# WMHS_Team_A_Mission_Possible_Electrical.net
KiCad netlist of a schematic drawn in EAGLE
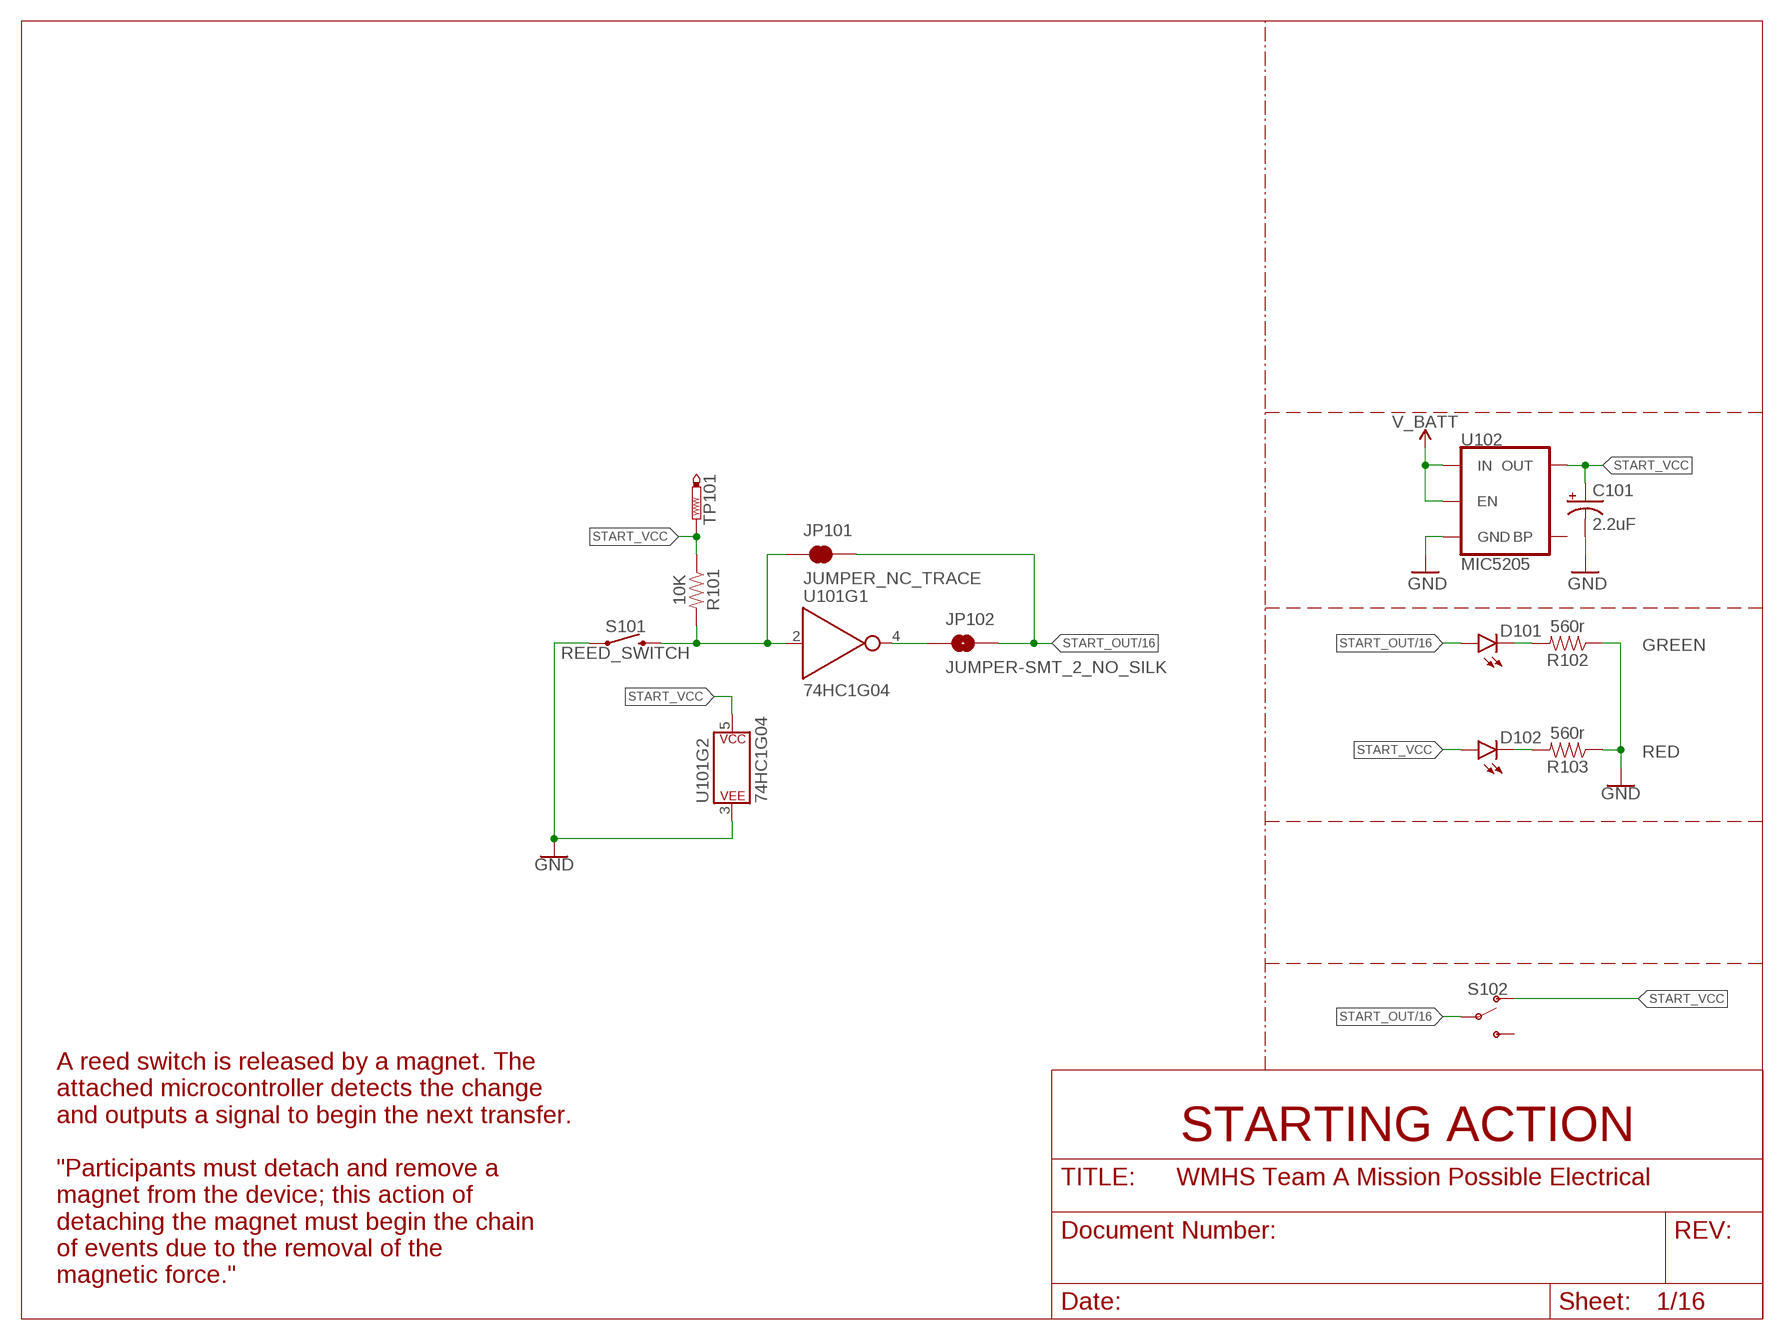
[diagram p0: schematic, sheet 1]
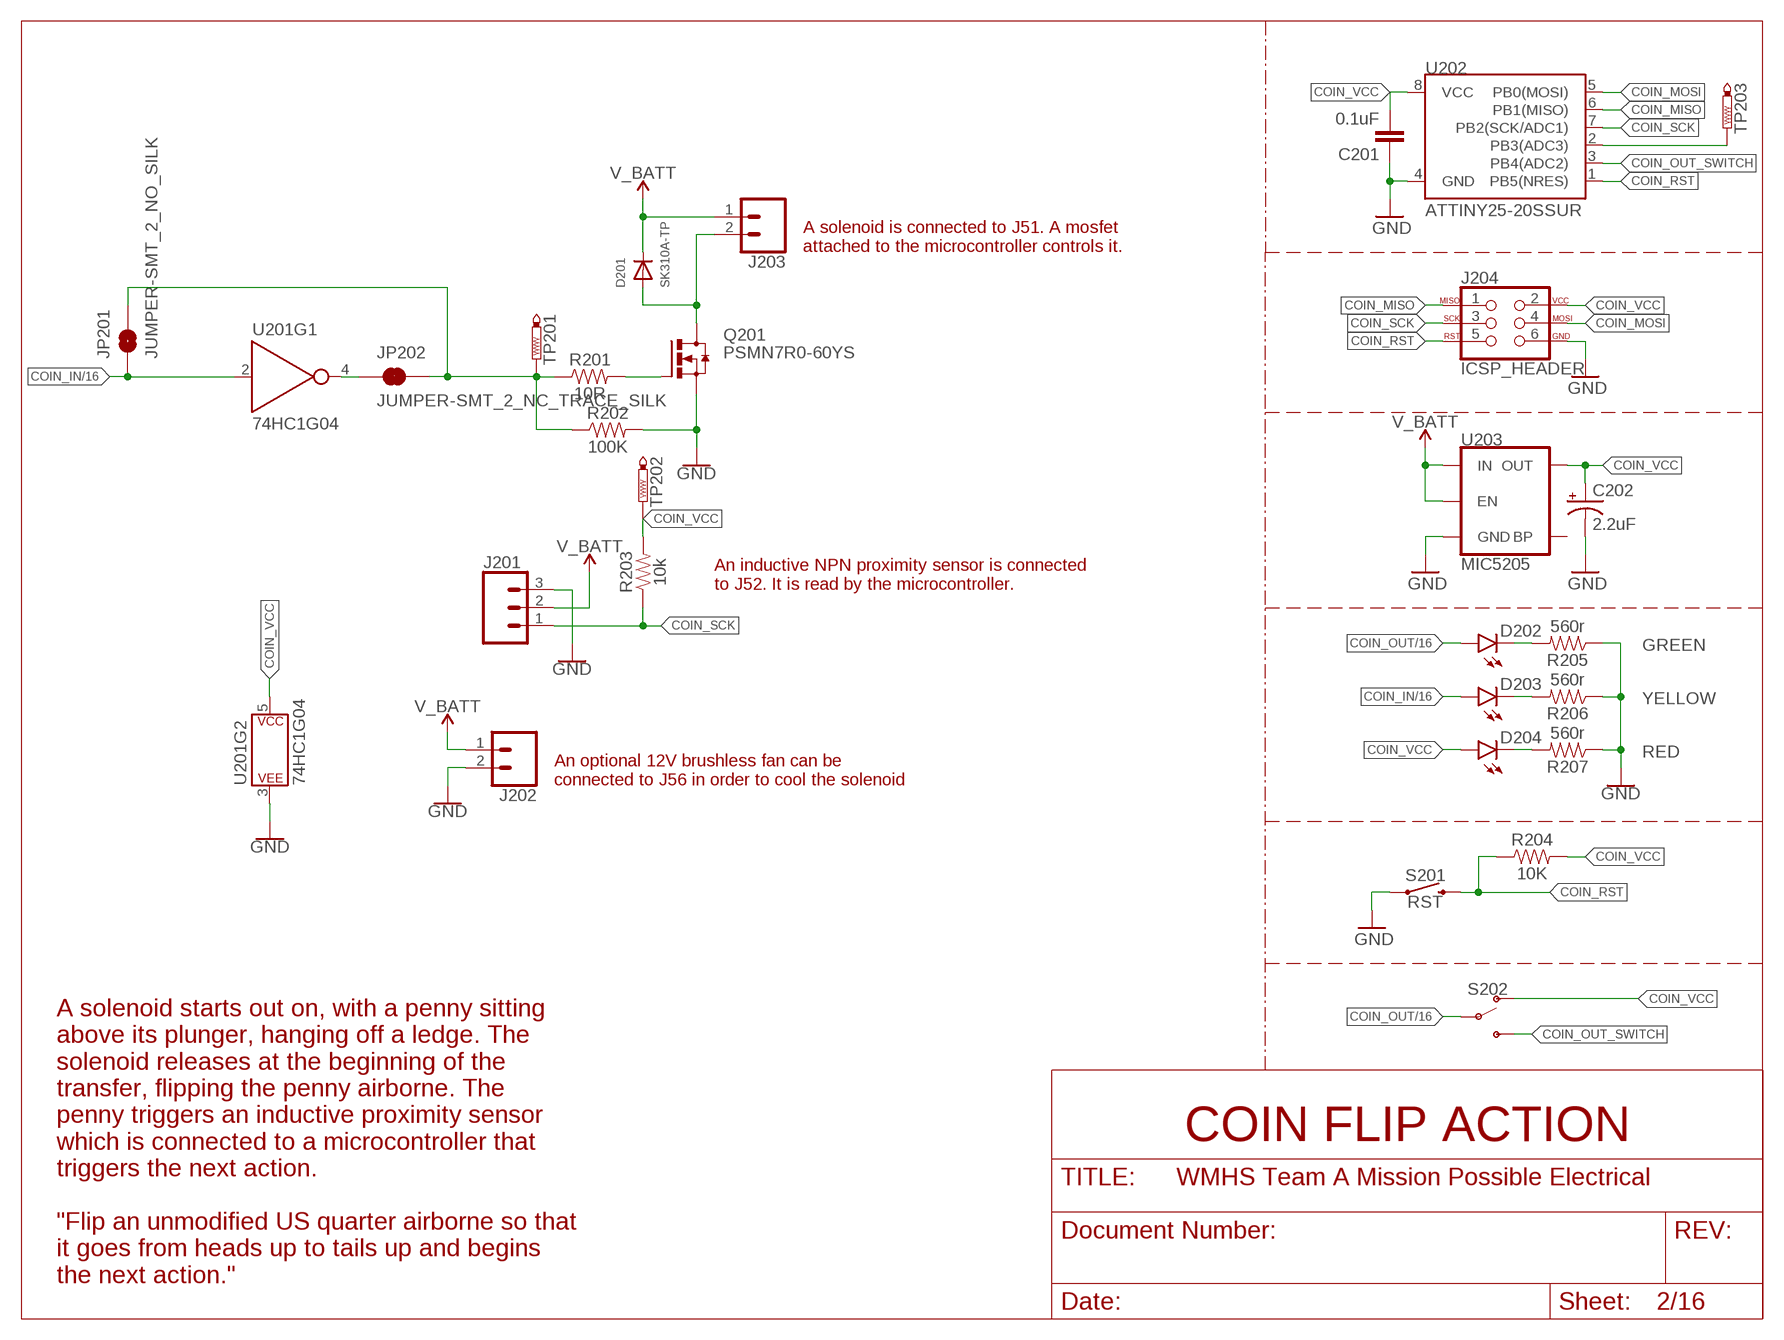
[diagram p1: schematic, sheet 2]
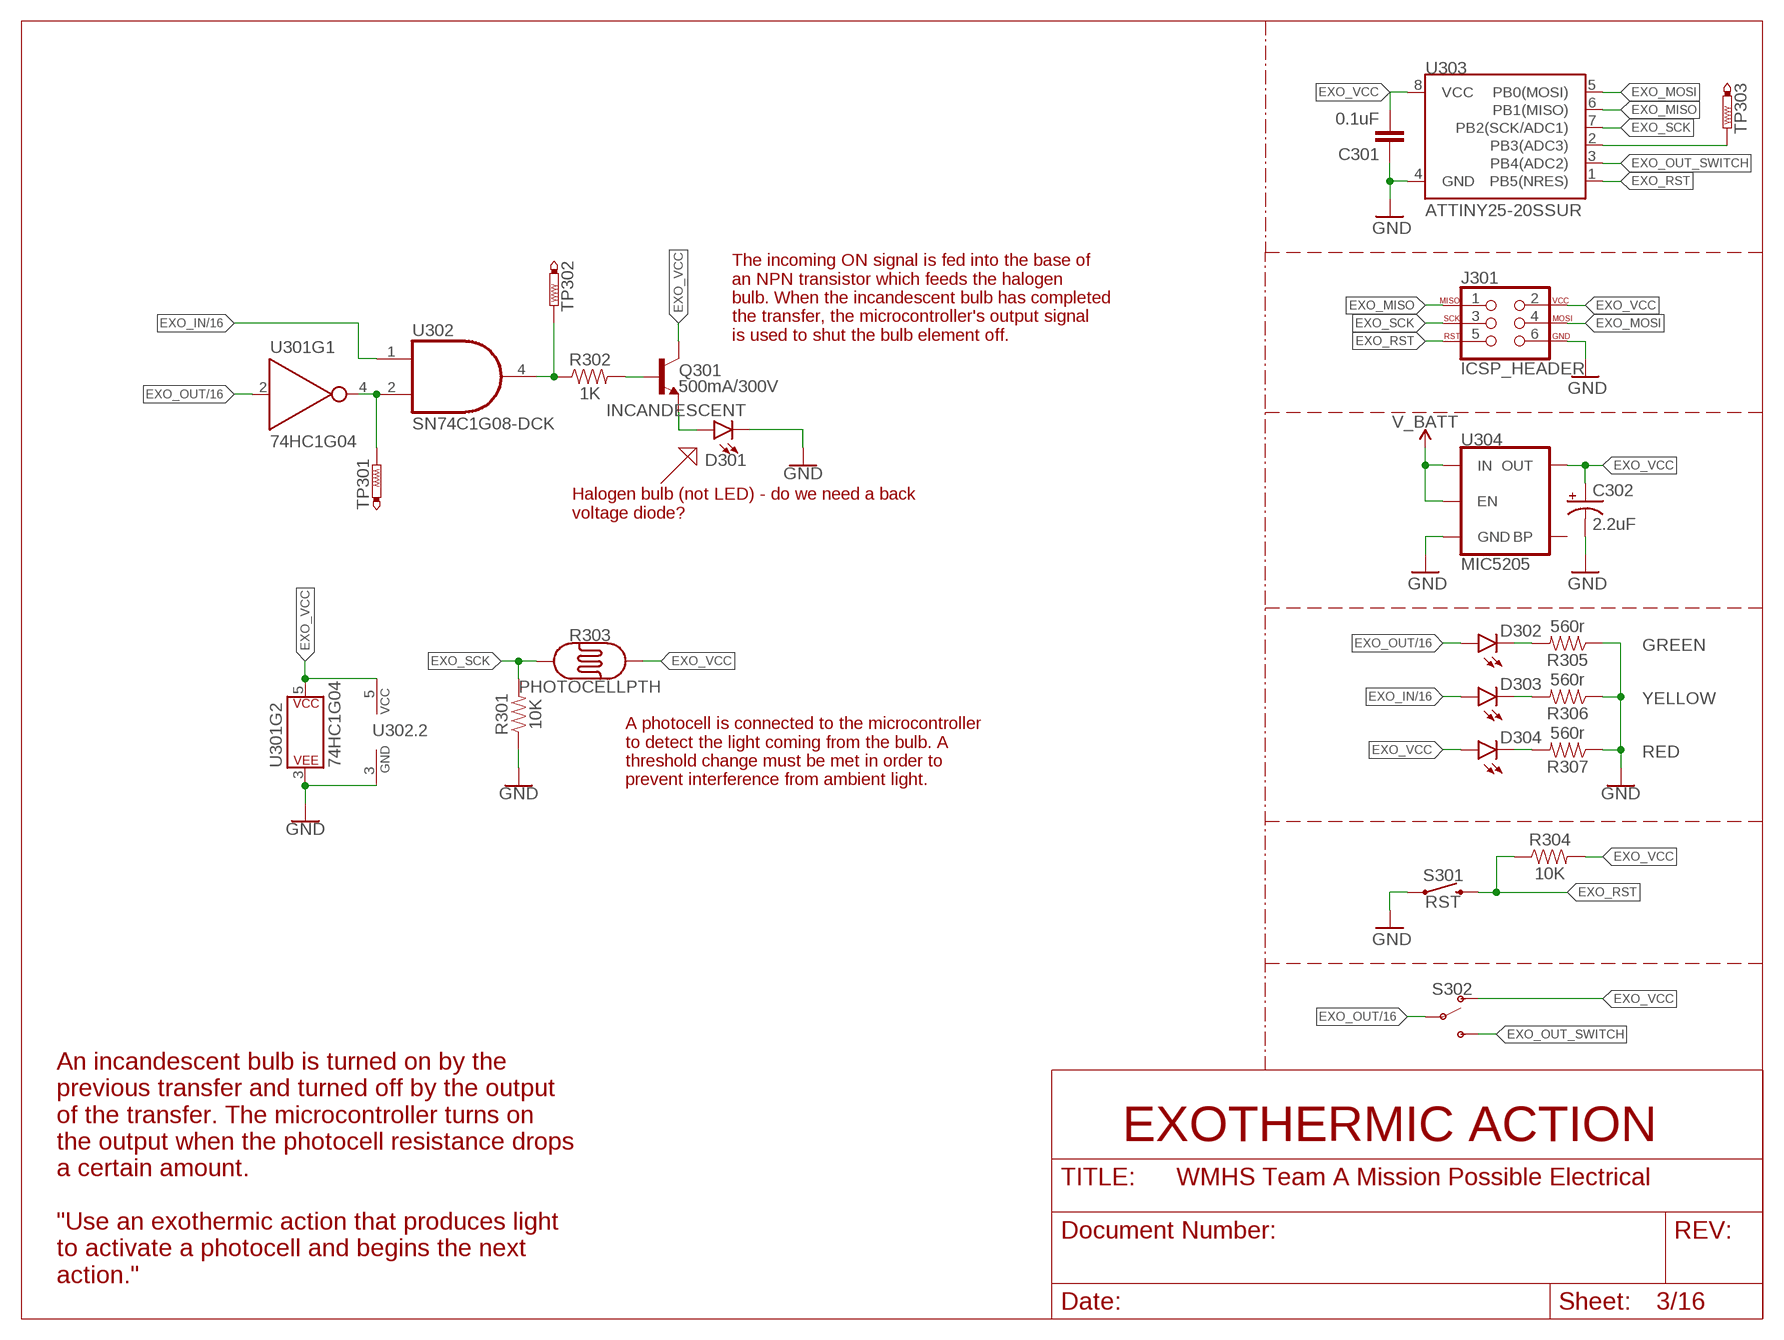
[diagram p2: schematic, sheet 3]
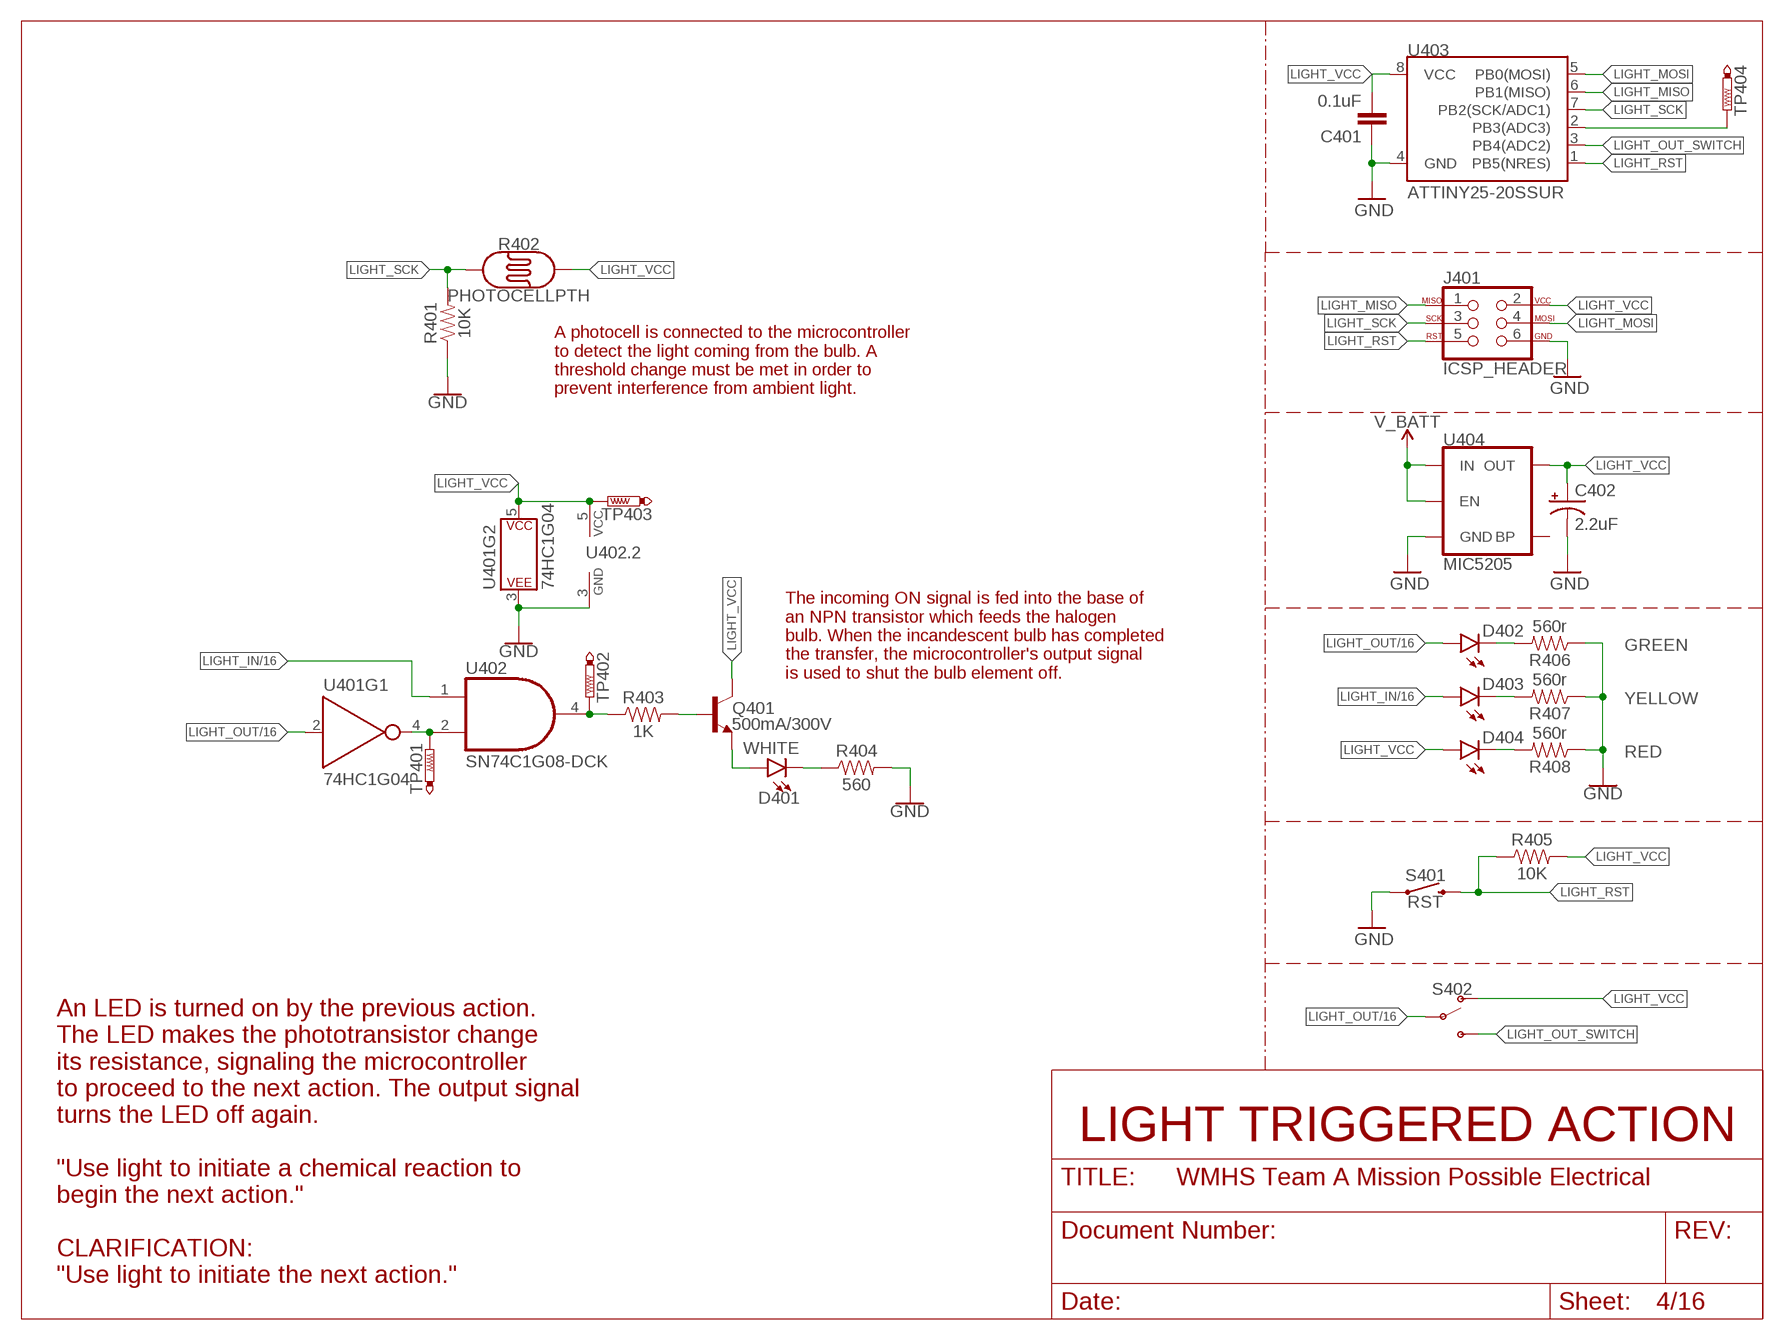
[diagram p3: schematic, sheet 4]
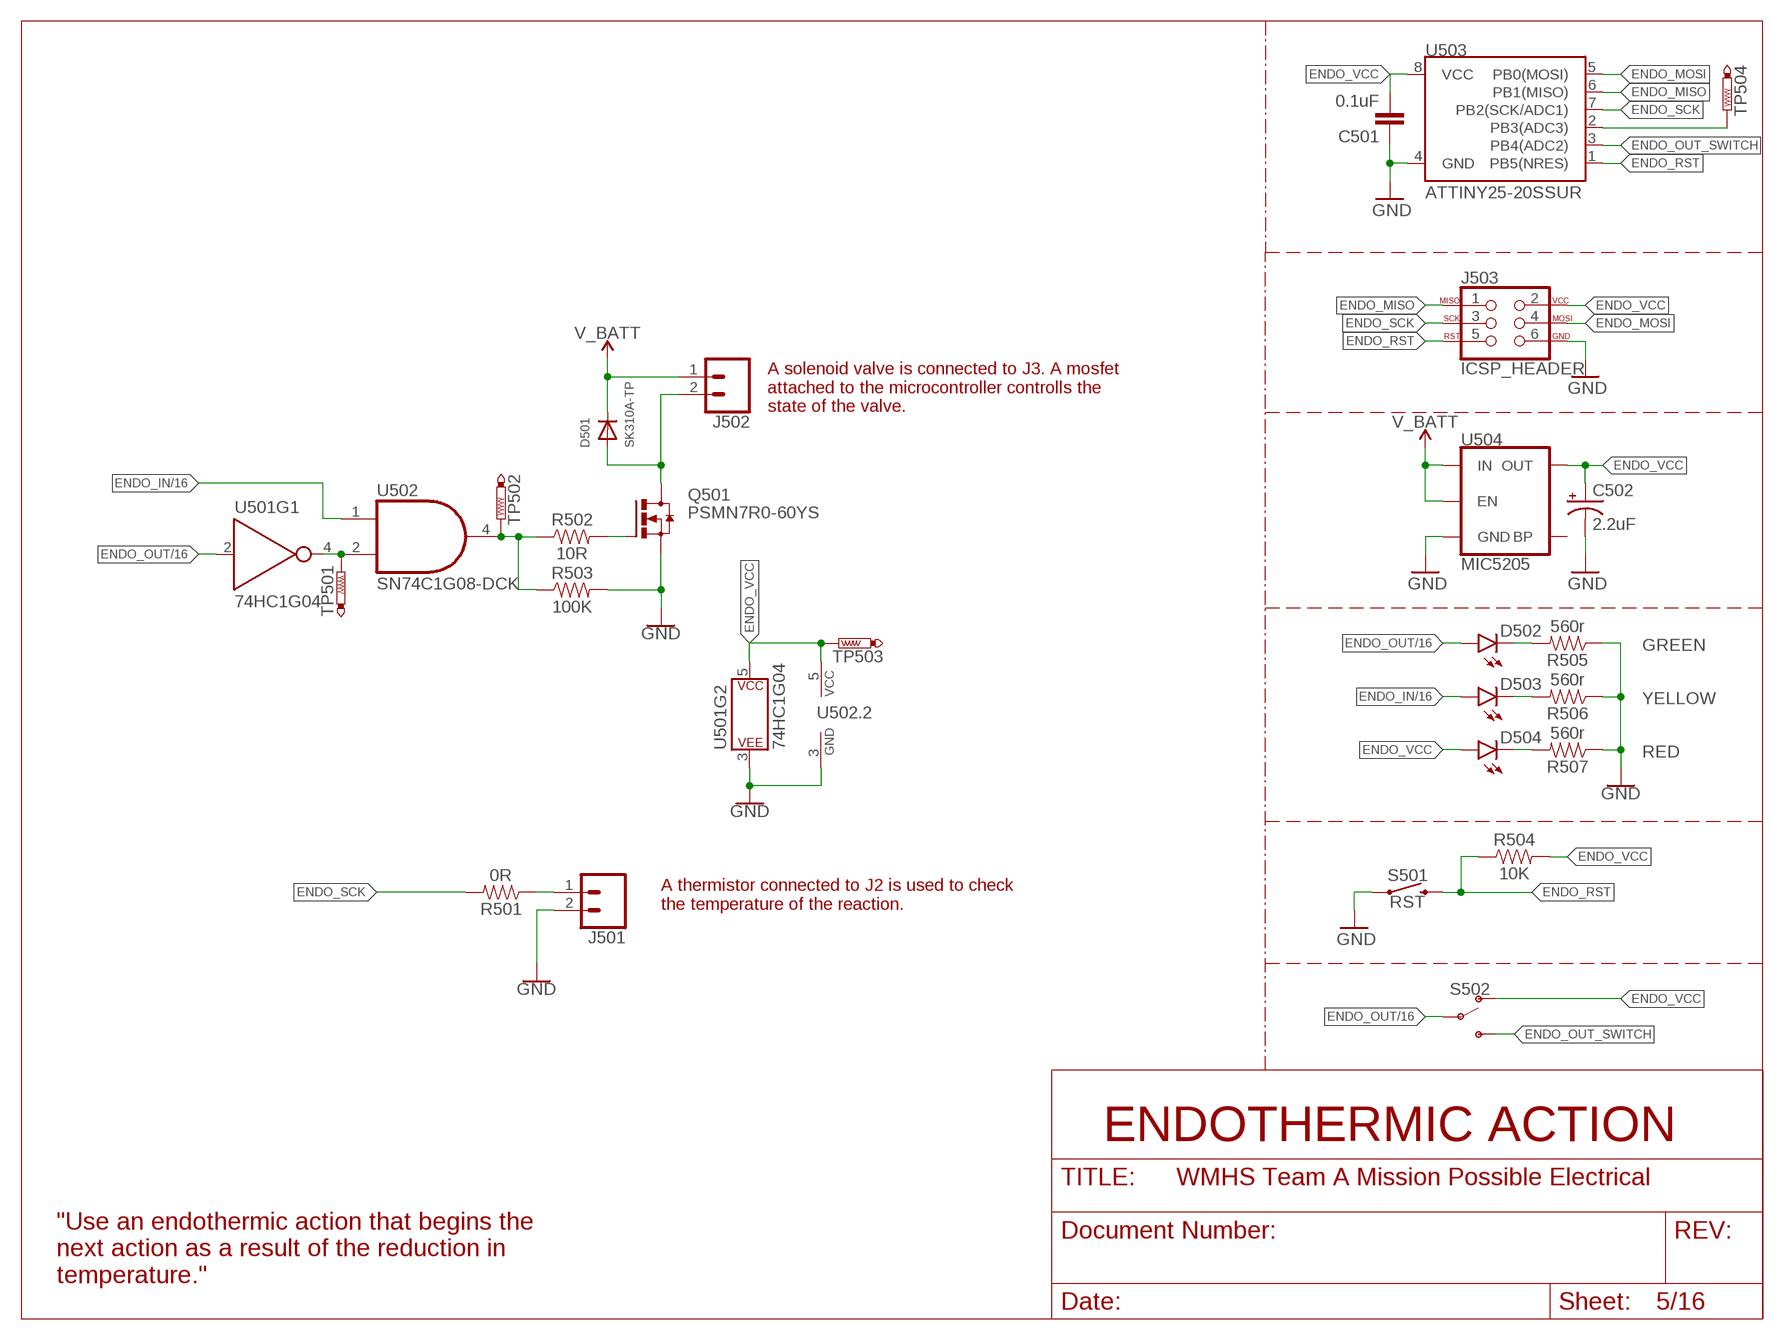
[diagram p4: schematic, sheet 5]
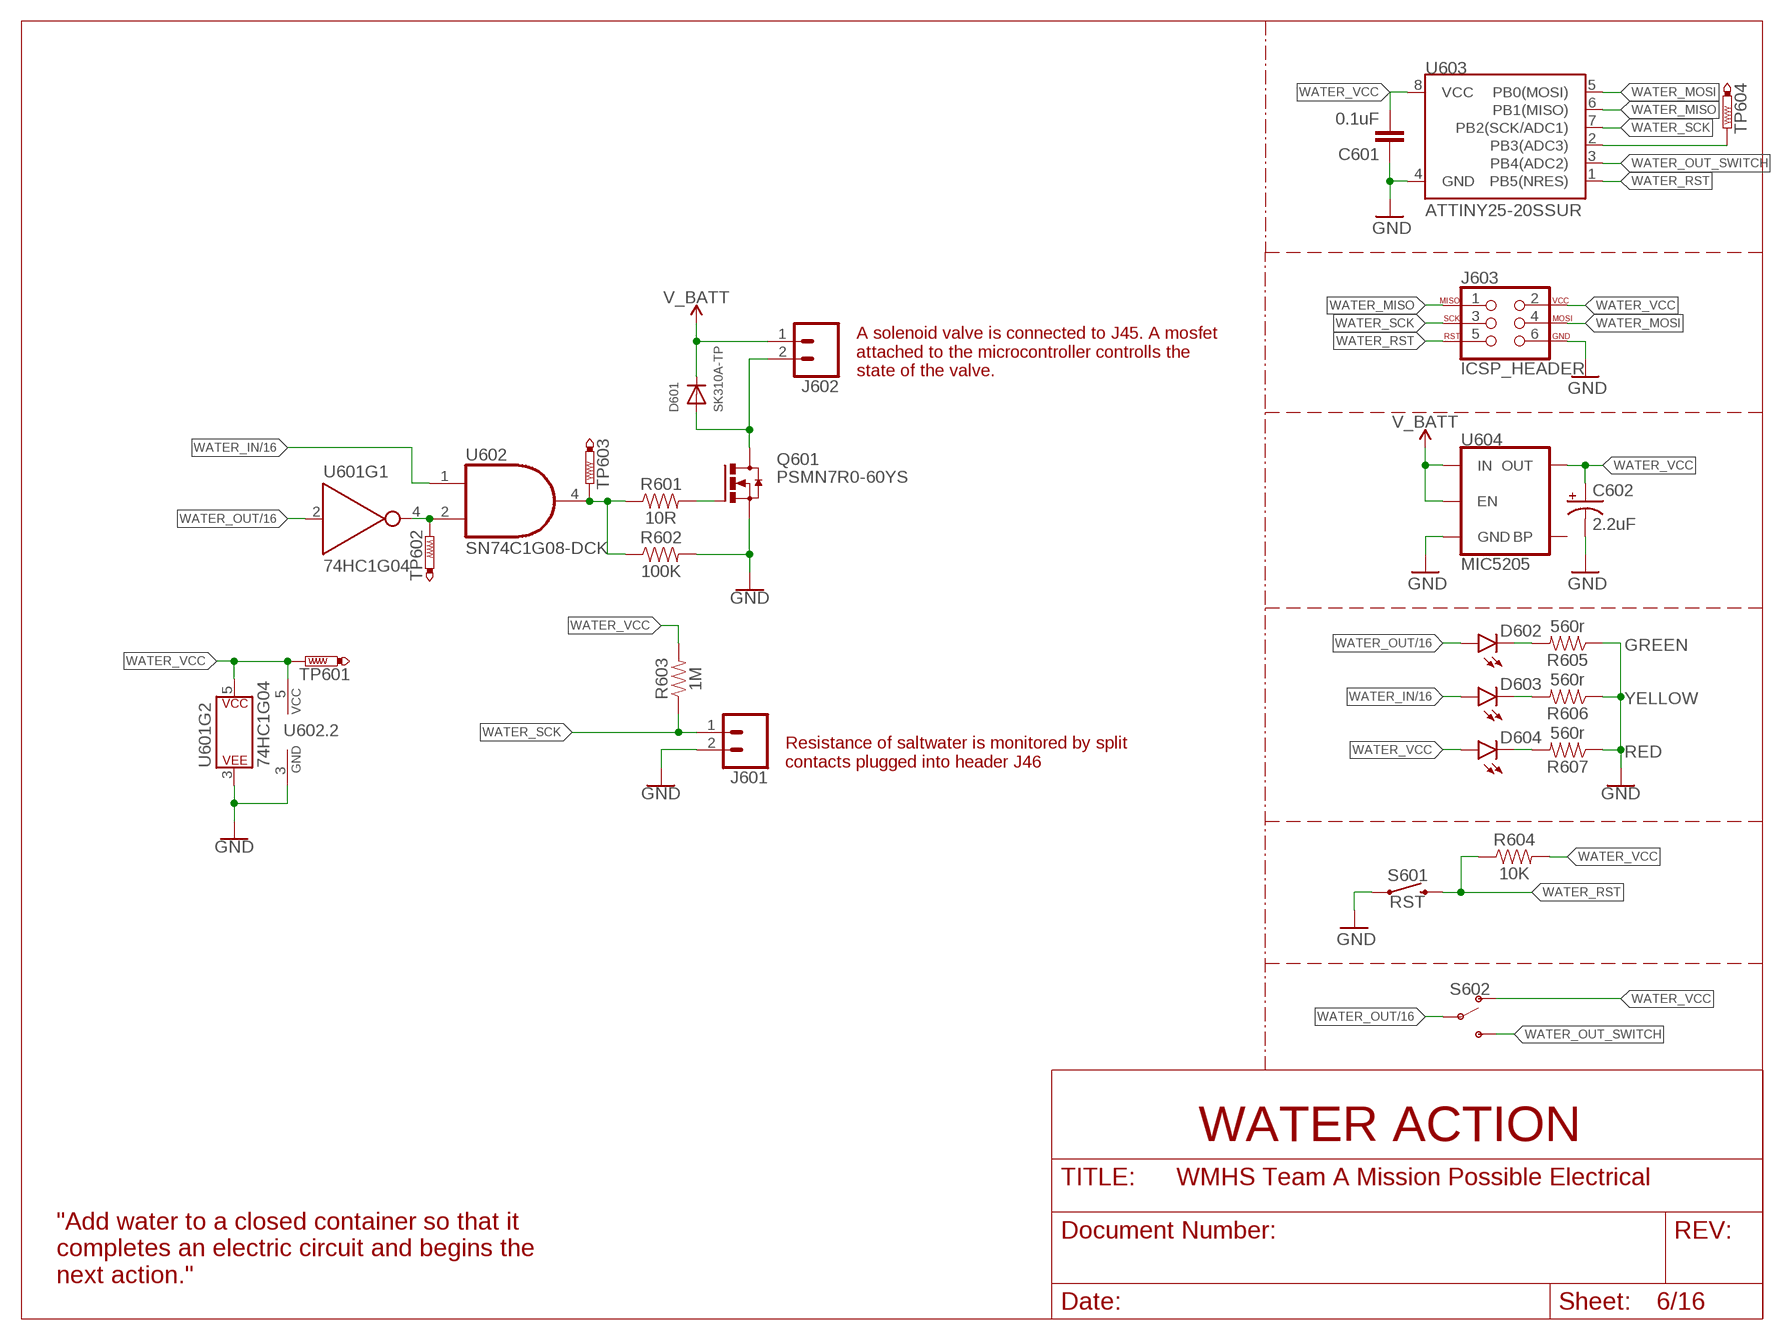
[diagram p5: schematic, sheet 6]
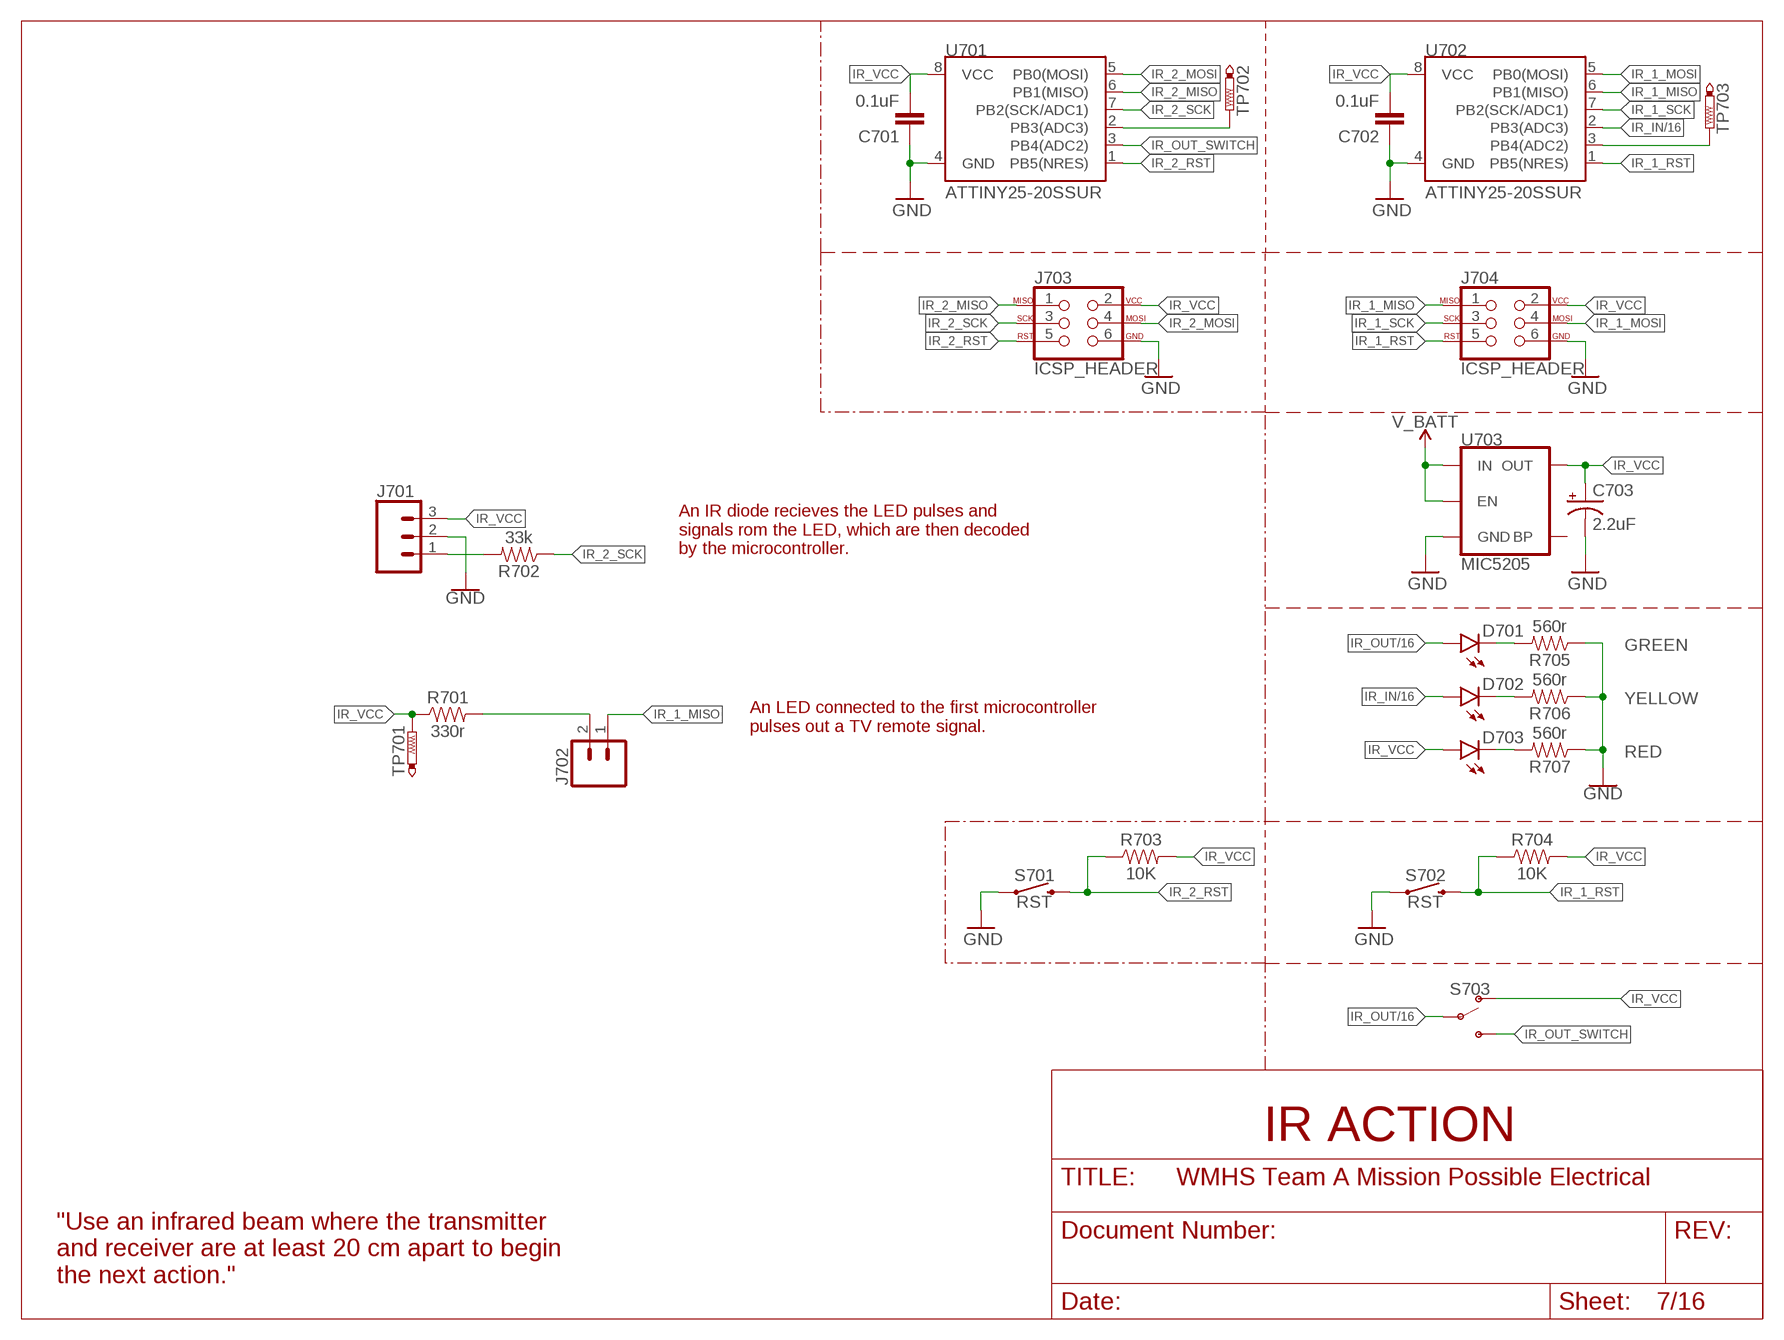
[diagram p6: schematic, sheet 7]
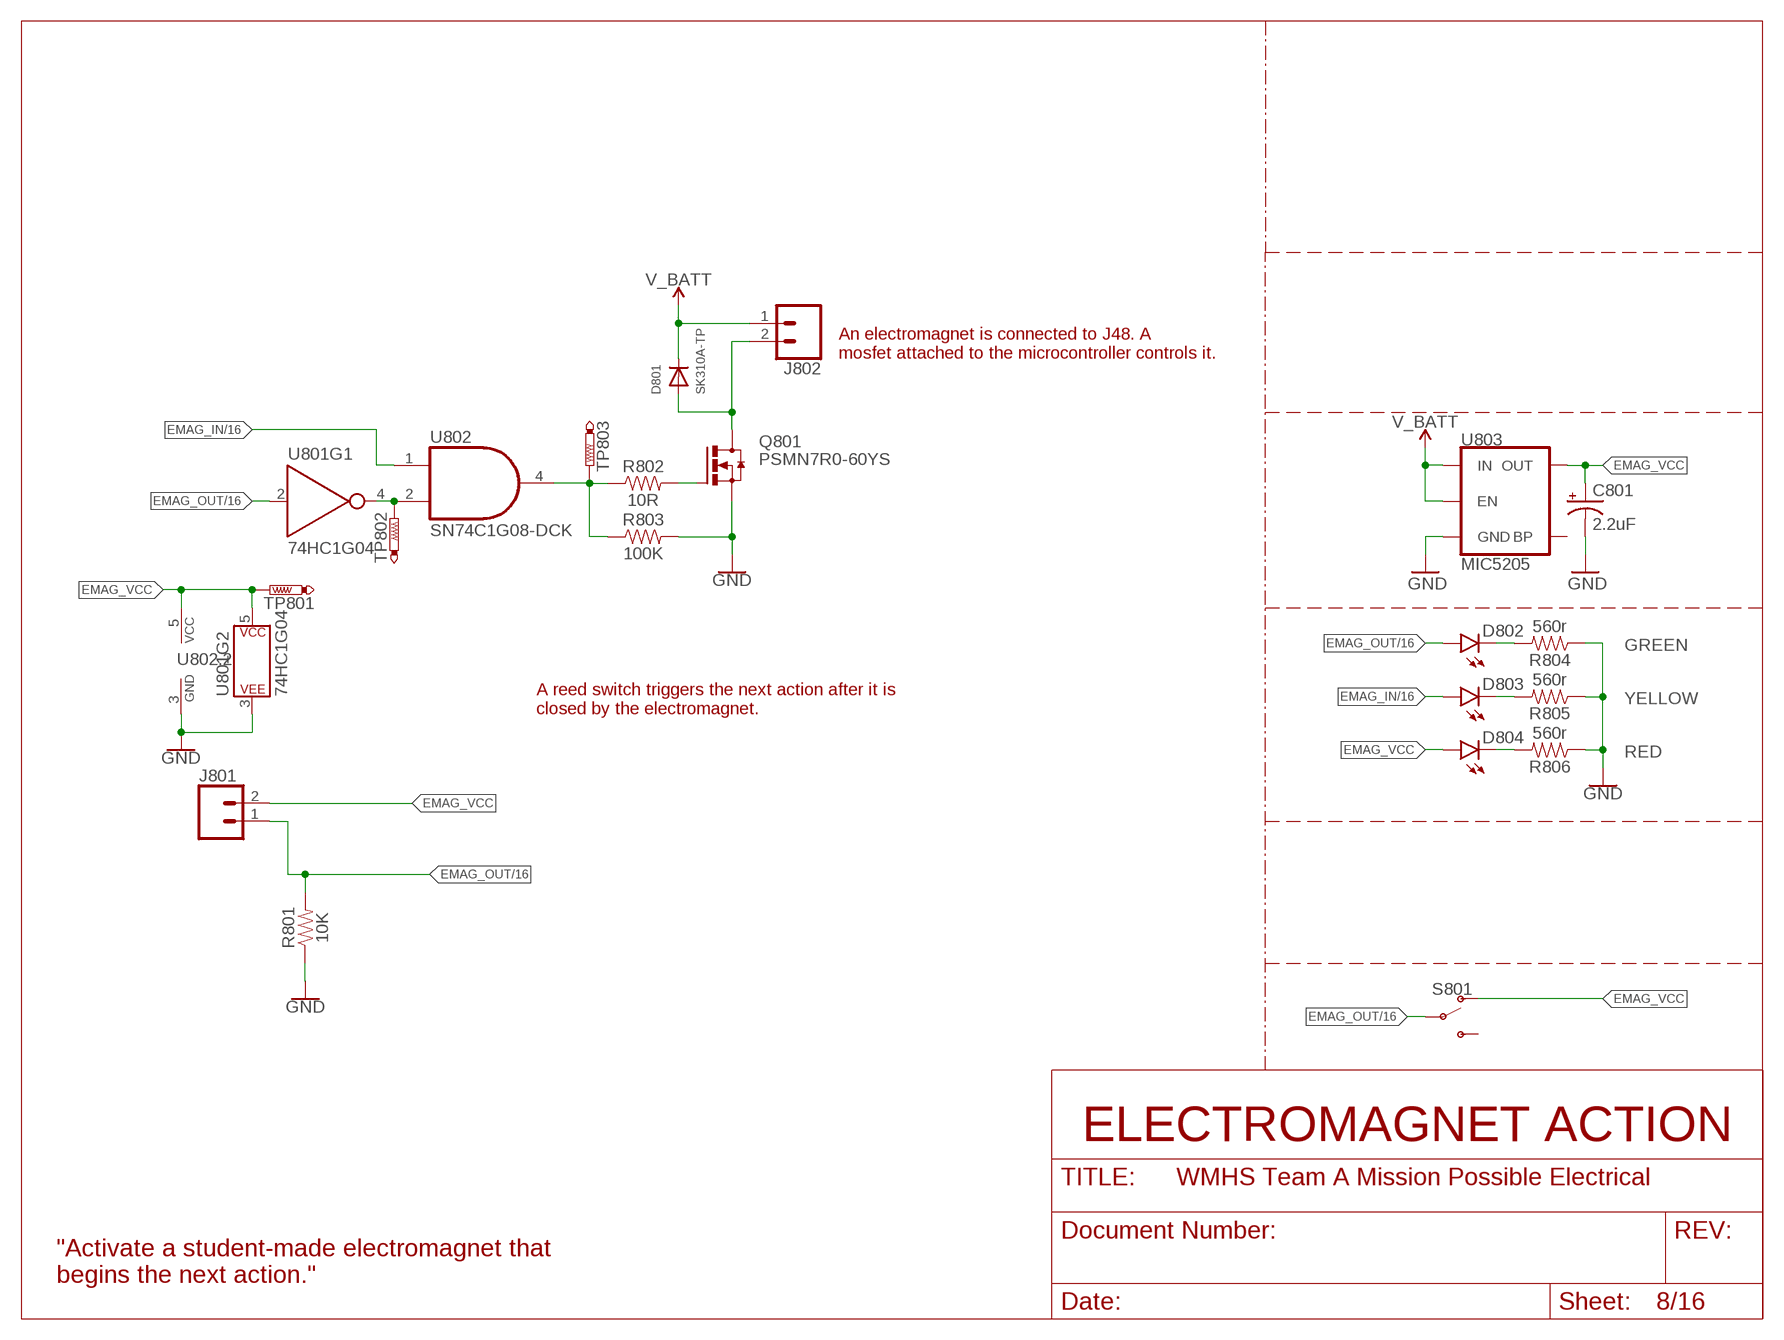
[diagram p7: schematic, sheet 8]
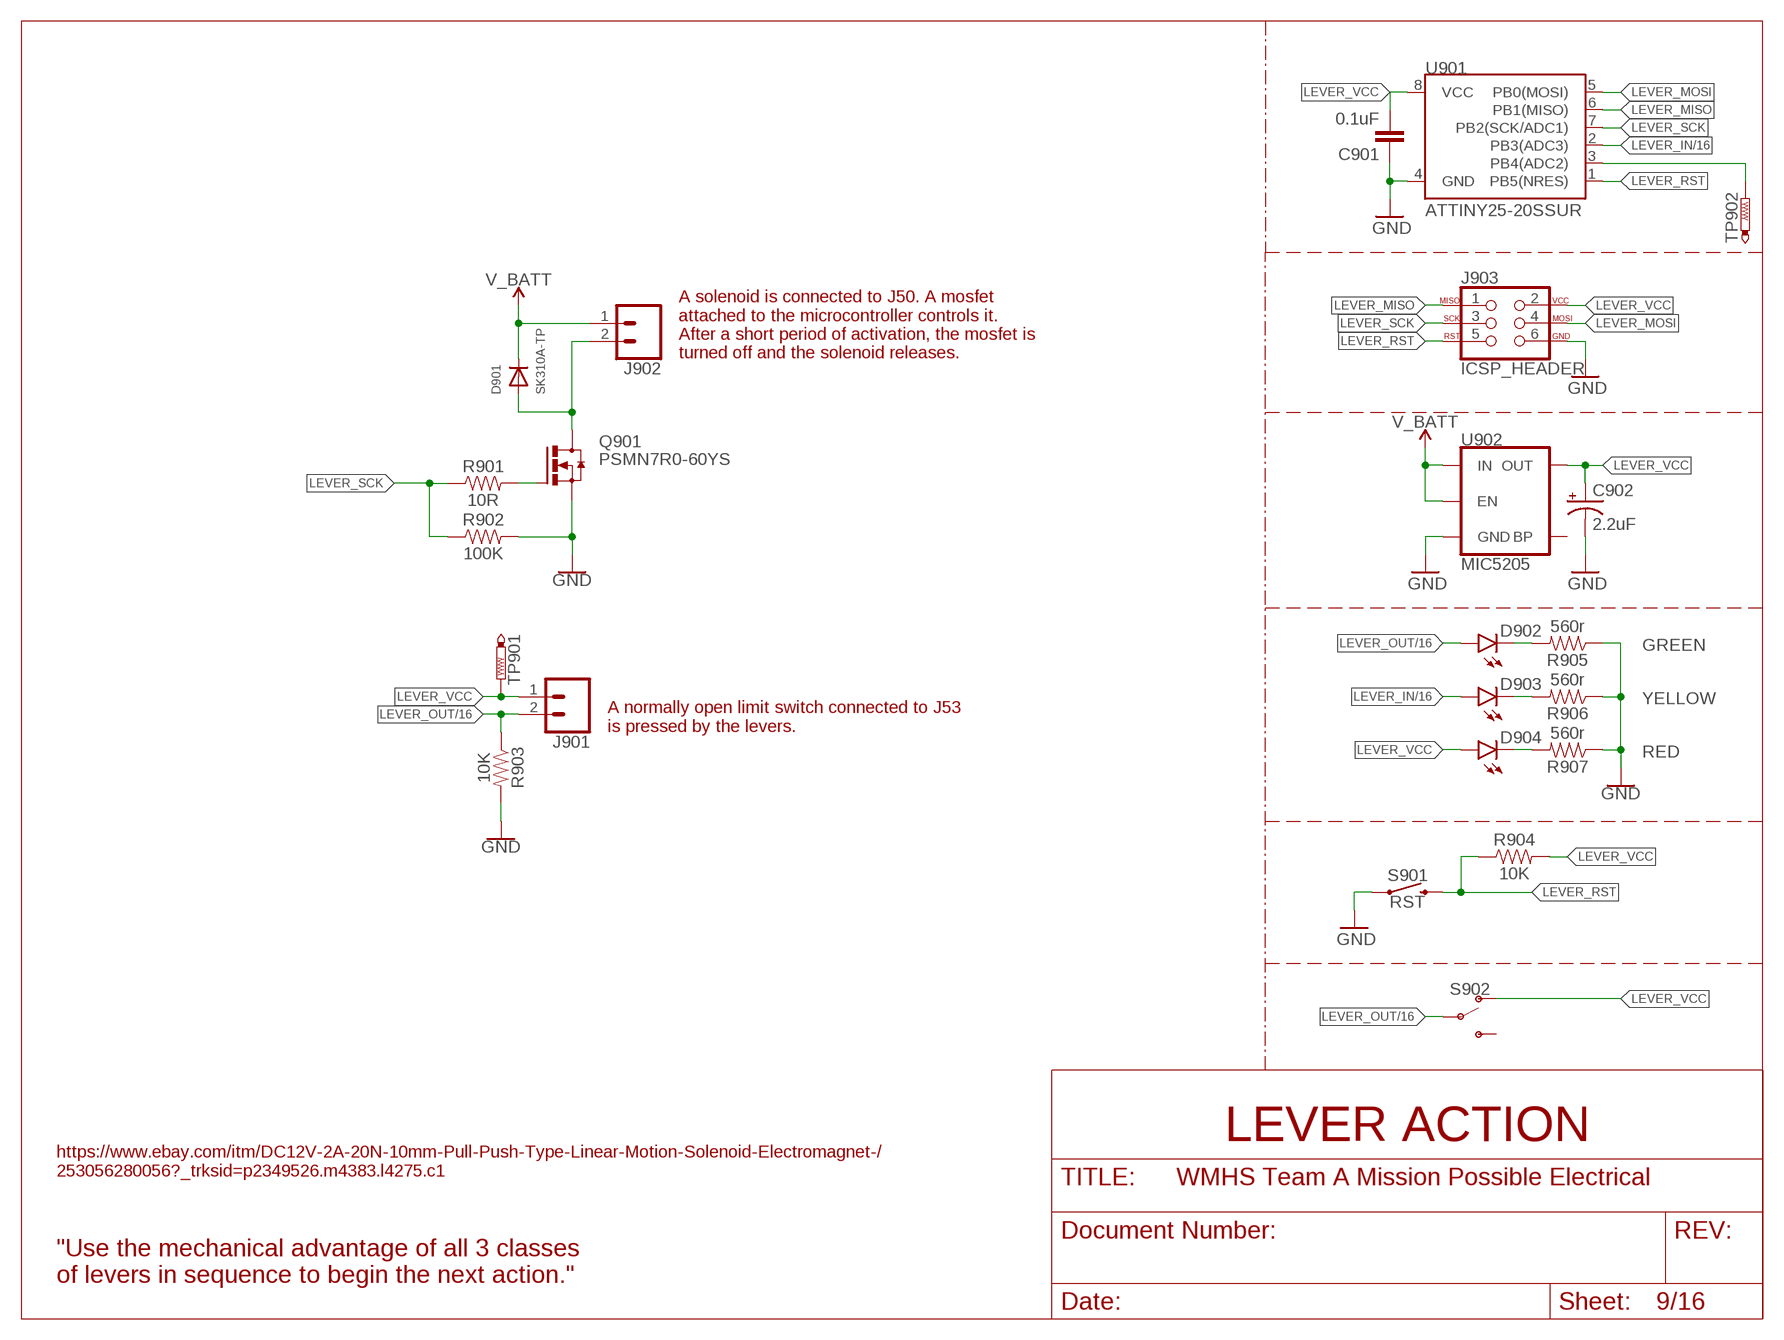
[diagram p8: schematic, sheet 9]
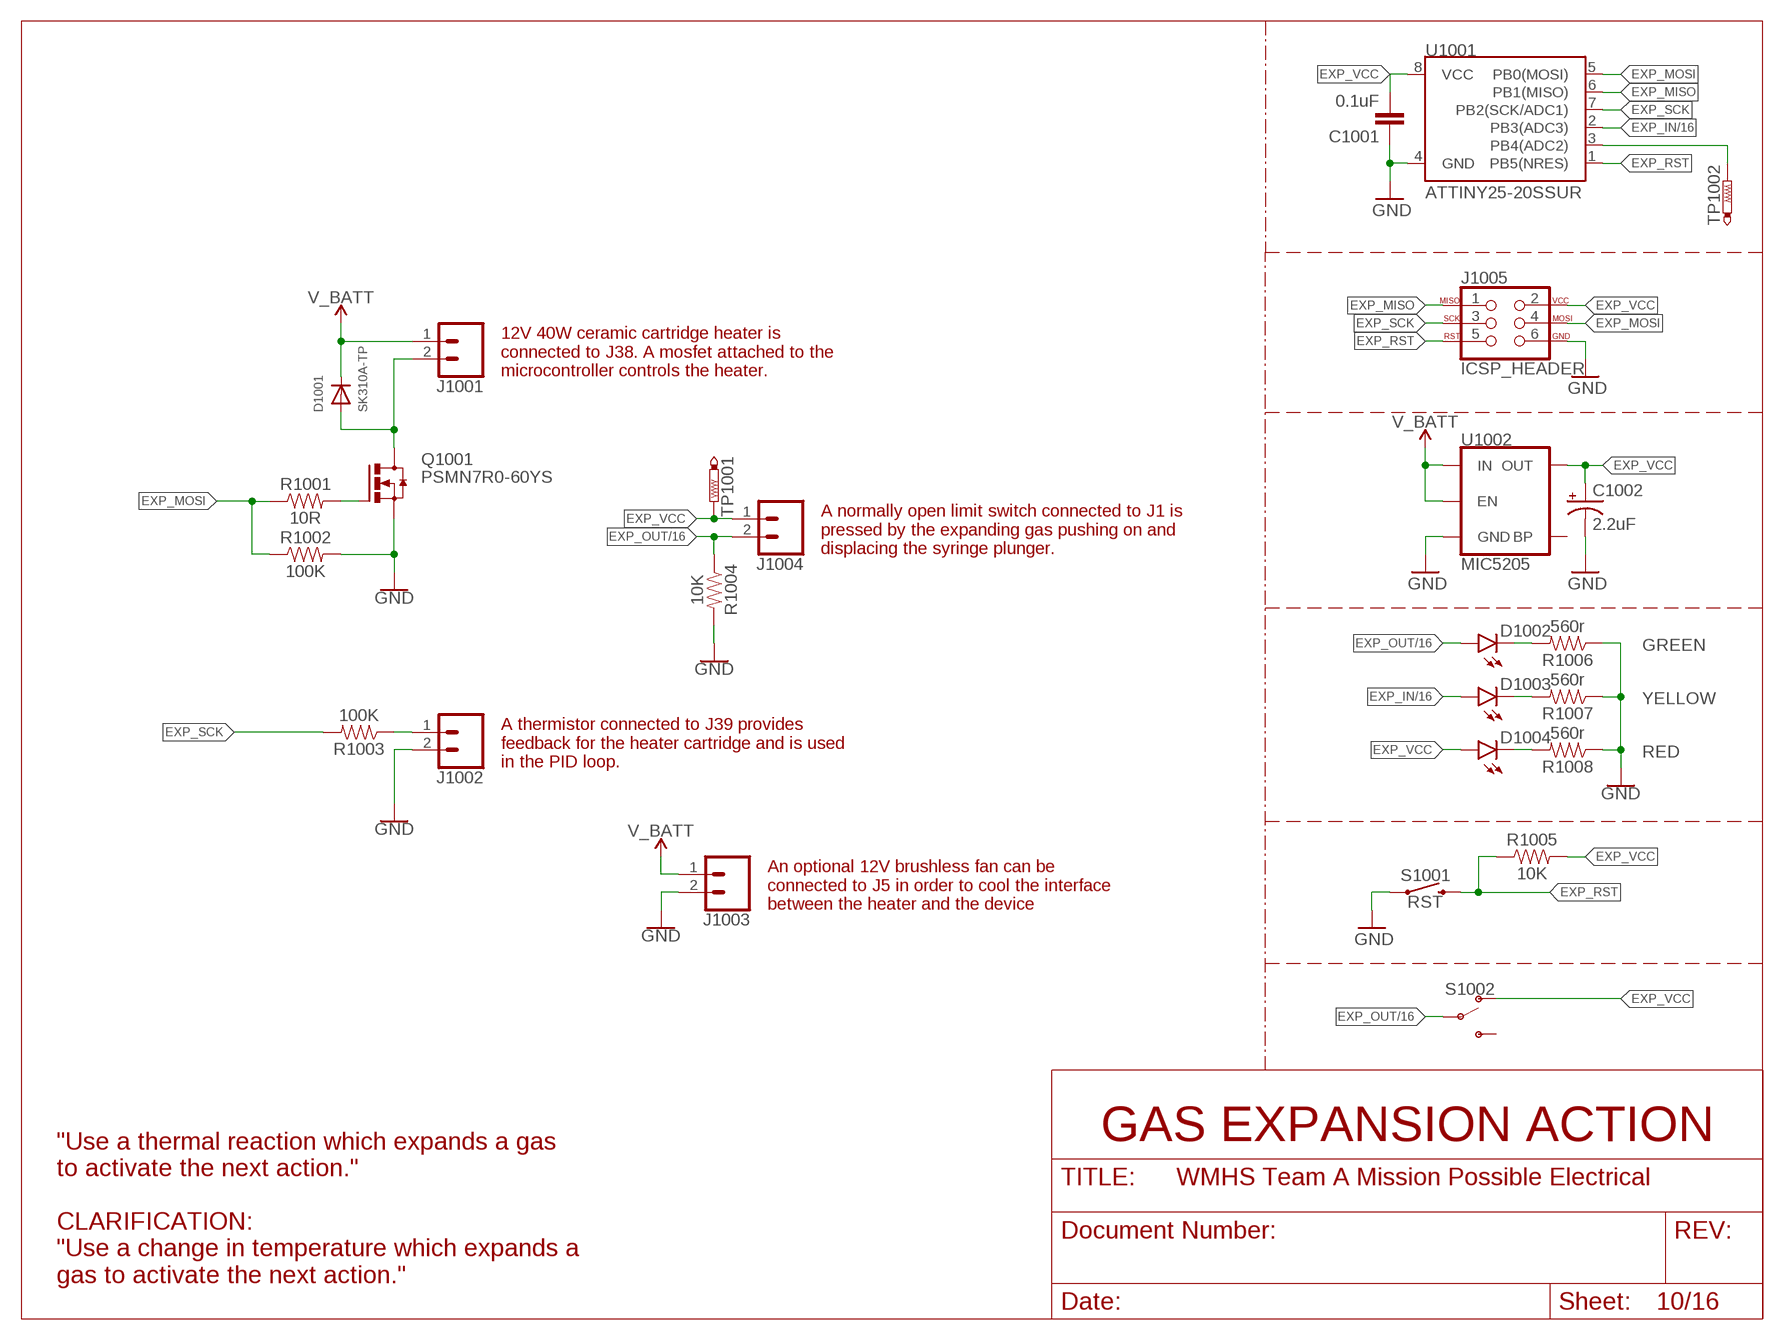
[diagram p9: schematic, sheet 10]
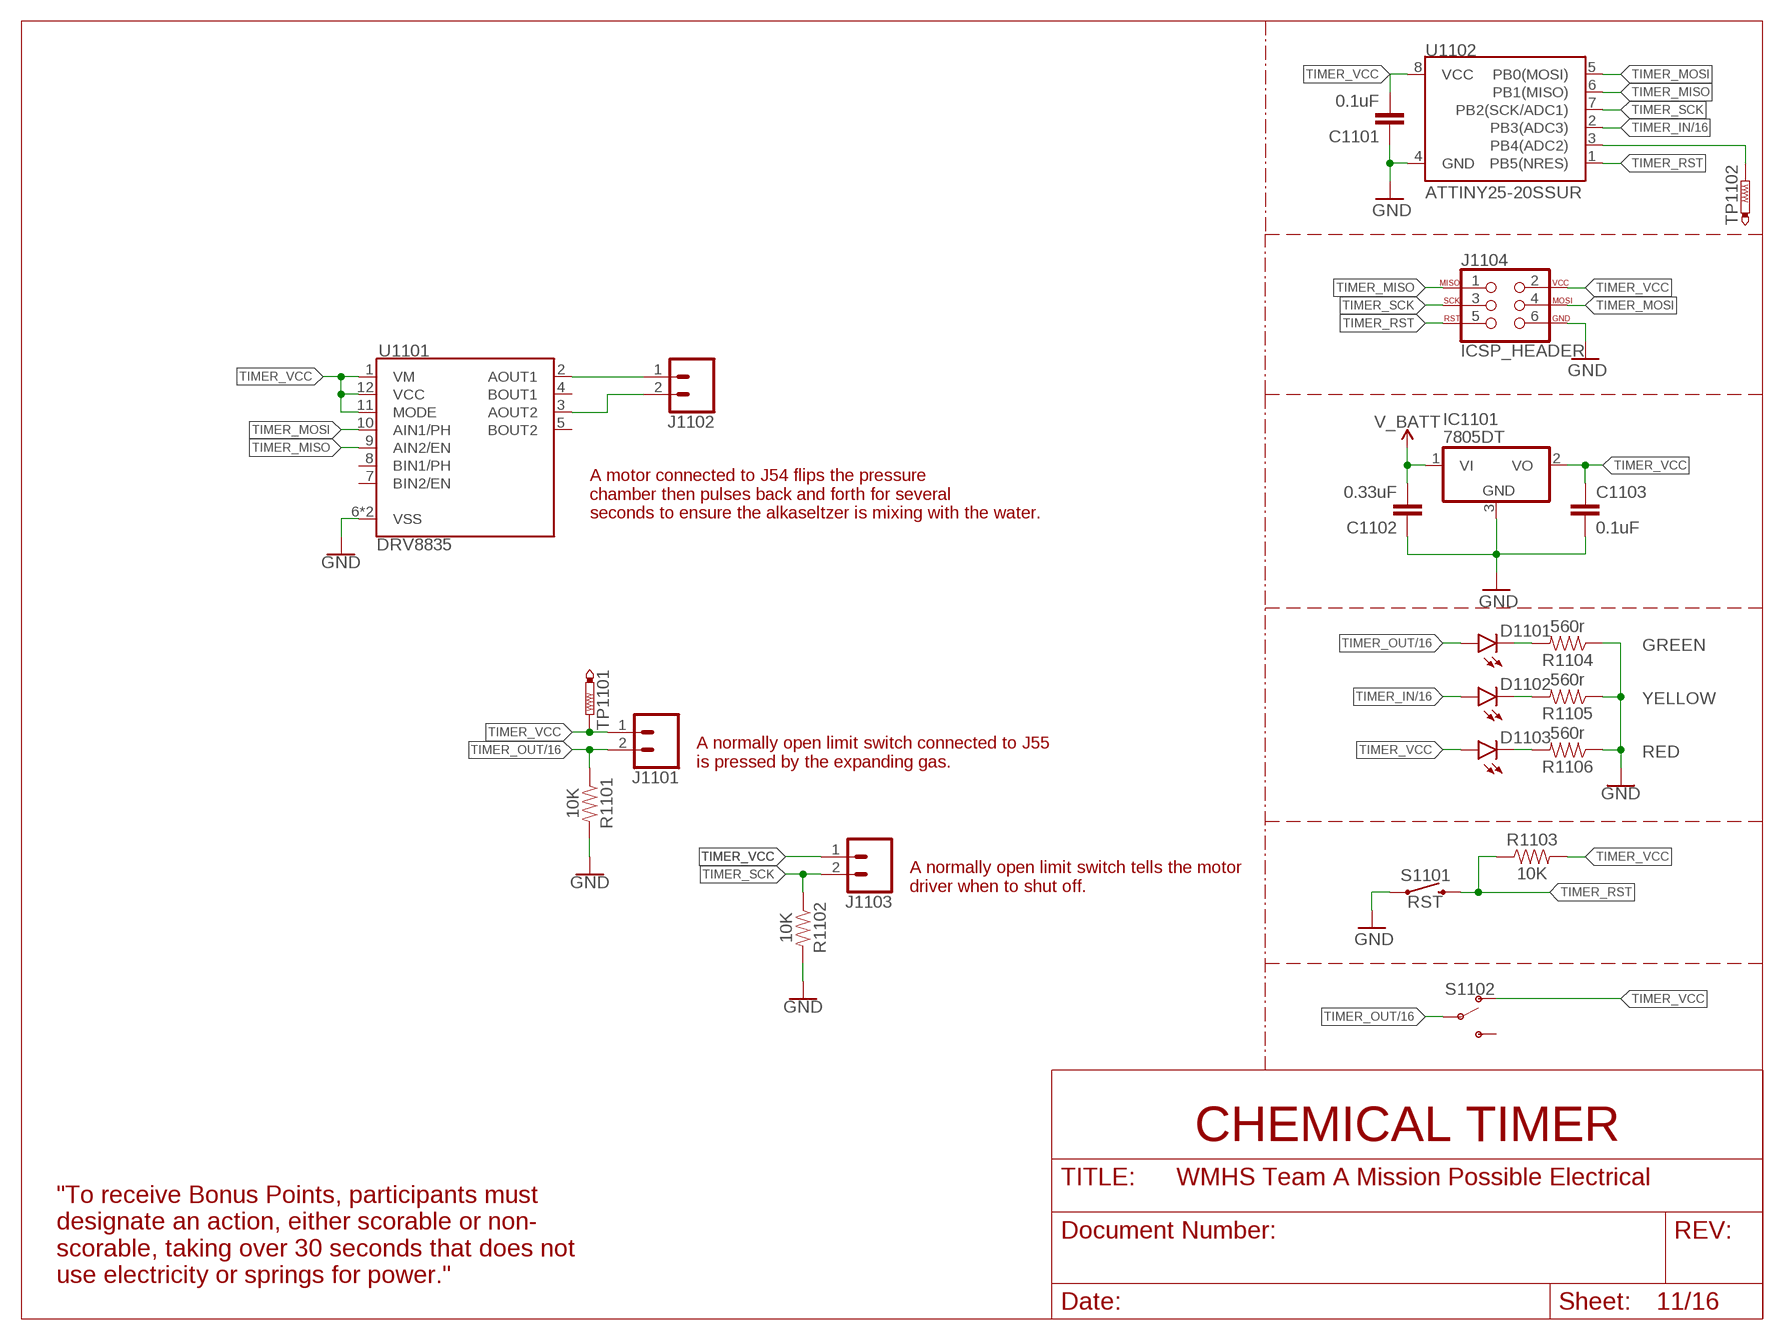
[diagram p10: schematic, sheet 11]
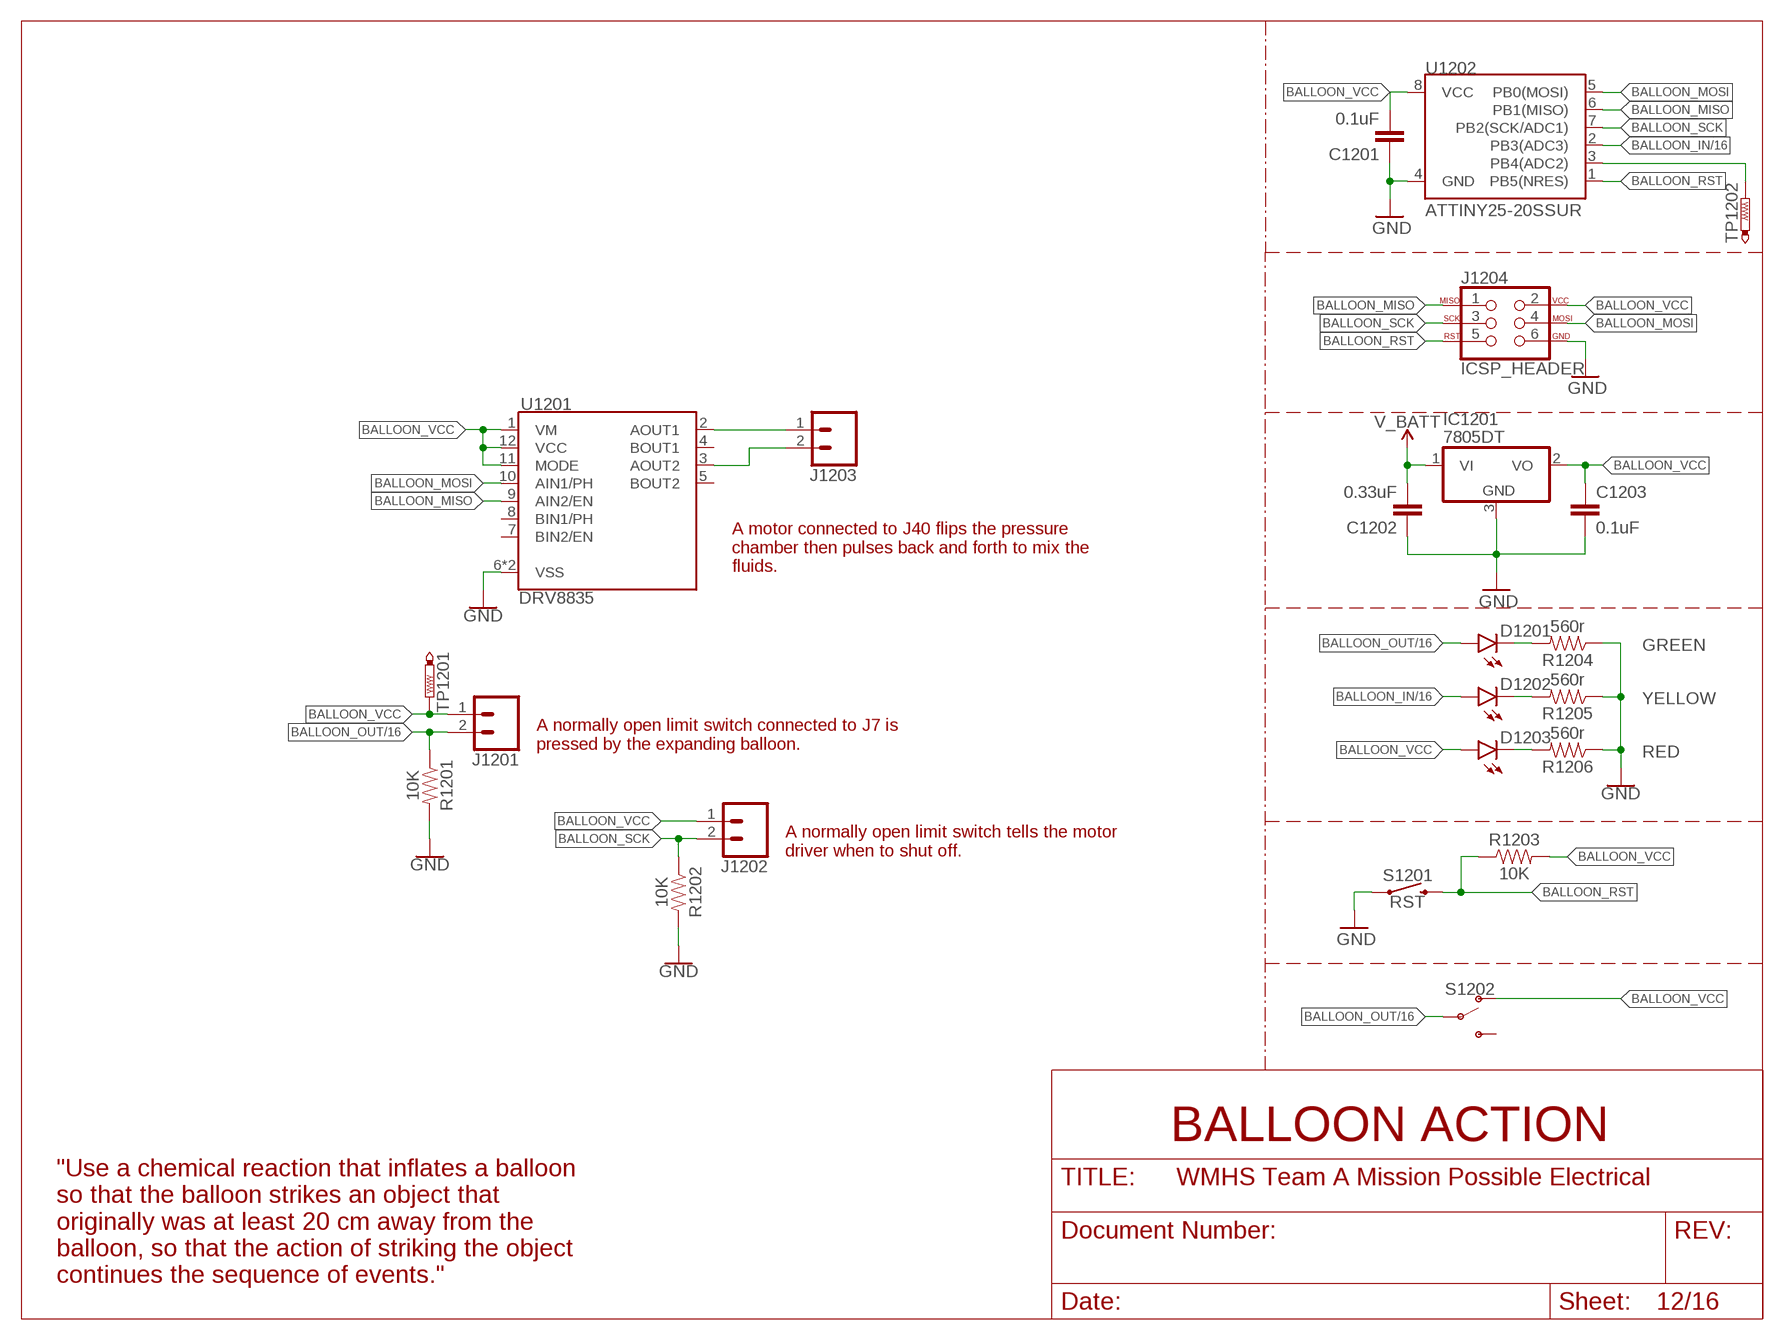
[diagram p11: schematic, sheet 12]
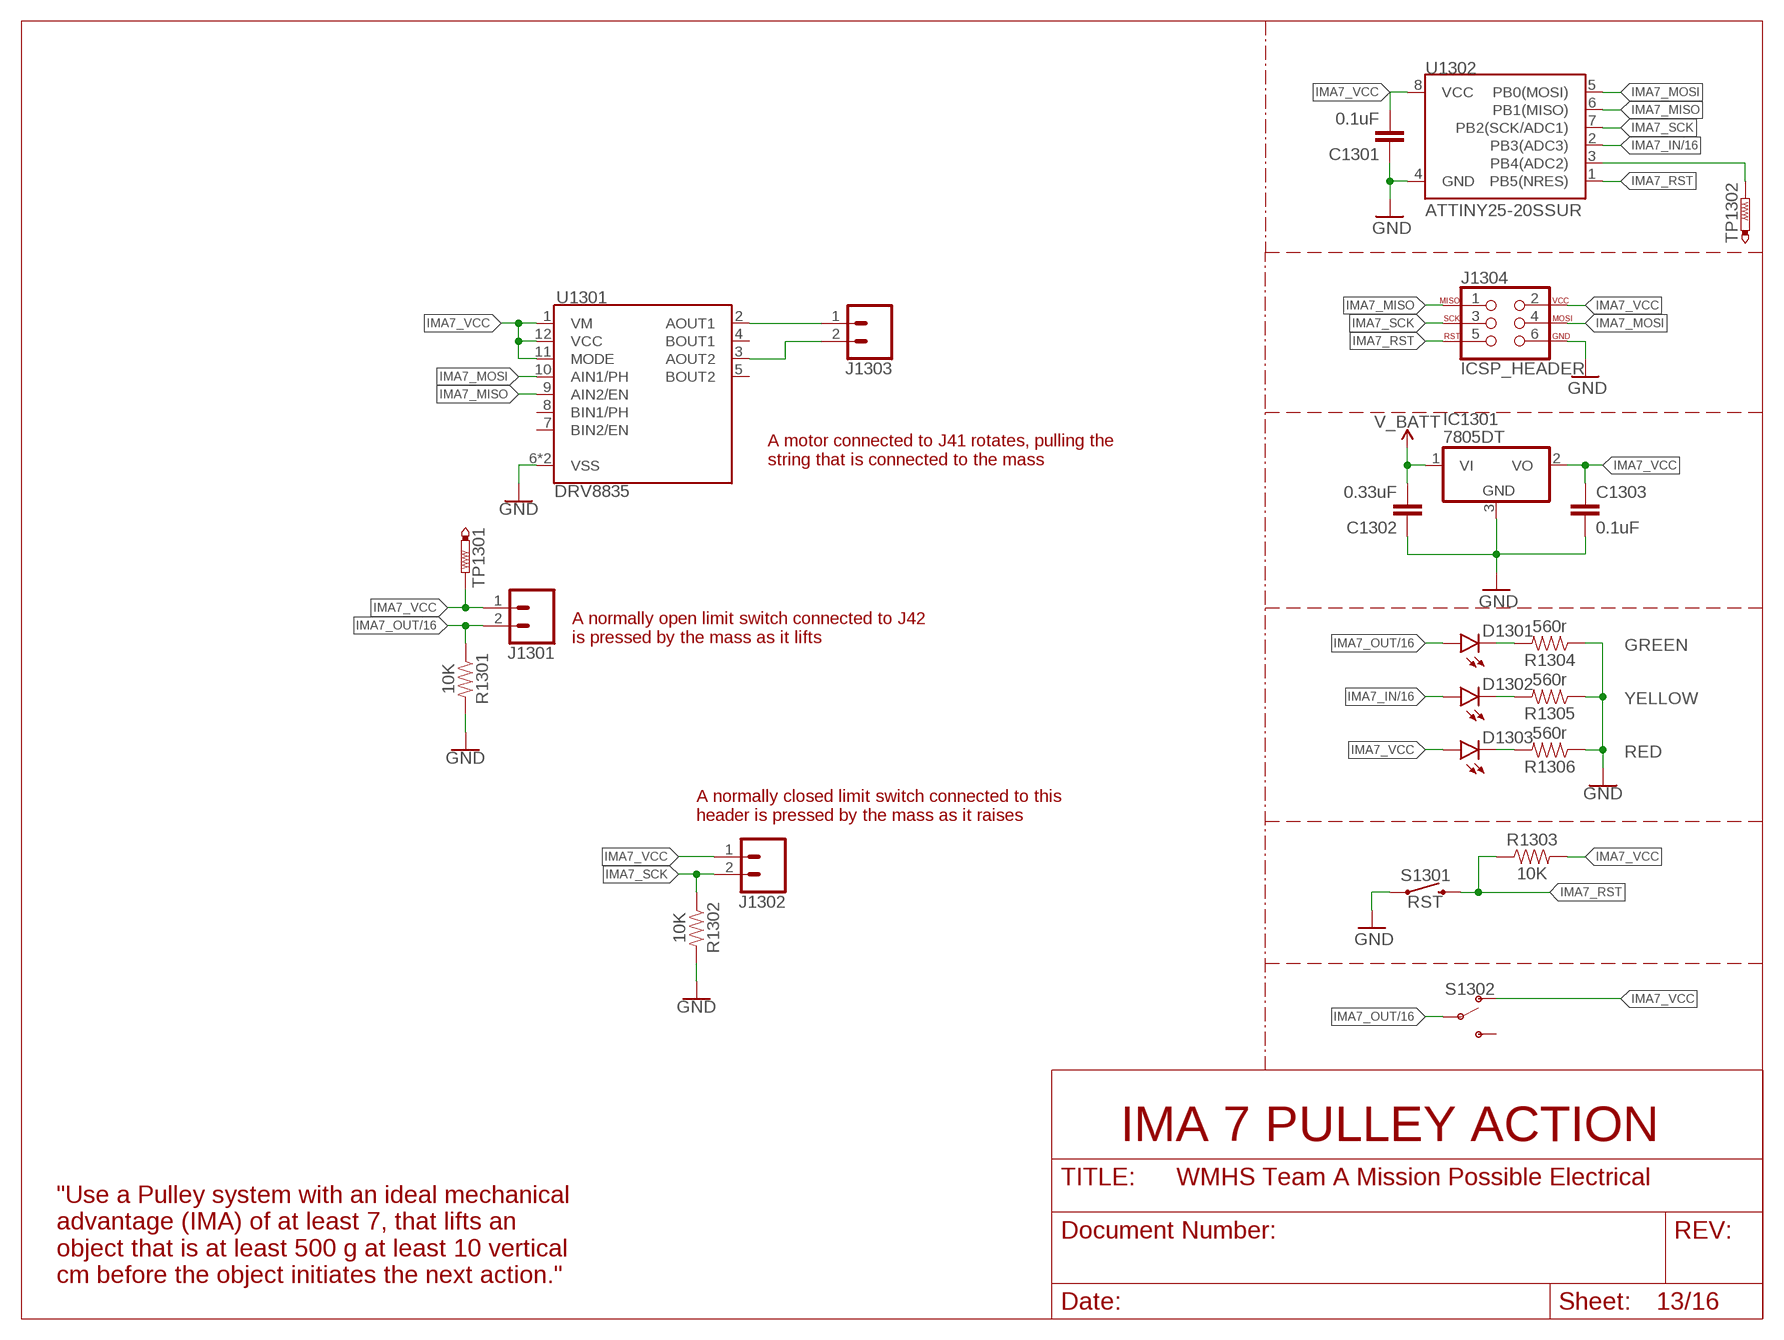
[diagram p12: schematic, sheet 13]
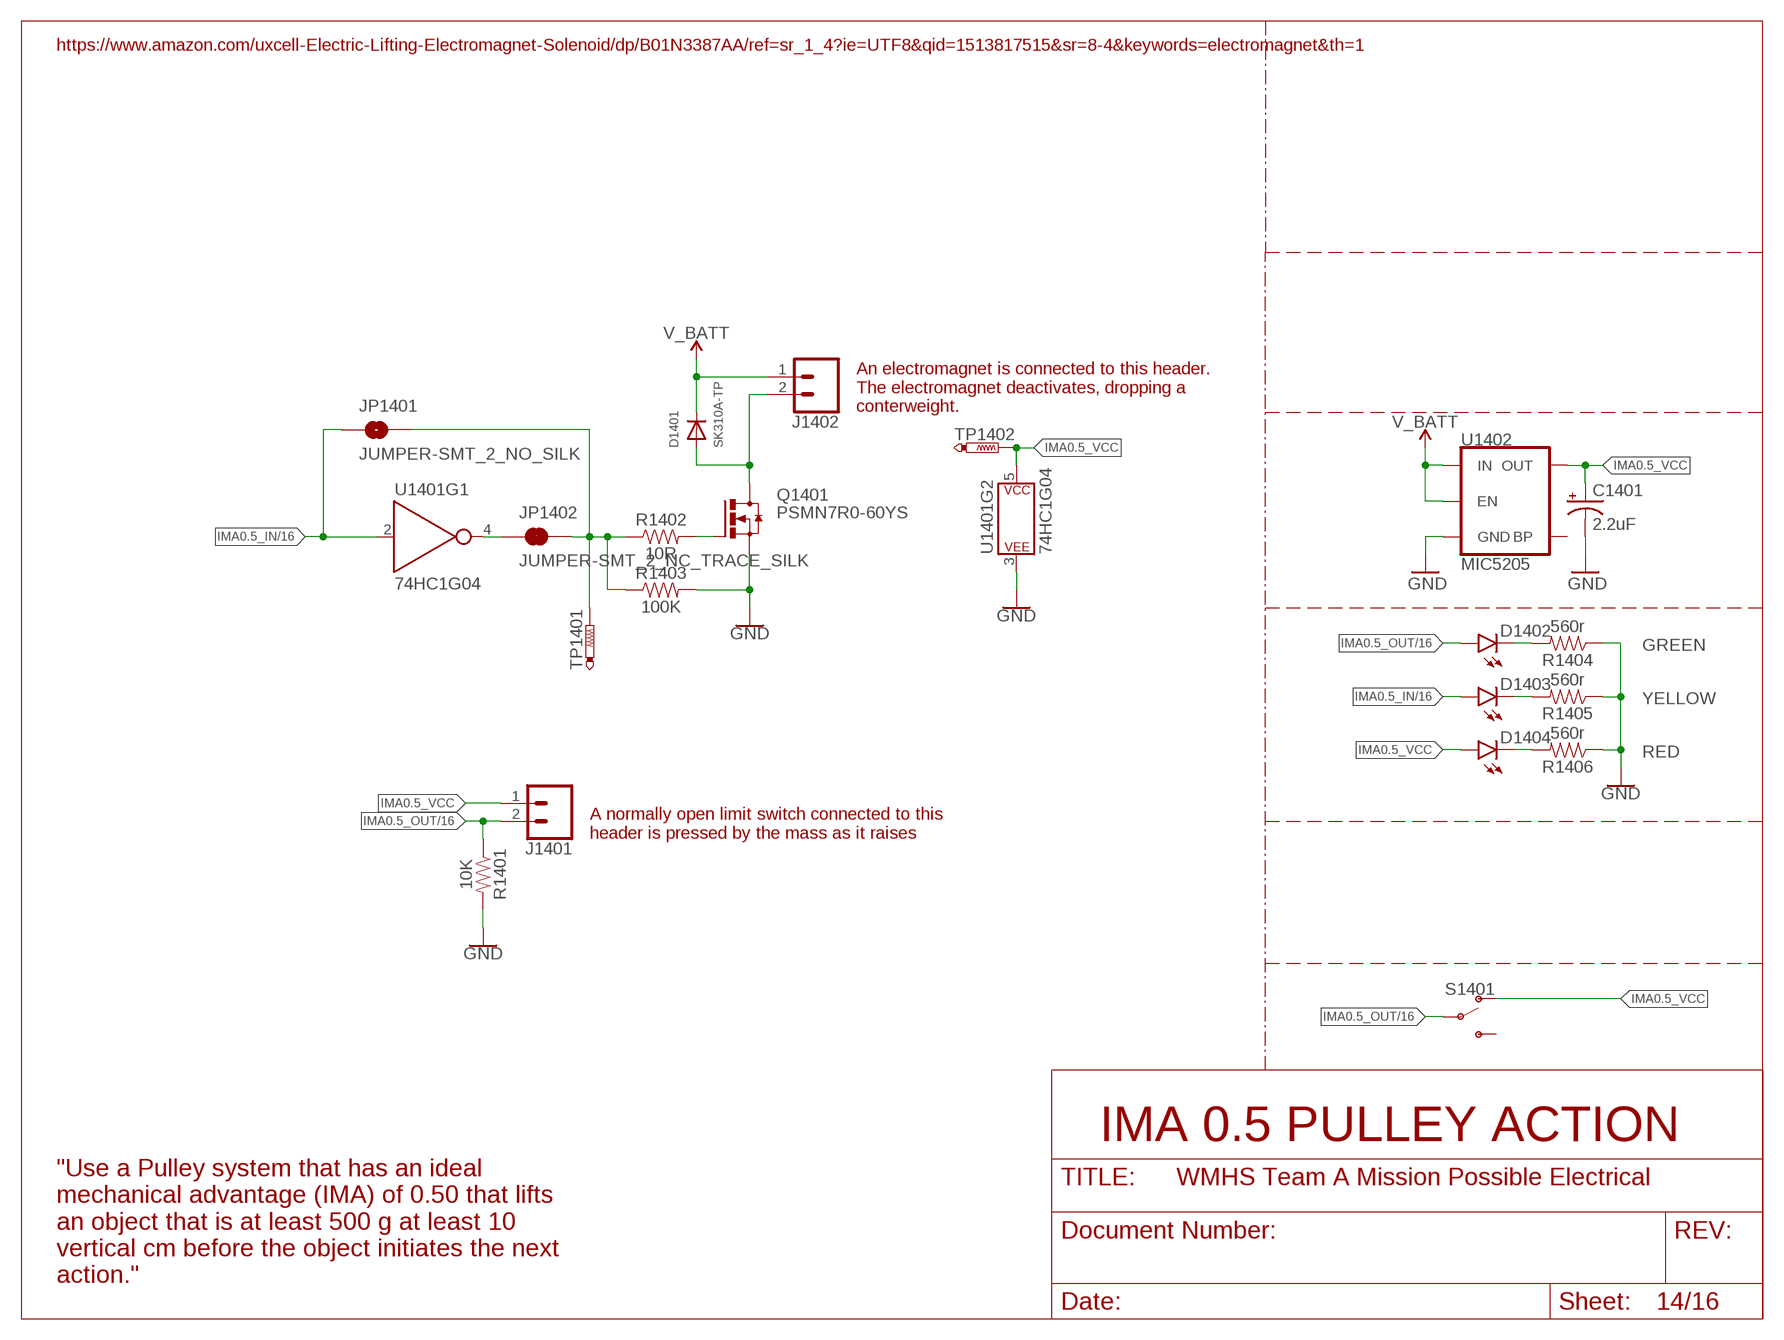
[diagram p13: schematic, sheet 14]
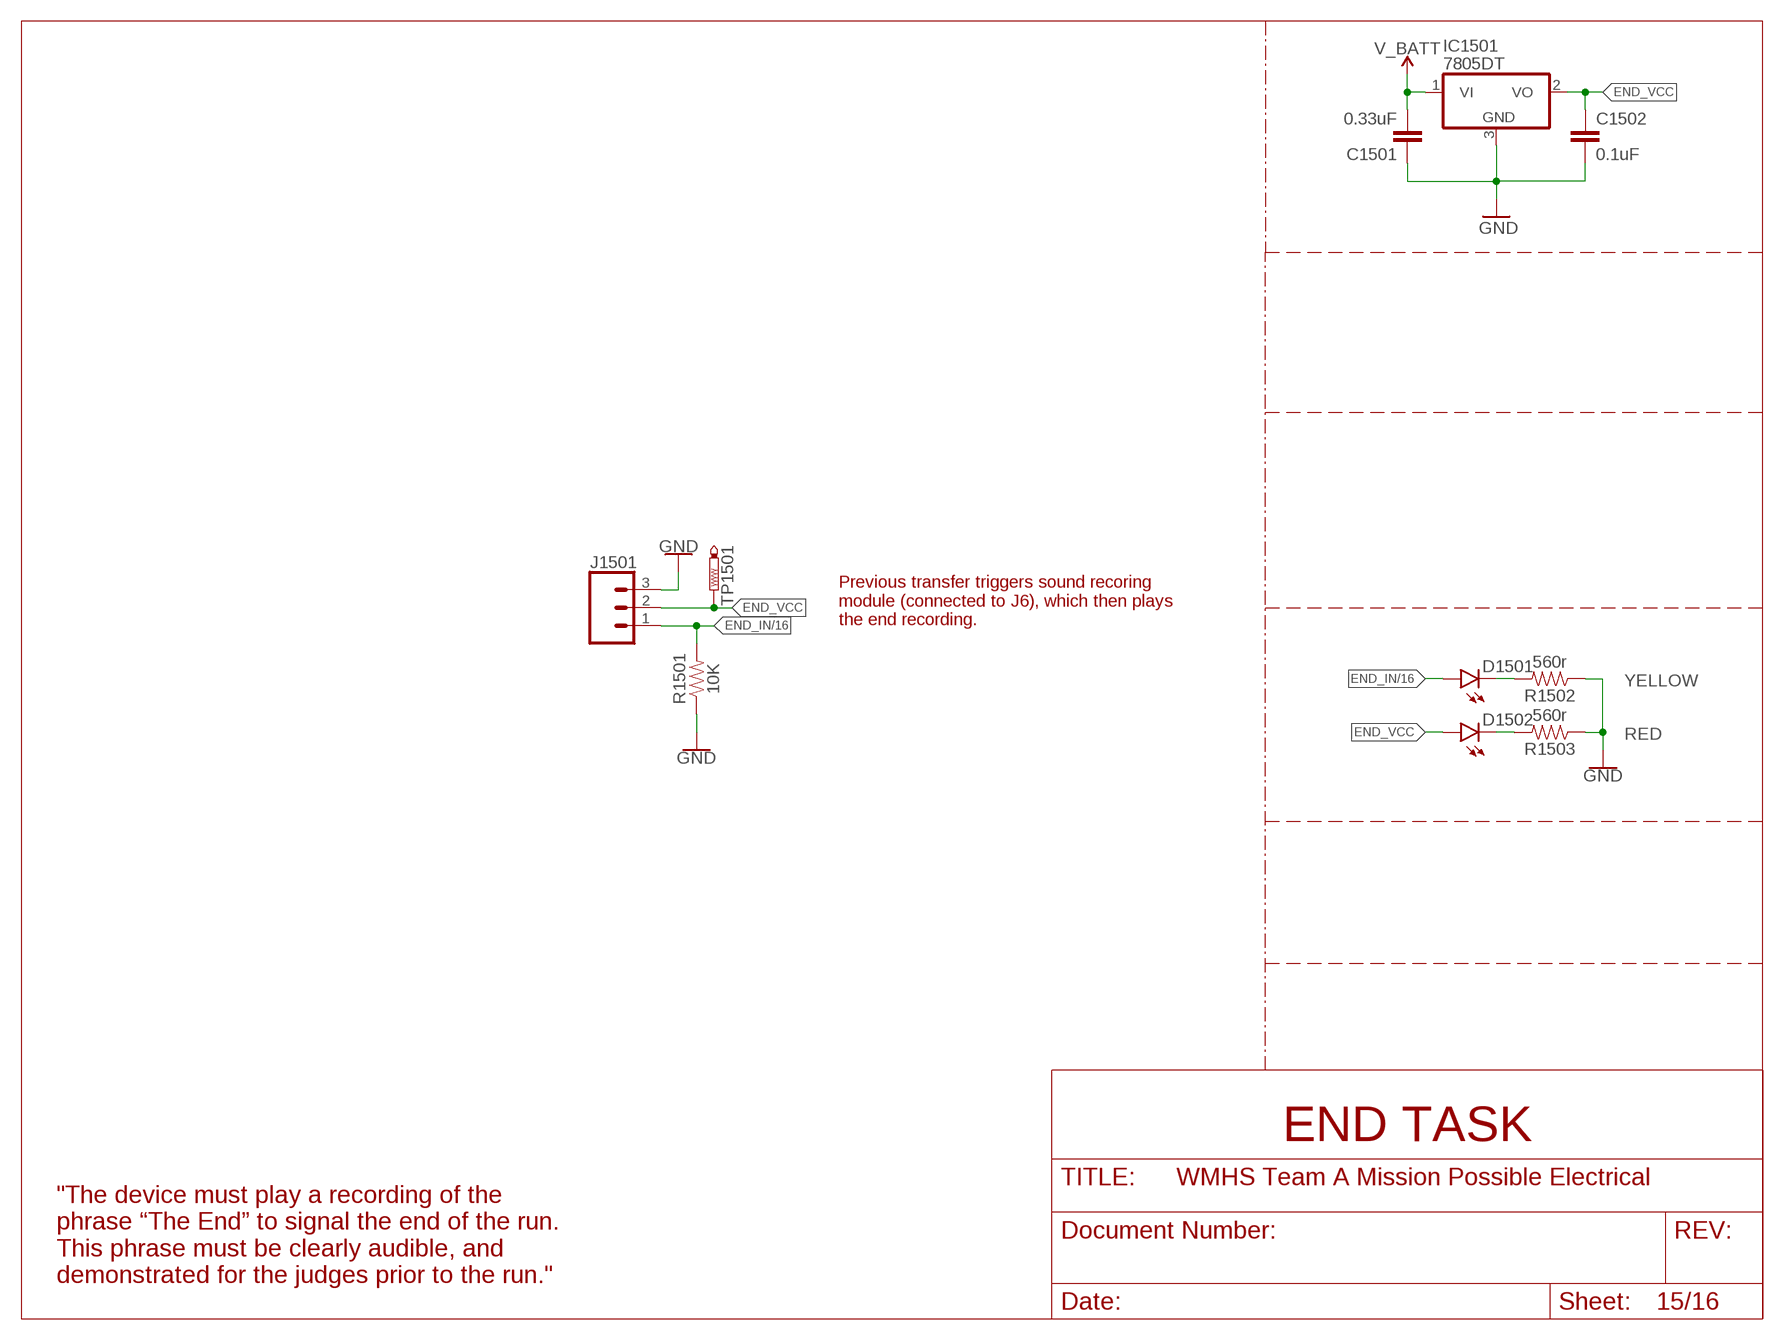
[diagram p14: schematic, sheet 15]
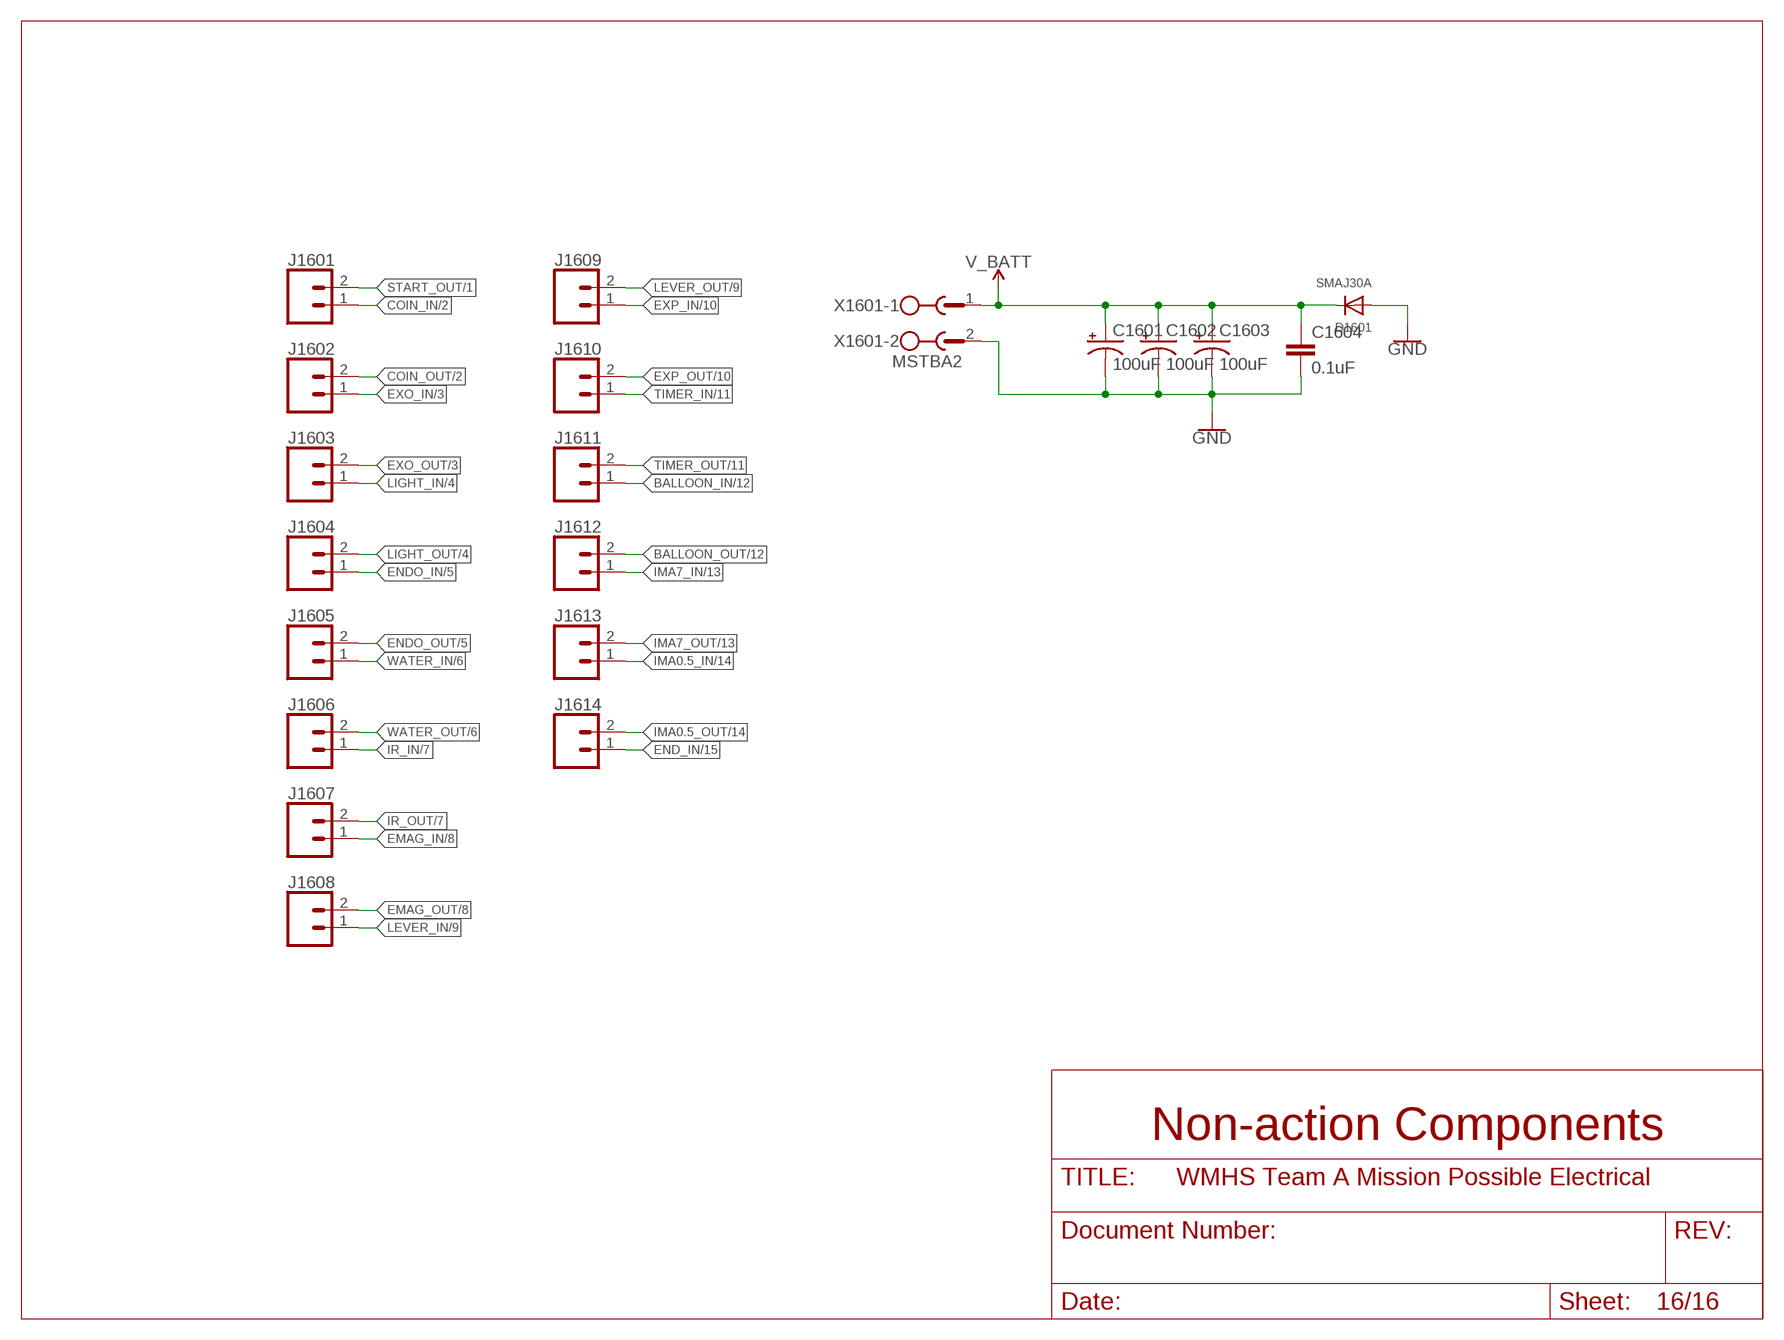
[diagram p15: schematic, sheet 16]

(export (version "E")
  (design (tool "Eeschema 10.0.6"))
  (components
    (comp (ref "C1001")
      (value "0.1uF")
      (footprint "eagle-import:0603")
      (libsource (lib "eagle-import") (part "0.1UF-0603-25V-5%"))
    )
    (comp (ref "C1002")
      (value "2.2uF")
      (footprint "eagle-import:EIA3216")
      (libsource (lib "eagle-import") (part "10UF-POLAR-EIA3216-16V-10%(TANT)"))
    )
    (comp (ref "D1001")
      (value "SK310A-TP")
      (footprint "eagle-import:SMADIODE")
      (libsource (lib "eagle-import") (part "DIODESMA"))
    )
    (comp (ref "D1002")
      (value "GREEN")
      (footprint "eagle-import:LED-0603")
      (libsource (lib "eagle-import") (part "LED-GREEN0603"))
    )
    (comp (ref "D1003")
      (value "YELLOW")
      (footprint "eagle-import:LED-0603")
      (libsource (lib "eagle-import") (part "LED-YELLOW0603"))
    )
    (comp (ref "D1004")
      (value "RED")
      (footprint "eagle-import:LED-0603")
      (libsource (lib "eagle-import") (part "LED-RED0603"))
    )
    (comp (ref "J1001")
      (value "CONN_023.5MM_LOCK")
      (footprint "eagle-import:SCREWTERMINAL-3.5MM-2_LOCK")
      (libsource (lib "eagle-import") (part "CONN_023.5MM_LOCK"))
    )
    (comp (ref "J1002")
      (value "CONN_02LOCK")
      (footprint "eagle-import:1X02_LOCK")
      (libsource (lib "eagle-import") (part "CONN_02LOCK"))
    )
    (comp (ref "J1003")
      (value "CONN_02LOCK")
      (footprint "eagle-import:1X02_LOCK")
      (libsource (lib "eagle-import") (part "CONN_02LOCK"))
    )
    (comp (ref "J1004")
      (value "CONN_02LOCK")
      (footprint "eagle-import:1X02_LOCK")
      (libsource (lib "eagle-import") (part "CONN_02LOCK"))
    )
    (comp (ref "J1005")
      (value "ICSP_HEADER")
      (footprint "eagle-import:2X3")
      (libsource (lib "eagle-import") (part "AVR_SPI_PROG_3X2PTH"))
    )
    (comp (ref "Q1001")
      (value "PSMN7R0-60YS")
      (footprint "eagle-import:SOT669")
      (libsource (lib "eagle-import") (part "PSMN7R0-60YS"))
    )
    (comp (ref "R1001")
      (value "10R")
      (footprint "eagle-import:0603")
      (libsource (lib "eagle-import") (part "RESISTOR0603"))
    )
    (comp (ref "R1002")
      (value "100K")
      (footprint "eagle-import:0603")
      (libsource (lib "eagle-import") (part "RESISTOR0603"))
    )
    (comp (ref "R1003")
      (value "100K")
      (footprint "eagle-import:0603")
      (libsource (lib "eagle-import") (part "RESISTOR0603"))
    )
    (comp (ref "R1004")
      (value "10K")
      (footprint "eagle-import:0603")
      (libsource (lib "eagle-import") (part "RESISTOR0603"))
    )
    (comp (ref "R1005")
      (value "10K")
      (footprint "eagle-import:0603")
      (libsource (lib "eagle-import") (part "330OHM-0603-1/10W-1%"))
    )
    (comp (ref "R1006")
      (value "560r")
      (footprint "eagle-import:0603")
      (libsource (lib "eagle-import") (part "330OHM-0603-1/10W-1%"))
    )
    (comp (ref "R1007")
      (value "560r")
      (footprint "eagle-import:0603")
      (libsource (lib "eagle-import") (part "330OHM-0603-1/10W-1%"))
    )
    (comp (ref "R1008")
      (value "560r")
      (footprint "eagle-import:0603")
      (libsource (lib "eagle-import") (part "330OHM-0603-1/10W-1%"))
    )
    (comp (ref "S1001")
      (value "RST")
      (footprint "eagle-import:TACTILE_SWITCH_SMD_5.2MM")
      (libsource (lib "eagle-import") (part "MOMENTARY-SWITCH-SPST-SMD-5.2-REDUNDANT"))
    )
    (comp (ref "S1002")
      (value "SWITCH-SPDT-SMD-AYZ0202")
      (footprint "eagle-import:SWITCH_DPDT_SMD_AYZ0202")
      (libsource (lib "eagle-import") (part "SWITCH-SPDT-SMD-AYZ0202"))
    )
    (comp (ref "TP1001")
      (value "PTR1TP20R")
      (footprint "eagle-import:TP20R")
      (libsource (lib "eagle-import") (part "PTR1TP20R"))
    )
    (comp (ref "TP1002")
      (value "PTR1TP20R")
      (footprint "eagle-import:TP20R")
      (libsource (lib "eagle-import") (part "PTR1TP20R"))
    )
    (comp (ref "U1001")
      (value "ATTINY25-20SSUR")
      (footprint "eagle-import:SOIC8")
      (libsource (lib "eagle-import") (part "ATTINY45-SMT-NARROW"))
    )
    (comp (ref "U1002")
      (value "MIC5205")
      (footprint "eagle-import:SOT23-5")
      (libsource (lib "eagle-import") (part "V_REG_MIC52055V"))
    )
    (comp (ref "C301")
      (value "0.1uF")
      (footprint "eagle-import:0603")
      (libsource (lib "eagle-import") (part "0.1UF-0603-25V-5%"))
    )
    (comp (ref "C302")
      (value "2.2uF")
      (footprint "eagle-import:EIA3216")
      (libsource (lib "eagle-import") (part "10UF-POLAR-EIA3216-16V-10%(TANT)"))
    )
    (comp (ref "D301")
      (value "INCANDESCENT")
      (footprint "eagle-import:LED_3MM")
      (libsource (lib "eagle-import") (part "LED3MM"))
    )
    (comp (ref "D302")
      (value "GREEN")
      (footprint "eagle-import:LED-0603")
      (libsource (lib "eagle-import") (part "LED-GREEN0603"))
    )
    (comp (ref "D303")
      (value "YELLOW")
      (footprint "eagle-import:LED-0603")
      (libsource (lib "eagle-import") (part "LED-YELLOW0603"))
    )
    (comp (ref "D304")
      (value "RED")
      (footprint "eagle-import:LED-0603")
      (libsource (lib "eagle-import") (part "LED-RED0603"))
    )
    (comp (ref "J301")
      (value "ICSP_HEADER")
      (footprint "eagle-import:2X3")
      (libsource (lib "eagle-import") (part "AVR_SPI_PROG_3X2PTH"))
    )
    (comp (ref "Q301")
      (value "500mA/300V")
      (footprint "eagle-import:SOT23-3")
      (libsource (lib "eagle-import") (part "TRANS_NPN-MMBTA42"))
    )
    (comp (ref "R301")
      (value "10K")
      (footprint "eagle-import:0603")
      (libsource (lib "eagle-import") (part "RESISTOR0603"))
    )
    (comp (ref "R302")
      (value "1K")
      (footprint "eagle-import:0603")
      (libsource (lib "eagle-import") (part "RESISTOR0603"))
    )
    (comp (ref "R303")
      (value "PHOTOCELLPTH")
      (footprint "eagle-import:PHOTOCELL")
      (libsource (lib "eagle-import") (part "PHOTOCELLPTH"))
    )
    (comp (ref "R304")
      (value "10K")
      (footprint "eagle-import:0603")
      (libsource (lib "eagle-import") (part "330OHM-0603-1/10W-1%"))
    )
    (comp (ref "R305")
      (value "560r")
      (footprint "eagle-import:0603")
      (libsource (lib "eagle-import") (part "330OHM-0603-1/10W-1%"))
    )
    (comp (ref "R306")
      (value "560r")
      (footprint "eagle-import:0603")
      (libsource (lib "eagle-import") (part "330OHM-0603-1/10W-1%"))
    )
    (comp (ref "R307")
      (value "560r")
      (footprint "eagle-import:0603")
      (libsource (lib "eagle-import") (part "330OHM-0603-1/10W-1%"))
    )
    (comp (ref "S301")
      (value "RST")
      (footprint "eagle-import:TACTILE_SWITCH_SMD_5.2MM")
      (libsource (lib "eagle-import") (part "MOMENTARY-SWITCH-SPST-SMD-5.2-REDUNDANT"))
    )
    (comp (ref "S302")
      (value "SWITCH-SPDT-SMD-AYZ0202")
      (footprint "eagle-import:SWITCH_DPDT_SMD_AYZ0202")
      (libsource (lib "eagle-import") (part "SWITCH-SPDT-SMD-AYZ0202"))
    )
    (comp (ref "TP301")
      (value "PTR1TP20R")
      (footprint "eagle-import:TP20R")
      (libsource (lib "eagle-import") (part "PTR1TP20R"))
    )
    (comp (ref "TP302")
      (value "PTR1TP20R")
      (footprint "eagle-import:TP20R")
      (libsource (lib "eagle-import") (part "PTR1TP20R"))
    )
    (comp (ref "TP303")
      (value "PTR1TP20R")
      (footprint "eagle-import:TP20R")
      (libsource (lib "eagle-import") (part "PTR1TP20R"))
    )
    (comp (ref "U301")
      (value "74HC1G04")
      (footprint "eagle-import:SOT353")
      (libsource (lib "eagle-import") (part "741G04HC"))
    )
    (comp (ref "U302")
      (value "SN74C1G08-DCK")
      (footprint "eagle-import:SC-70-5")
      (libsource (lib "eagle-import") (part "SN74C1G08-DCK"))
    )
    (comp (ref "U303")
      (value "ATTINY25-20SSUR")
      (footprint "eagle-import:SOIC8")
      (libsource (lib "eagle-import") (part "ATTINY45-SMT-NARROW"))
    )
    (comp (ref "U304")
      (value "MIC5205")
      (footprint "eagle-import:SOT23-5")
      (libsource (lib "eagle-import") (part "V_REG_MIC52055V"))
    )
    (comp (ref "C1501")
      (value "0.33uF")
      (footprint "eagle-import:0603")
      (libsource (lib "eagle-import") (part "0.1UF-0603-25V-(+80/-20%)"))
    )
    (comp (ref "C1502")
      (value "0.1uF")
      (footprint "eagle-import:0603")
      (libsource (lib "eagle-import") (part "0.1UF-0603-25V-(+80/-20%)"))
    )
    (comp (ref "D1501")
      (value "YELLOW")
      (footprint "eagle-import:LED-0603")
      (libsource (lib "eagle-import") (part "LED-YELLOW0603"))
    )
    (comp (ref "D1502")
      (value "RED")
      (footprint "eagle-import:LED-0603")
      (libsource (lib "eagle-import") (part "LED-RED0603"))
    )
    (comp (ref "IC1501")
      (value "7805DT")
      (footprint "eagle-import:TO252")
      (libsource (lib "eagle-import") (part "78DT05"))
    )
    (comp (ref "J1501")
      (value "CONN_03LOCK")
      (footprint "eagle-import:1X03_LOCK")
      (libsource (lib "eagle-import") (part "CONN_03LOCK"))
    )
    (comp (ref "R1501")
      (value "10K")
      (footprint "eagle-import:0603")
      (libsource (lib "eagle-import") (part "RESISTOR0603"))
    )
    (comp (ref "R1502")
      (value "560r")
      (footprint "eagle-import:0603")
      (libsource (lib "eagle-import") (part "330OHM-0603-1/10W-1%"))
    )
    (comp (ref "R1503")
      (value "560r")
      (footprint "eagle-import:0603")
      (libsource (lib "eagle-import") (part "330OHM-0603-1/10W-1%"))
    )
    (comp (ref "TP1501")
      (value "PTR1TP20R")
      (footprint "eagle-import:TP20R")
      (libsource (lib "eagle-import") (part "PTR1TP20R"))
    )
    (comp (ref "C801")
      (value "2.2uF")
      (footprint "eagle-import:EIA3216")
      (libsource (lib "eagle-import") (part "10UF-POLAR-EIA3216-16V-10%(TANT)"))
    )
    (comp (ref "D801")
      (value "SK310A-TP")
      (footprint "eagle-import:SMADIODE")
      (libsource (lib "eagle-import") (part "DIODESMA"))
    )
    (comp (ref "D802")
      (value "GREEN")
      (footprint "eagle-import:LED-0603")
      (libsource (lib "eagle-import") (part "LED-GREEN0603"))
    )
    (comp (ref "D803")
      (value "YELLOW")
      (footprint "eagle-import:LED-0603")
      (libsource (lib "eagle-import") (part "LED-YELLOW0603"))
    )
    (comp (ref "D804")
      (value "RED")
      (footprint "eagle-import:LED-0603")
      (libsource (lib "eagle-import") (part "LED-RED0603"))
    )
    (comp (ref "J801")
      (value "CONN_02LOCK")
      (footprint "eagle-import:1X02_LOCK")
      (libsource (lib "eagle-import") (part "CONN_02LOCK"))
    )
    (comp (ref "J802")
      (value "CONN_023.5MM_LOCK")
      (footprint "eagle-import:SCREWTERMINAL-3.5MM-2_LOCK")
      (libsource (lib "eagle-import") (part "CONN_023.5MM_LOCK"))
    )
    (comp (ref "Q801")
      (value "PSMN7R0-60YS")
      (footprint "eagle-import:SOT669")
      (libsource (lib "eagle-import") (part "PSMN7R0-60YS"))
    )
    (comp (ref "R801")
      (value "10K")
      (footprint "eagle-import:0603")
      (libsource (lib "eagle-import") (part "RESISTOR0603"))
    )
    (comp (ref "R802")
      (value "10R")
      (footprint "eagle-import:0603")
      (libsource (lib "eagle-import") (part "RESISTOR0603"))
    )
    (comp (ref "R803")
      (value "100K")
      (footprint "eagle-import:0603")
      (libsource (lib "eagle-import") (part "RESISTOR0603"))
    )
    (comp (ref "R804")
      (value "560r")
      (footprint "eagle-import:0603")
      (libsource (lib "eagle-import") (part "330OHM-0603-1/10W-1%"))
    )
    (comp (ref "R805")
      (value "560r")
      (footprint "eagle-import:0603")
      (libsource (lib "eagle-import") (part "330OHM-0603-1/10W-1%"))
    )
    (comp (ref "R806")
      (value "560r")
      (footprint "eagle-import:0603")
      (libsource (lib "eagle-import") (part "330OHM-0603-1/10W-1%"))
    )
    (comp (ref "S801")
      (value "SWITCH-SPDT-SMD-AYZ0202")
      (footprint "eagle-import:SWITCH_DPDT_SMD_AYZ0202")
      (libsource (lib "eagle-import") (part "SWITCH-SPDT-SMD-AYZ0202"))
    )
    (comp (ref "TP801")
      (value "PTR1TP20R")
      (footprint "eagle-import:TP20R")
      (libsource (lib "eagle-import") (part "PTR1TP20R"))
    )
    (comp (ref "TP802")
      (value "PTR1TP20R")
      (footprint "eagle-import:TP20R")
      (libsource (lib "eagle-import") (part "PTR1TP20R"))
    )
    (comp (ref "TP803")
      (value "PTR1TP20R")
      (footprint "eagle-import:TP20R")
      (libsource (lib "eagle-import") (part "PTR1TP20R"))
    )
    (comp (ref "U801")
      (value "74HC1G04")
      (footprint "eagle-import:SOT353")
      (libsource (lib "eagle-import") (part "741G04HC"))
    )
    (comp (ref "U802")
      (value "SN74C1G08-DCK")
      (footprint "eagle-import:SC-70-5")
      (libsource (lib "eagle-import") (part "SN74C1G08-DCK"))
    )
    (comp (ref "U803")
      (value "MIC5205")
      (footprint "eagle-import:SOT23-5")
      (libsource (lib "eagle-import") (part "V_REG_MIC52055V"))
    )
    (comp (ref "C401")
      (value "0.1uF")
      (footprint "eagle-import:0603")
      (libsource (lib "eagle-import") (part "0.1UF-0603-25V-5%"))
    )
    (comp (ref "C402")
      (value "2.2uF")
      (footprint "eagle-import:EIA3216")
      (libsource (lib "eagle-import") (part "10UF-POLAR-EIA3216-16V-10%(TANT)"))
    )
    (comp (ref "D401")
      (value "WHITE")
      (footprint "eagle-import:LED_3MM")
      (libsource (lib "eagle-import") (part "LED3MM"))
    )
    (comp (ref "D402")
      (value "GREEN")
      (footprint "eagle-import:LED-0603")
      (libsource (lib "eagle-import") (part "LED-GREEN0603"))
    )
    (comp (ref "D403")
      (value "YELLOW")
      (footprint "eagle-import:LED-0603")
      (libsource (lib "eagle-import") (part "LED-YELLOW0603"))
    )
    (comp (ref "D404")
      (value "RED")
      (footprint "eagle-import:LED-0603")
      (libsource (lib "eagle-import") (part "LED-RED0603"))
    )
    (comp (ref "J401")
      (value "ICSP_HEADER")
      (footprint "eagle-import:2X3")
      (libsource (lib "eagle-import") (part "AVR_SPI_PROG_3X2PTH"))
    )
    (comp (ref "Q401")
      (value "500mA/300V")
      (footprint "eagle-import:SOT23-3")
      (libsource (lib "eagle-import") (part "TRANS_NPN-MMBTA42"))
    )
    (comp (ref "R401")
      (value "10K")
      (footprint "eagle-import:0603")
      (libsource (lib "eagle-import") (part "RESISTOR0603"))
    )
    (comp (ref "R402")
      (value "PHOTOCELLPTH")
      (footprint "eagle-import:PHOTOCELL")
      (libsource (lib "eagle-import") (part "PHOTOCELLPTH"))
    )
    (comp (ref "R403")
      (value "1K")
      (footprint "eagle-import:0603")
      (libsource (lib "eagle-import") (part "RESISTOR0603"))
    )
    (comp (ref "R404")
      (value "560")
      (footprint "eagle-import:0603")
      (libsource (lib "eagle-import") (part "RESISTOR0603"))
    )
    (comp (ref "R405")
      (value "10K")
      (footprint "eagle-import:0603")
      (libsource (lib "eagle-import") (part "330OHM-0603-1/10W-1%"))
    )
    (comp (ref "R406")
      (value "560r")
      (footprint "eagle-import:0603")
      (libsource (lib "eagle-import") (part "330OHM-0603-1/10W-1%"))
    )
    (comp (ref "R407")
      (value "560r")
      (footprint "eagle-import:0603")
      (libsource (lib "eagle-import") (part "330OHM-0603-1/10W-1%"))
    )
    (comp (ref "R408")
      (value "560r")
      (footprint "eagle-import:0603")
      (libsource (lib "eagle-import") (part "330OHM-0603-1/10W-1%"))
    )
    (comp (ref "S401")
      (value "RST")
      (footprint "eagle-import:TACTILE_SWITCH_SMD_5.2MM")
      (libsource (lib "eagle-import") (part "MOMENTARY-SWITCH-SPST-SMD-5.2-REDUNDANT"))
    )
    (comp (ref "S402")
      (value "SWITCH-SPDT-SMD-AYZ0202")
      (footprint "eagle-import:SWITCH_DPDT_SMD_AYZ0202")
      (libsource (lib "eagle-import") (part "SWITCH-SPDT-SMD-AYZ0202"))
    )
    (comp (ref "TP401")
      (value "PTR1TP20R")
      (footprint "eagle-import:TP20R")
      (libsource (lib "eagle-import") (part "PTR1TP20R"))
    )
    (comp (ref "TP402")
      (value "PTR1TP20R")
      (footprint "eagle-import:TP20R")
      (libsource (lib "eagle-import") (part "PTR1TP20R"))
    )
    (comp (ref "TP403")
      (value "PTR1TP20R")
      (footprint "eagle-import:TP20R")
      (libsource (lib "eagle-import") (part "PTR1TP20R"))
    )
    (comp (ref "TP404")
      (value "PTR1TP20R")
      (footprint "eagle-import:TP20R")
      (libsource (lib "eagle-import") (part "PTR1TP20R"))
    )
    (comp (ref "U401")
      (value "74HC1G04")
      (footprint "eagle-import:SOT353")
      (libsource (lib "eagle-import") (part "741G04HC"))
    )
    (comp (ref "U402")
      (value "SN74C1G08-DCK")
      (footprint "eagle-import:SC-70-5")
      (libsource (lib "eagle-import") (part "SN74C1G08-DCK"))
    )
    (comp (ref "U403")
      (value "ATTINY25-20SSUR")
      (footprint "eagle-import:SOIC8")
      (libsource (lib "eagle-import") (part "ATTINY45-SMT-NARROW"))
    )
    (comp (ref "U404")
      (value "MIC5205")
      (footprint "eagle-import:SOT23-5")
      (libsource (lib "eagle-import") (part "V_REG_MIC52055V"))
    )
    (comp (ref "C501")
      (value "0.1uF")
      (footprint "eagle-import:0603")
      (libsource (lib "eagle-import") (part "0.1UF-0603-25V-5%"))
    )
    (comp (ref "C502")
      (value "2.2uF")
      (footprint "eagle-import:EIA3216")
      (libsource (lib "eagle-import") (part "10UF-POLAR-EIA3216-16V-10%(TANT)"))
    )
    (comp (ref "D501")
      (value "SK310A-TP")
      (footprint "eagle-import:SMADIODE")
      (libsource (lib "eagle-import") (part "DIODESMA"))
    )
    (comp (ref "D502")
      (value "GREEN")
      (footprint "eagle-import:LED-0603")
      (libsource (lib "eagle-import") (part "LED-GREEN0603"))
    )
    (comp (ref "D503")
      (value "YELLOW")
      (footprint "eagle-import:LED-0603")
      (libsource (lib "eagle-import") (part "LED-YELLOW0603"))
    )
    (comp (ref "D504")
      (value "RED")
      (footprint "eagle-import:LED-0603")
      (libsource (lib "eagle-import") (part "LED-RED0603"))
    )
    (comp (ref "J501")
      (value "CONN_02LOCK")
      (footprint "eagle-import:1X02_LOCK")
      (libsource (lib "eagle-import") (part "CONN_02LOCK"))
    )
    (comp (ref "J502")
      (value "CONN_023.5MM_LOCK")
      (footprint "eagle-import:SCREWTERMINAL-3.5MM-2_LOCK")
      (libsource (lib "eagle-import") (part "CONN_023.5MM_LOCK"))
    )
    (comp (ref "J503")
      (value "ICSP_HEADER")
      (footprint "eagle-import:2X3")
      (libsource (lib "eagle-import") (part "AVR_SPI_PROG_3X2PTH"))
    )
    (comp (ref "Q501")
      (value "PSMN7R0-60YS")
      (footprint "eagle-import:SOT669")
      (libsource (lib "eagle-import") (part "PSMN7R0-60YS"))
    )
    (comp (ref "R501")
      (value "0R")
      (footprint "eagle-import:0603")
      (libsource (lib "eagle-import") (part "RESISTOR0603"))
    )
    (comp (ref "R502")
      (value "10R")
      (footprint "eagle-import:0603")
      (libsource (lib "eagle-import") (part "RESISTOR0603"))
    )
    (comp (ref "R503")
      (value "100K")
      (footprint "eagle-import:0603")
      (libsource (lib "eagle-import") (part "RESISTOR0603"))
    )
    (comp (ref "R504")
      (value "10K")
      (footprint "eagle-import:0603")
      (libsource (lib "eagle-import") (part "330OHM-0603-1/10W-1%"))
    )
    (comp (ref "R505")
      (value "560r")
      (footprint "eagle-import:0603")
      (libsource (lib "eagle-import") (part "330OHM-0603-1/10W-1%"))
    )
    (comp (ref "R506")
      (value "560r")
      (footprint "eagle-import:0603")
      (libsource (lib "eagle-import") (part "330OHM-0603-1/10W-1%"))
    )
    (comp (ref "R507")
      (value "560r")
      (footprint "eagle-import:0603")
      (libsource (lib "eagle-import") (part "330OHM-0603-1/10W-1%"))
    )
    (comp (ref "S501")
      (value "RST")
      (footprint "eagle-import:TACTILE_SWITCH_SMD_5.2MM")
      (libsource (lib "eagle-import") (part "MOMENTARY-SWITCH-SPST-SMD-5.2-REDUNDANT"))
    )
    (comp (ref "S502")
      (value "SWITCH-SPDT-SMD-AYZ0202")
      (footprint "eagle-import:SWITCH_DPDT_SMD_AYZ0202")
      (libsource (lib "eagle-import") (part "SWITCH-SPDT-SMD-AYZ0202"))
    )
    (comp (ref "TP501")
      (value "PTR1TP20R")
      (footprint "eagle-import:TP20R")
      (libsource (lib "eagle-import") (part "PTR1TP20R"))
    )
    (comp (ref "TP502")
      (value "PTR1TP20R")
      (footprint "eagle-import:TP20R")
      (libsource (lib "eagle-import") (part "PTR1TP20R"))
    )
    (comp (ref "TP503")
      (value "PTR1TP20R")
      (footprint "eagle-import:TP20R")
      (libsource (lib "eagle-import") (part "PTR1TP20R"))
    )
    (comp (ref "TP504")
      (value "PTR1TP20R")
      (footprint "eagle-import:TP20R")
      (libsource (lib "eagle-import") (part "PTR1TP20R"))
    )
    (comp (ref "U501")
      (value "74HC1G04")
      (footprint "eagle-import:SOT353")
      (libsource (lib "eagle-import") (part "741G04HC"))
    )
    (comp (ref "U502")
      (value "SN74C1G08-DCK")
      (footprint "eagle-import:SC-70-5")
      (libsource (lib "eagle-import") (part "SN74C1G08-DCK"))
    )
    (comp (ref "U503")
      (value "ATTINY25-20SSUR")
      (footprint "eagle-import:SOIC8")
      (libsource (lib "eagle-import") (part "ATTINY45-SMT-NARROW"))
    )
    (comp (ref "U504")
      (value "MIC5205")
      (footprint "eagle-import:SOT23-5")
      (libsource (lib "eagle-import") (part "V_REG_MIC52055V"))
    )
    (comp (ref "C601")
      (value "0.1uF")
      (footprint "eagle-import:0603")
      (libsource (lib "eagle-import") (part "0.1UF-0603-25V-5%"))
    )
    (comp (ref "C602")
      (value "2.2uF")
      (footprint "eagle-import:EIA3216")
      (libsource (lib "eagle-import") (part "10UF-POLAR-EIA3216-16V-10%(TANT)"))
    )
    (comp (ref "D601")
      (value "SK310A-TP")
      (footprint "eagle-import:SMADIODE")
      (libsource (lib "eagle-import") (part "DIODESMA"))
    )
    (comp (ref "D602")
      (value "GREEN")
      (footprint "eagle-import:LED-0603")
      (libsource (lib "eagle-import") (part "LED-GREEN0603"))
    )
    (comp (ref "D603")
      (value "YELLOW")
      (footprint "eagle-import:LED-0603")
      (libsource (lib "eagle-import") (part "LED-YELLOW0603"))
    )
    (comp (ref "D604")
      (value "RED")
      (footprint "eagle-import:LED-0603")
      (libsource (lib "eagle-import") (part "LED-RED0603"))
    )
    (comp (ref "J601")
      (value "CONN_02LOCK")
      (footprint "eagle-import:1X02_LOCK")
      (libsource (lib "eagle-import") (part "CONN_02LOCK"))
    )
    (comp (ref "J602")
      (value "CONN_023.5MM_LOCK")
      (footprint "eagle-import:SCREWTERMINAL-3.5MM-2_LOCK")
      (libsource (lib "eagle-import") (part "CONN_023.5MM_LOCK"))
    )
    (comp (ref "J603")
      (value "ICSP_HEADER")
      (footprint "eagle-import:2X3")
      (libsource (lib "eagle-import") (part "AVR_SPI_PROG_3X2PTH"))
    )
    (comp (ref "Q601")
      (value "PSMN7R0-60YS")
      (footprint "eagle-import:SOT669")
      (libsource (lib "eagle-import") (part "PSMN7R0-60YS"))
    )
    (comp (ref "R601")
      (value "10R")
      (footprint "eagle-import:0603")
      (libsource (lib "eagle-import") (part "RESISTOR0603"))
    )
    (comp (ref "R602")
      (value "100K")
      (footprint "eagle-import:0603")
      (libsource (lib "eagle-import") (part "RESISTOR0603"))
    )
    (comp (ref "R603")
      (value "1M")
      (footprint "eagle-import:0603")
      (libsource (lib "eagle-import") (part "RESISTOR0603"))
    )
    (comp (ref "R604")
      (value "10K")
      (footprint "eagle-import:0603")
      (libsource (lib "eagle-import") (part "330OHM-0603-1/10W-1%"))
    )
    (comp (ref "R605")
      (value "560r")
      (footprint "eagle-import:0603")
      (libsource (lib "eagle-import") (part "330OHM-0603-1/10W-1%"))
    )
    (comp (ref "R606")
      (value "560r")
      (footprint "eagle-import:0603")
      (libsource (lib "eagle-import") (part "330OHM-0603-1/10W-1%"))
    )
    (comp (ref "R607")
      (value "560r")
      (footprint "eagle-import:0603")
      (libsource (lib "eagle-import") (part "330OHM-0603-1/10W-1%"))
    )
    (comp (ref "S601")
      (value "RST")
      (footprint "eagle-import:TACTILE_SWITCH_SMD_5.2MM")
      (libsource (lib "eagle-import") (part "MOMENTARY-SWITCH-SPST-SMD-5.2-REDUNDANT"))
    )
    (comp (ref "S602")
      (value "SWITCH-SPDT-SMD-AYZ0202")
      (footprint "eagle-import:SWITCH_DPDT_SMD_AYZ0202")
      (libsource (lib "eagle-import") (part "SWITCH-SPDT-SMD-AYZ0202"))
    )
    (comp (ref "TP601")
      (value "PTR1TP20R")
      (footprint "eagle-import:TP20R")
      (libsource (lib "eagle-import") (part "PTR1TP20R"))
    )
    (comp (ref "TP602")
      (value "PTR1TP20R")
      (footprint "eagle-import:TP20R")
      (libsource (lib "eagle-import") (part "PTR1TP20R"))
    )
    (comp (ref "TP603")
      (value "PTR1TP20R")
      (footprint "eagle-import:TP20R")
      (libsource (lib "eagle-import") (part "PTR1TP20R"))
    )
    (comp (ref "TP604")
      (value "PTR1TP20R")
      (footprint "eagle-import:TP20R")
      (libsource (lib "eagle-import") (part "PTR1TP20R"))
    )
    (comp (ref "U601")
      (value "74HC1G04")
      (footprint "eagle-import:SOT353")
      (libsource (lib "eagle-import") (part "741G04HC"))
    )
    (comp (ref "U602")
      (value "SN74C1G08-DCK")
      (footprint "eagle-import:SC-70-5")
      (libsource (lib "eagle-import") (part "SN74C1G08-DCK"))
    )
    (comp (ref "U603")
      (value "ATTINY25-20SSUR")
      (footprint "eagle-import:SOIC8")
      (libsource (lib "eagle-import") (part "ATTINY45-SMT-NARROW"))
    )
    (comp (ref "U604")
      (value "MIC5205")
      (footprint "eagle-import:SOT23-5")
      (libsource (lib "eagle-import") (part "V_REG_MIC52055V"))
    )
    (comp (ref "C1601")
      (value "100uF")
      (footprint "eagle-import:PANASONIC_D")
      (libsource (lib "eagle-import") (part "100UF-POLAR-25V-20%(ELEC)"))
    )
    (comp (ref "C1602")
      (value "100uF")
      (footprint "eagle-import:PANASONIC_D")
      (libsource (lib "eagle-import") (part "100UF-POLAR-25V-20%(ELEC)"))
    )
    (comp (ref "C1603")
      (value "100uF")
      (footprint "eagle-import:PANASONIC_D")
      (libsource (lib "eagle-import") (part "100UF-POLAR-25V-20%(ELEC)"))
    )
    (comp (ref "C1604")
      (value "0.1uF")
      (footprint "eagle-import:0603")
      (libsource (lib "eagle-import") (part "0.1UF-0603-25V-5%"))
    )
    (comp (ref "D1601")
      (value "SMAJ30A")
      (footprint "eagle-import:SMADIODE")
      (libsource (lib "eagle-import") (part "DIODESMA"))
    )
    (comp (ref "J1601")
      (value "CONN_02")
      (footprint "eagle-import:1X02")
      (libsource (lib "eagle-import") (part "CONN_02"))
    )
    (comp (ref "J1602")
      (value "CONN_02")
      (footprint "eagle-import:1X02")
      (libsource (lib "eagle-import") (part "CONN_02"))
    )
    (comp (ref "J1603")
      (value "CONN_02")
      (footprint "eagle-import:1X02")
      (libsource (lib "eagle-import") (part "CONN_02"))
    )
    (comp (ref "J1604")
      (value "CONN_02")
      (footprint "eagle-import:1X02")
      (libsource (lib "eagle-import") (part "CONN_02"))
    )
    (comp (ref "J1605")
      (value "CONN_02")
      (footprint "eagle-import:1X02")
      (libsource (lib "eagle-import") (part "CONN_02"))
    )
    (comp (ref "J1606")
      (value "CONN_02")
      (footprint "eagle-import:1X02")
      (libsource (lib "eagle-import") (part "CONN_02"))
    )
    (comp (ref "J1607")
      (value "CONN_02")
      (footprint "eagle-import:1X02")
      (libsource (lib "eagle-import") (part "CONN_02"))
    )
    (comp (ref "J1608")
      (value "CONN_02")
      (footprint "eagle-import:1X02")
      (libsource (lib "eagle-import") (part "CONN_02"))
    )
    (comp (ref "J1609")
      (value "CONN_02")
      (footprint "eagle-import:1X02")
      (libsource (lib "eagle-import") (part "CONN_02"))
    )
    (comp (ref "J1610")
      (value "CONN_02")
      (footprint "eagle-import:1X02")
      (libsource (lib "eagle-import") (part "CONN_02"))
    )
    (comp (ref "J1611")
      (value "CONN_02")
      (footprint "eagle-import:1X02")
      (libsource (lib "eagle-import") (part "CONN_02"))
    )
    (comp (ref "J1612")
      (value "CONN_02")
      (footprint "eagle-import:1X02")
      (libsource (lib "eagle-import") (part "CONN_02"))
    )
    (comp (ref "J1613")
      (value "CONN_02")
      (footprint "eagle-import:1X02")
      (libsource (lib "eagle-import") (part "CONN_02"))
    )
    (comp (ref "J1614")
      (value "CONN_02")
      (footprint "eagle-import:1X02")
      (libsource (lib "eagle-import") (part "CONN_02"))
    )
    (comp (ref "X1601")
      (value "MSTBA2")
      (footprint "eagle-import:MSTBA2")
      (fields (field (name "MF") "FARNELL") (field (name "MPN") "1757242"))
      (libsource (lib "eagle-import") (part "MSTBA2"))
    )
    (comp (ref "C1401")
      (value "2.2uF")
      (footprint "eagle-import:EIA3216")
      (libsource (lib "eagle-import") (part "10UF-POLAR-EIA3216-16V-10%(TANT)"))
    )
    (comp (ref "D1401")
      (value "SK310A-TP")
      (footprint "eagle-import:SMADIODE")
      (libsource (lib "eagle-import") (part "DIODESMA"))
    )
    (comp (ref "D1402")
      (value "GREEN")
      (footprint "eagle-import:LED-0603")
      (libsource (lib "eagle-import") (part "LED-GREEN0603"))
    )
    (comp (ref "D1403")
      (value "YELLOW")
      (footprint "eagle-import:LED-0603")
      (libsource (lib "eagle-import") (part "LED-YELLOW0603"))
    )
    (comp (ref "D1404")
      (value "RED")
      (footprint "eagle-import:LED-0603")
      (libsource (lib "eagle-import") (part "LED-RED0603"))
    )
    (comp (ref "J1401")
      (value "CONN_02LOCK")
      (footprint "eagle-import:1X02_LOCK")
      (libsource (lib "eagle-import") (part "CONN_02LOCK"))
    )
    (comp (ref "J1402")
      (value "CONN_023.5MM_LOCK")
      (footprint "eagle-import:SCREWTERMINAL-3.5MM-2_LOCK")
      (libsource (lib "eagle-import") (part "CONN_023.5MM_LOCK"))
    )
    (comp (ref "JP1401")
      (value "JUMPER-SMT_2_NO_SILK")
      (footprint "eagle-import:SMT-JUMPER_2_NO_SILK")
      (libsource (lib "eagle-import") (part "JUMPER-SMT_2_NO_SILK"))
    )
    (comp (ref "JP1402")
      (value "JUMPER-SMT_2_NC_TRACE_SILK")
      (footprint "eagle-import:SMT-JUMPER_2_NC_TRACE_SILK")
      (libsource (lib "eagle-import") (part "JUMPER-SMT_2_NC_TRACE_SILK"))
    )
    (comp (ref "Q1401")
      (value "PSMN7R0-60YS")
      (footprint "eagle-import:SOT669")
      (libsource (lib "eagle-import") (part "PSMN7R0-60YS"))
    )
    (comp (ref "R1401")
      (value "10K")
      (footprint "eagle-import:0603")
      (libsource (lib "eagle-import") (part "RESISTOR0603"))
    )
    (comp (ref "R1402")
      (value "10R")
      (footprint "eagle-import:0603")
      (libsource (lib "eagle-import") (part "RESISTOR0603"))
    )
    (comp (ref "R1403")
      (value "100K")
      (footprint "eagle-import:0603")
      (libsource (lib "eagle-import") (part "RESISTOR0603"))
    )
    (comp (ref "R1404")
      (value "560r")
      (footprint "eagle-import:0603")
      (libsource (lib "eagle-import") (part "330OHM-0603-1/10W-1%"))
    )
    (comp (ref "R1405")
      (value "560r")
      (footprint "eagle-import:0603")
      (libsource (lib "eagle-import") (part "330OHM-0603-1/10W-1%"))
    )
    (comp (ref "R1406")
      (value "560r")
      (footprint "eagle-import:0603")
      (libsource (lib "eagle-import") (part "330OHM-0603-1/10W-1%"))
    )
    (comp (ref "S1401")
      (value "SWITCH-SPDT-SMD-AYZ0202")
      (footprint "eagle-import:SWITCH_DPDT_SMD_AYZ0202")
      (libsource (lib "eagle-import") (part "SWITCH-SPDT-SMD-AYZ0202"))
    )
    (comp (ref "TP1401")
      (value "PTR1TP20R")
      (footprint "eagle-import:TP20R")
      (libsource (lib "eagle-import") (part "PTR1TP20R"))
    )
    (comp (ref "TP1402")
      (value "PTR1TP20R")
      (footprint "eagle-import:TP20R")
      (libsource (lib "eagle-import") (part "PTR1TP20R"))
    )
    (comp (ref "U1401")
      (value "74HC1G04")
      (footprint "eagle-import:SOT353")
      (libsource (lib "eagle-import") (part "741G04HC"))
    )
    (comp (ref "U1402")
      (value "MIC5205")
      (footprint "eagle-import:SOT23-5")
      (libsource (lib "eagle-import") (part "V_REG_MIC52055V"))
    )
    (comp (ref "C1101")
      (value "0.1uF")
      (footprint "eagle-import:0603")
      (libsource (lib "eagle-import") (part "0.1UF-0603-25V-5%"))
    )
    (comp (ref "C1102")
      (value "0.33uF")
      (footprint "eagle-import:0603")
      (libsource (lib "eagle-import") (part "0.1UF-0603-25V-(+80/-20%)"))
    )
    (comp (ref "C1103")
      (value "0.1uF")
      (footprint "eagle-import:0603")
      (libsource (lib "eagle-import") (part "0.1UF-0603-100V-10%"))
    )
    (comp (ref "D1101")
      (value "GREEN")
      (footprint "eagle-import:LED-0603")
      (libsource (lib "eagle-import") (part "LED-GREEN0603"))
    )
    (comp (ref "D1102")
      (value "YELLOW")
      (footprint "eagle-import:LED-0603")
      (libsource (lib "eagle-import") (part "LED-YELLOW0603"))
    )
    (comp (ref "D1103")
      (value "RED")
      (footprint "eagle-import:LED-0603")
      (libsource (lib "eagle-import") (part "LED-RED0603"))
    )
    (comp (ref "IC1101")
      (value "7805DT")
      (footprint "eagle-import:TO252")
      (libsource (lib "eagle-import") (part "78DT05"))
    )
    (comp (ref "J1101")
      (value "CONN_02LOCK")
      (footprint "eagle-import:1X02_LOCK")
      (libsource (lib "eagle-import") (part "CONN_02LOCK"))
    )
    (comp (ref "J1102")
      (value "CONN_02LOCK")
      (footprint "eagle-import:1X02_LOCK")
      (libsource (lib "eagle-import") (part "CONN_02LOCK"))
    )
    (comp (ref "J1103")
      (value "CONN_02LOCK")
      (footprint "eagle-import:1X02_LOCK")
      (libsource (lib "eagle-import") (part "CONN_02LOCK"))
    )
    (comp (ref "J1104")
      (value "ICSP_HEADER")
      (footprint "eagle-import:2X3")
      (libsource (lib "eagle-import") (part "AVR_SPI_PROG_3X2PTH"))
    )
    (comp (ref "R1101")
      (value "10K")
      (footprint "eagle-import:0603")
      (libsource (lib "eagle-import") (part "RESISTOR0603"))
    )
    (comp (ref "R1102")
      (value "10K")
      (footprint "eagle-import:0603")
      (libsource (lib "eagle-import") (part "RESISTOR0603"))
    )
    (comp (ref "R1103")
      (value "10K")
      (footprint "eagle-import:0603")
      (libsource (lib "eagle-import") (part "330OHM-0603-1/10W-1%"))
    )
    (comp (ref "R1104")
      (value "560r")
      (footprint "eagle-import:0603")
      (libsource (lib "eagle-import") (part "330OHM-0603-1/10W-1%"))
    )
    (comp (ref "R1105")
      (value "560r")
      (footprint "eagle-import:0603")
      (libsource (lib "eagle-import") (part "330OHM-0603-1/10W-1%"))
    )
    (comp (ref "R1106")
      (value "560r")
      (footprint "eagle-import:0603")
      (libsource (lib "eagle-import") (part "330OHM-0603-1/10W-1%"))
    )
    (comp (ref "S1101")
      (value "RST")
      (footprint "eagle-import:TACTILE_SWITCH_SMD_5.2MM")
      (libsource (lib "eagle-import") (part "MOMENTARY-SWITCH-SPST-SMD-5.2-REDUNDANT"))
    )
    (comp (ref "S1102")
      (value "SWITCH-SPDT-SMD-AYZ0202")
      (footprint "eagle-import:SWITCH_DPDT_SMD_AYZ0202")
      (libsource (lib "eagle-import") (part "SWITCH-SPDT-SMD-AYZ0202"))
    )
    (comp (ref "TP1101")
      (value "PTR1TP20R")
      (footprint "eagle-import:TP20R")
      (libsource (lib "eagle-import") (part "PTR1TP20R"))
    )
    (comp (ref "TP1102")
      (value "PTR1TP20R")
      (footprint "eagle-import:TP20R")
      (libsource (lib "eagle-import") (part "PTR1TP20R"))
    )
    (comp (ref "U1101")
      (value "DRV8835")
      (footprint "eagle-import:WSON-12")
      (libsource (lib "eagle-import") (part "DRV883X"))
    )
    (comp (ref "U1102")
      (value "ATTINY25-20SSUR")
      (footprint "eagle-import:SOIC8")
      (libsource (lib "eagle-import") (part "ATTINY45-SMT-NARROW"))
    )
    (comp (ref "C701")
      (value "0.1uF")
      (footprint "eagle-import:0603")
      (libsource (lib "eagle-import") (part "0.1UF-0603-25V-5%"))
    )
    (comp (ref "C702")
      (value "0.1uF")
      (footprint "eagle-import:0603")
      (libsource (lib "eagle-import") (part "0.1UF-0603-25V-5%"))
    )
    (comp (ref "C703")
      (value "2.2uF")
      (footprint "eagle-import:EIA3216")
      (libsource (lib "eagle-import") (part "10UF-POLAR-EIA3216-16V-10%(TANT)"))
    )
    (comp (ref "D701")
      (value "GREEN")
      (footprint "eagle-import:LED-0603")
      (libsource (lib "eagle-import") (part "LED-GREEN0603"))
    )
    (comp (ref "D702")
      (value "YELLOW")
      (footprint "eagle-import:LED-0603")
      (libsource (lib "eagle-import") (part "LED-YELLOW0603"))
    )
    (comp (ref "D703")
      (value "RED")
      (footprint "eagle-import:LED-0603")
      (libsource (lib "eagle-import") (part "LED-RED0603"))
    )
    (comp (ref "J701")
      (value "CONN_03")
      (footprint "eagle-import:1X03")
      (libsource (lib "eagle-import") (part "CONN_03"))
    )
    (comp (ref "J702")
      (value "CONN_02LOCK")
      (footprint "eagle-import:1X02_LOCK")
      (libsource (lib "eagle-import") (part "CONN_02LOCK"))
    )
    (comp (ref "J703")
      (value "ICSP_HEADER")
      (footprint "eagle-import:2X3")
      (libsource (lib "eagle-import") (part "AVR_SPI_PROG_3X2PTH"))
    )
    (comp (ref "J704")
      (value "ICSP_HEADER")
      (footprint "eagle-import:2X3")
      (libsource (lib "eagle-import") (part "AVR_SPI_PROG_3X2PTH"))
    )
    (comp (ref "R701")
      (value "330r")
      (footprint "eagle-import:0603")
      (libsource (lib "eagle-import") (part "RESISTOR0603"))
    )
    (comp (ref "R702")
      (value "33k")
      (footprint "eagle-import:0603")
      (libsource (lib "eagle-import") (part "RESISTOR0603"))
    )
    (comp (ref "R703")
      (value "10K")
      (footprint "eagle-import:0603")
      (libsource (lib "eagle-import") (part "330OHM-0603-1/10W-1%"))
    )
    (comp (ref "R704")
      (value "10K")
      (footprint "eagle-import:0603")
      (libsource (lib "eagle-import") (part "330OHM-0603-1/10W-1%"))
    )
    (comp (ref "R705")
      (value "560r")
      (footprint "eagle-import:0603")
      (libsource (lib "eagle-import") (part "330OHM-0603-1/10W-1%"))
    )
    (comp (ref "R706")
      (value "560r")
      (footprint "eagle-import:0603")
      (libsource (lib "eagle-import") (part "330OHM-0603-1/10W-1%"))
    )
    (comp (ref "R707")
      (value "560r")
      (footprint "eagle-import:0603")
      (libsource (lib "eagle-import") (part "330OHM-0603-1/10W-1%"))
    )
    (comp (ref "S701")
      (value "RST")
      (footprint "eagle-import:TACTILE_SWITCH_SMD_5.2MM")
      (libsource (lib "eagle-import") (part "MOMENTARY-SWITCH-SPST-SMD-5.2-REDUNDANT"))
    )
    (comp (ref "S702")
      (value "RST")
      (footprint "eagle-import:TACTILE_SWITCH_SMD_5.2MM")
      (libsource (lib "eagle-import") (part "MOMENTARY-SWITCH-SPST-SMD-5.2-REDUNDANT"))
    )
    (comp (ref "S703")
      (value "SWITCH-SPDT-SMD-AYZ0202")
      (footprint "eagle-import:SWITCH_DPDT_SMD_AYZ0202")
      (libsource (lib "eagle-import") (part "SWITCH-SPDT-SMD-AYZ0202"))
    )
    (comp (ref "TP701")
      (value "PTR1TP20R")
      (footprint "eagle-import:TP20R")
      (libsource (lib "eagle-import") (part "PTR1TP20R"))
    )
    (comp (ref "TP702")
      (value "PTR1TP20R")
      (footprint "eagle-import:TP20R")
      (libsource (lib "eagle-import") (part "PTR1TP20R"))
    )
    (comp (ref "TP703")
      (value "PTR1TP20R")
      (footprint "eagle-import:TP20R")
      (libsource (lib "eagle-import") (part "PTR1TP20R"))
    )
    (comp (ref "U701")
      (value "ATTINY25-20SSUR")
      (footprint "eagle-import:SOIC8")
      (libsource (lib "eagle-import") (part "ATTINY45-SMT-NARROW"))
    )
    (comp (ref "U702")
      (value "ATTINY25-20SSUR")
      (footprint "eagle-import:SOIC8")
      (libsource (lib "eagle-import") (part "ATTINY45-SMT-NARROW"))
    )
    (comp (ref "U703")
      (value "MIC5205")
      (footprint "eagle-import:SOT23-5")
      (libsource (lib "eagle-import") (part "V_REG_MIC52055V"))
    )
    (comp (ref "C1301")
      (value "0.1uF")
      (footprint "eagle-import:0603")
      (libsource (lib "eagle-import") (part "0.1UF-0603-25V-5%"))
    )
    (comp (ref "C1302")
      (value "0.33uF")
      (footprint "eagle-import:0603")
      (libsource (lib "eagle-import") (part "0.1UF-0603-25V-(+80/-20%)"))
    )
    (comp (ref "C1303")
      (value "0.1uF")
      (footprint "eagle-import:0603")
      (libsource (lib "eagle-import") (part "0.1UF-0603-25V-(+80/-20%)"))
    )
    (comp (ref "D1301")
      (value "GREEN")
      (footprint "eagle-import:LED-0603")
      (libsource (lib "eagle-import") (part "LED-GREEN0603"))
    )
    (comp (ref "D1302")
      (value "YELLOW")
      (footprint "eagle-import:LED-0603")
      (libsource (lib "eagle-import") (part "LED-YELLOW0603"))
    )
    (comp (ref "D1303")
      (value "RED")
      (footprint "eagle-import:LED-0603")
      (libsource (lib "eagle-import") (part "LED-RED0603"))
    )
    (comp (ref "IC1301")
      (value "7805DT")
      (footprint "eagle-import:TO252")
      (libsource (lib "eagle-import") (part "78DT05"))
    )
    (comp (ref "J1301")
      (value "CONN_02LOCK")
      (footprint "eagle-import:1X02_LOCK")
      (libsource (lib "eagle-import") (part "CONN_02LOCK"))
    )
    (comp (ref "J1302")
      (value "CONN_02LOCK")
      (footprint "eagle-import:1X02_LOCK")
      (libsource (lib "eagle-import") (part "CONN_02LOCK"))
    )
    (comp (ref "J1303")
      (value "CONN_02LOCK")
      (footprint "eagle-import:1X02_LOCK")
      (libsource (lib "eagle-import") (part "CONN_02LOCK"))
    )
    (comp (ref "J1304")
      (value "ICSP_HEADER")
      (footprint "eagle-import:2X3")
      (libsource (lib "eagle-import") (part "AVR_SPI_PROG_3X2PTH"))
    )
    (comp (ref "R1301")
      (value "10K")
      (footprint "eagle-import:0603")
      (libsource (lib "eagle-import") (part "RESISTOR0603"))
    )
    (comp (ref "R1302")
      (value "10K")
      (footprint "eagle-import:0603")
      (libsource (lib "eagle-import") (part "RESISTOR0603"))
    )
    (comp (ref "R1303")
      (value "10K")
      (footprint "eagle-import:0603")
      (libsource (lib "eagle-import") (part "330OHM-0603-1/10W-1%"))
    )
    (comp (ref "R1304")
      (value "560r")
      (footprint "eagle-import:0603")
      (libsource (lib "eagle-import") (part "330OHM-0603-1/10W-1%"))
    )
    (comp (ref "R1305")
      (value "560r")
      (footprint "eagle-import:0603")
      (libsource (lib "eagle-import") (part "330OHM-0603-1/10W-1%"))
    )
    (comp (ref "R1306")
      (value "560r")
      (footprint "eagle-import:0603")
      (libsource (lib "eagle-import") (part "330OHM-0603-1/10W-1%"))
    )
    (comp (ref "S1301")
      (value "RST")
      (footprint "eagle-import:TACTILE_SWITCH_SMD_5.2MM")
      (libsource (lib "eagle-import") (part "MOMENTARY-SWITCH-SPST-SMD-5.2-REDUNDANT"))
    )
    (comp (ref "S1302")
      (value "SWITCH-SPDT-SMD-AYZ0202")
      (footprint "eagle-import:SWITCH_DPDT_SMD_AYZ0202")
      (libsource (lib "eagle-import") (part "SWITCH-SPDT-SMD-AYZ0202"))
    )
    (comp (ref "TP1301")
      (value "PTR1TP20R")
      (footprint "eagle-import:TP20R")
      (libsource (lib "eagle-import") (part "PTR1TP20R"))
    )
    (comp (ref "TP1302")
      (value "PTR1TP20R")
      (footprint "eagle-import:TP20R")
      (libsource (lib "eagle-import") (part "PTR1TP20R"))
    )
    (comp (ref "U1301")
      (value "DRV8835")
      (footprint "eagle-import:WSON-12")
      (libsource (lib "eagle-import") (part "DRV883X"))
    )
    (comp (ref "U1302")
      (value "ATTINY25-20SSUR")
      (footprint "eagle-import:SOIC8")
      (libsource (lib "eagle-import") (part "ATTINY45-SMT-NARROW"))
    )
    (comp (ref "C201")
      (value "0.1uF")
      (footprint "eagle-import:0603")
      (libsource (lib "eagle-import") (part "0.1UF-0603-25V-5%"))
    )
    (comp (ref "C202")
      (value "2.2uF")
      (footprint "eagle-import:EIA3216")
      (libsource (lib "eagle-import") (part "10UF-POLAR-EIA3216-16V-10%(TANT)"))
    )
    (comp (ref "D201")
      (value "SK310A-TP")
      (footprint "eagle-import:SMADIODE")
      (libsource (lib "eagle-import") (part "DIODESMA"))
    )
    (comp (ref "D202")
      (value "GREEN")
      (footprint "eagle-import:LED-0603")
      (libsource (lib "eagle-import") (part "LED-GREEN0603"))
    )
    (comp (ref "D203")
      (value "YELLOW")
      (footprint "eagle-import:LED-0603")
      (libsource (lib "eagle-import") (part "LED-YELLOW0603"))
    )
    (comp (ref "D204")
      (value "RED")
      (footprint "eagle-import:LED-0603")
      (libsource (lib "eagle-import") (part "LED-RED0603"))
    )
    (comp (ref "J201")
      (value "CONN_03LOCK")
      (footprint "eagle-import:1X03_LOCK")
      (libsource (lib "eagle-import") (part "CONN_03LOCK"))
    )
    (comp (ref "J202")
      (value "CONN_02LOCK")
      (footprint "eagle-import:1X02_LOCK")
      (libsource (lib "eagle-import") (part "CONN_02LOCK"))
    )
    (comp (ref "J203")
      (value "CONN_023.5MM_LOCK")
      (footprint "eagle-import:SCREWTERMINAL-3.5MM-2_LOCK")
      (libsource (lib "eagle-import") (part "CONN_023.5MM_LOCK"))
    )
    (comp (ref "J204")
      (value "ICSP_HEADER")
      (footprint "eagle-import:2X3")
      (libsource (lib "eagle-import") (part "AVR_SPI_PROG_3X2PTH"))
    )
    (comp (ref "JP201")
      (value "JUMPER-SMT_2_NO_SILK")
      (footprint "eagle-import:SMT-JUMPER_2_NO_SILK")
      (libsource (lib "eagle-import") (part "JUMPER-SMT_2_NO_SILK"))
    )
    (comp (ref "JP202")
      (value "JUMPER-SMT_2_NC_TRACE_SILK")
      (footprint "eagle-import:SMT-JUMPER_2_NC_TRACE_SILK")
      (libsource (lib "eagle-import") (part "JUMPER-SMT_2_NC_TRACE_SILK"))
    )
    (comp (ref "Q201")
      (value "PSMN7R0-60YS")
      (footprint "eagle-import:SOT669")
      (libsource (lib "eagle-import") (part "PSMN7R0-60YS"))
    )
    (comp (ref "R201")
      (value "10R")
      (footprint "eagle-import:0603")
      (libsource (lib "eagle-import") (part "RESISTOR0603"))
    )
    (comp (ref "R202")
      (value "100K")
      (footprint "eagle-import:0603")
      (libsource (lib "eagle-import") (part "RESISTOR0603"))
    )
    (comp (ref "R203")
      (value "10k")
      (footprint "eagle-import:0603")
      (libsource (lib "eagle-import") (part "RESISTOR0603"))
    )
    (comp (ref "R204")
      (value "10K")
      (footprint "eagle-import:0603")
      (libsource (lib "eagle-import") (part "330OHM-0603-1/10W-1%"))
    )
    (comp (ref "R205")
      (value "560r")
      (footprint "eagle-import:0603")
      (libsource (lib "eagle-import") (part "330OHM-0603-1/10W-1%"))
    )
    (comp (ref "R206")
      (value "560r")
      (footprint "eagle-import:0603")
      (libsource (lib "eagle-import") (part "330OHM-0603-1/10W-1%"))
    )
    (comp (ref "R207")
      (value "560r")
      (footprint "eagle-import:0603")
      (libsource (lib "eagle-import") (part "330OHM-0603-1/10W-1%"))
    )
    (comp (ref "S201")
      (value "RST")
      (footprint "eagle-import:TACTILE_SWITCH_SMD_5.2MM")
      (libsource (lib "eagle-import") (part "MOMENTARY-SWITCH-SPST-SMD-5.2-REDUNDANT"))
    )
    (comp (ref "S202")
      (value "SWITCH-SPDT-SMD-AYZ0202")
      (footprint "eagle-import:SWITCH_DPDT_SMD_AYZ0202")
      (libsource (lib "eagle-import") (part "SWITCH-SPDT-SMD-AYZ0202"))
    )
    (comp (ref "TP201")
      (value "PTR1TP20R")
      (footprint "eagle-import:TP20R")
      (libsource (lib "eagle-import") (part "PTR1TP20R"))
    )
    (comp (ref "TP202")
      (value "PTR1TP20R")
      (footprint "eagle-import:TP20R")
      (libsource (lib "eagle-import") (part "PTR1TP20R"))
    )
    (comp (ref "TP203")
      (value "PTR1TP20R")
      (footprint "eagle-import:TP20R")
      (libsource (lib "eagle-import") (part "PTR1TP20R"))
    )
    (comp (ref "U201")
      (value "74HC1G04")
      (footprint "eagle-import:SOT353")
      (libsource (lib "eagle-import") (part "741G04HC"))
    )
    (comp (ref "U202")
      (value "ATTINY25-20SSUR")
      (footprint "eagle-import:SOIC8")
      (libsource (lib "eagle-import") (part "ATTINY45-SMT-NARROW"))
    )
    (comp (ref "U203")
      (value "MIC5205")
      (footprint "eagle-import:SOT23-5")
      (libsource (lib "eagle-import") (part "V_REG_MIC52055V"))
    )
    (comp (ref "C901")
      (value "0.1uF")
      (footprint "eagle-import:0603")
      (libsource (lib "eagle-import") (part "0.1UF-0603-25V-5%"))
    )
    (comp (ref "C902")
      (value "2.2uF")
      (footprint "eagle-import:EIA3216")
      (libsource (lib "eagle-import") (part "10UF-POLAR-EIA3216-16V-10%(TANT)"))
    )
    (comp (ref "D901")
      (value "SK310A-TP")
      (footprint "eagle-import:SMADIODE")
      (libsource (lib "eagle-import") (part "DIODESMA"))
    )
    (comp (ref "D902")
      (value "GREEN")
      (footprint "eagle-import:LED-0603")
      (libsource (lib "eagle-import") (part "LED-GREEN0603"))
    )
    (comp (ref "D903")
      (value "YELLOW")
      (footprint "eagle-import:LED-0603")
      (libsource (lib "eagle-import") (part "LED-YELLOW0603"))
    )
    (comp (ref "D904")
      (value "RED")
      (footprint "eagle-import:LED-0603")
      (libsource (lib "eagle-import") (part "LED-RED0603"))
    )
    (comp (ref "J901")
      (value "CONN_02LOCK")
      (footprint "eagle-import:1X02_LOCK")
      (libsource (lib "eagle-import") (part "CONN_02LOCK"))
    )
    (comp (ref "J902")
      (value "CONN_023.5MM_LOCK")
      (footprint "eagle-import:SCREWTERMINAL-3.5MM-2_LOCK")
      (libsource (lib "eagle-import") (part "CONN_023.5MM_LOCK"))
    )
    (comp (ref "J903")
      (value "ICSP_HEADER")
      (footprint "eagle-import:2X3")
      (libsource (lib "eagle-import") (part "AVR_SPI_PROG_3X2PTH"))
    )
    (comp (ref "Q901")
      (value "PSMN7R0-60YS")
      (footprint "eagle-import:SOT669")
      (libsource (lib "eagle-import") (part "PSMN7R0-60YS"))
    )
    (comp (ref "R901")
      (value "10R")
      (footprint "eagle-import:0603")
      (libsource (lib "eagle-import") (part "RESISTOR0603"))
    )
    (comp (ref "R902")
      (value "100K")
      (footprint "eagle-import:0603")
      (libsource (lib "eagle-import") (part "RESISTOR0603"))
    )
    (comp (ref "R903")
      (value "10K")
      (footprint "eagle-import:0603")
      (libsource (lib "eagle-import") (part "RESISTOR0603"))
    )
    (comp (ref "R904")
      (value "10K")
      (footprint "eagle-import:0603")
      (libsource (lib "eagle-import") (part "330OHM-0603-1/10W-1%"))
    )
    (comp (ref "R905")
      (value "560r")
      (footprint "eagle-import:0603")
      (libsource (lib "eagle-import") (part "330OHM-0603-1/10W-1%"))
    )
    (comp (ref "R906")
      (value "560r")
      (footprint "eagle-import:0603")
      (libsource (lib "eagle-import") (part "330OHM-0603-1/10W-1%"))
    )
    (comp (ref "R907")
      (value "560r")
      (footprint "eagle-import:0603")
      (libsource (lib "eagle-import") (part "330OHM-0603-1/10W-1%"))
    )
    (comp (ref "S901")
      (value "RST")
      (footprint "eagle-import:TACTILE_SWITCH_SMD_5.2MM")
      (libsource (lib "eagle-import") (part "MOMENTARY-SWITCH-SPST-SMD-5.2-REDUNDANT"))
    )
    (comp (ref "S902")
      (value "SWITCH-SPDT-SMD-AYZ0202")
      (footprint "eagle-import:SWITCH_DPDT_SMD_AYZ0202")
      (libsource (lib "eagle-import") (part "SWITCH-SPDT-SMD-AYZ0202"))
    )
    (comp (ref "TP901")
      (value "PTR1TP20R")
      (footprint "eagle-import:TP20R")
      (libsource (lib "eagle-import") (part "PTR1TP20R"))
    )
    (comp (ref "TP902")
      (value "PTR1TP20R")
      (footprint "eagle-import:TP20R")
      (libsource (lib "eagle-import") (part "PTR1TP20R"))
    )
    (comp (ref "U901")
      (value "ATTINY25-20SSUR")
      (footprint "eagle-import:SOIC8")
      (libsource (lib "eagle-import") (part "ATTINY45-SMT-NARROW"))
    )
    (comp (ref "U902")
      (value "MIC5205")
      (footprint "eagle-import:SOT23-5")
      (libsource (lib "eagle-import") (part "V_REG_MIC52055V"))
    )
    (comp (ref "C101")
      (value "2.2uF")
      (footprint "eagle-import:EIA3216")
      (libsource (lib "eagle-import") (part "10UF-POLAR-EIA3216-16V-10%(TANT)"))
    )
    (comp (ref "D101")
      (value "GREEN")
      (footprint "eagle-import:LED-0603")
      (libsource (lib "eagle-import") (part "LED-GREEN0603"))
    )
    (comp (ref "D102")
      (value "RED")
      (footprint "eagle-import:LED-0603")
      (libsource (lib "eagle-import") (part "LED-RED0603"))
    )
    (comp (ref "JP101")
      (value "JUMPER_NC_TRACE")
      (footprint "eagle-import:SMT-JUMPER_2_NC_TRACE_SILK")
      (libsource (lib "eagle-import") (part "JUMPER-SMT_2_NC_TRACE_SILK"))
    )
    (comp (ref "JP102")
      (value "JUMPER-SMT_2_NO_SILK")
      (footprint "eagle-import:SMT-JUMPER_2_NO_SILK")
      (libsource (lib "eagle-import") (part "JUMPER-SMT_2_NO_SILK"))
    )
    (comp (ref "R101")
      (value "10K")
      (footprint "eagle-import:0603")
      (libsource (lib "eagle-import") (part "330OHM-0603-1/10W-1%"))
    )
    (comp (ref "R102")
      (value "560r")
      (footprint "eagle-import:0603")
      (libsource (lib "eagle-import") (part "330OHM-0603-1/10W-1%"))
    )
    (comp (ref "R103")
      (value "560r")
      (footprint "eagle-import:0603")
      (libsource (lib "eagle-import") (part "330OHM-0603-1/10W-1%"))
    )
    (comp (ref "S101")
      (value "REED_SWITCH")
      (footprint "eagle-import:AXIAL_GULLWING_REED")
      (libsource (lib "eagle-import") (part "MDSM-10_REED_SWITCH"))
    )
    (comp (ref "S102")
      (value "SWITCH-SPDT-SMD-AYZ0202")
      (footprint "eagle-import:SWITCH_DPDT_SMD_AYZ0202")
      (libsource (lib "eagle-import") (part "SWITCH-SPDT-SMD-AYZ0202"))
    )
    (comp (ref "TP101")
      (value "PTR1TP20R")
      (footprint "eagle-import:TP20R")
      (libsource (lib "eagle-import") (part "PTR1TP20R"))
    )
    (comp (ref "U101")
      (value "74HC1G04")
      (footprint "eagle-import:SOT353")
      (libsource (lib "eagle-import") (part "741G04HC"))
    )
    (comp (ref "U102")
      (value "MIC5205")
      (footprint "eagle-import:SOT23-5")
      (libsource (lib "eagle-import") (part "V_REG_MIC52055V"))
    )
    (comp (ref "C1201")
      (value "0.1uF")
      (footprint "eagle-import:0603")
      (libsource (lib "eagle-import") (part "0.1UF-0603-25V-5%"))
    )
    (comp (ref "C1202")
      (value "0.33uF")
      (footprint "eagle-import:0603")
      (libsource (lib "eagle-import") (part "0.1UF-0603-25V-(+80/-20%)"))
    )
    (comp (ref "C1203")
      (value "0.1uF")
      (footprint "eagle-import:0603")
      (libsource (lib "eagle-import") (part "0.1UF-0603-25V-(+80/-20%)"))
    )
    (comp (ref "D1201")
      (value "GREEN")
      (footprint "eagle-import:LED-0603")
      (libsource (lib "eagle-import") (part "LED-GREEN0603"))
    )
    (comp (ref "D1202")
      (value "YELLOW")
      (footprint "eagle-import:LED-0603")
      (libsource (lib "eagle-import") (part "LED-YELLOW0603"))
    )
    (comp (ref "D1203")
      (value "RED")
      (footprint "eagle-import:LED-0603")
      (libsource (lib "eagle-import") (part "LED-RED0603"))
    )
    (comp (ref "IC1201")
      (value "7805DT")
      (footprint "eagle-import:TO252")
      (libsource (lib "eagle-import") (part "78DT05"))
    )
    (comp (ref "J1201")
      (value "CONN_02LOCK")
      (footprint "eagle-import:1X02_LOCK")
      (libsource (lib "eagle-import") (part "CONN_02LOCK"))
    )
    (comp (ref "J1202")
      (value "CONN_02LOCK")
      (footprint "eagle-import:1X02_LOCK")
      (libsource (lib "eagle-import") (part "CONN_02LOCK"))
    )
    (comp (ref "J1203")
      (value "CONN_02LOCK")
      (footprint "eagle-import:1X02_LOCK")
      (libsource (lib "eagle-import") (part "CONN_02LOCK"))
    )
    (comp (ref "J1204")
      (value "ICSP_HEADER")
      (footprint "eagle-import:2X3")
      (libsource (lib "eagle-import") (part "AVR_SPI_PROG_3X2PTH"))
    )
    (comp (ref "R1201")
      (value "10K")
      (footprint "eagle-import:0603")
      (libsource (lib "eagle-import") (part "RESISTOR0603"))
    )
    (comp (ref "R1202")
      (value "10K")
      (footprint "eagle-import:0603")
      (libsource (lib "eagle-import") (part "RESISTOR0603"))
    )
    (comp (ref "R1203")
      (value "10K")
      (footprint "eagle-import:0603")
      (libsource (lib "eagle-import") (part "330OHM-0603-1/10W-1%"))
    )
    (comp (ref "R1204")
      (value "560r")
      (footprint "eagle-import:0603")
      (libsource (lib "eagle-import") (part "330OHM-0603-1/10W-1%"))
    )
    (comp (ref "R1205")
      (value "560r")
      (footprint "eagle-import:0603")
      (libsource (lib "eagle-import") (part "330OHM-0603-1/10W-1%"))
    )
    (comp (ref "R1206")
      (value "560r")
      (footprint "eagle-import:0603")
      (libsource (lib "eagle-import") (part "330OHM-0603-1/10W-1%"))
    )
    (comp (ref "S1201")
      (value "RST")
      (footprint "eagle-import:TACTILE_SWITCH_SMD_5.2MM")
      (libsource (lib "eagle-import") (part "MOMENTARY-SWITCH-SPST-SMD-5.2-REDUNDANT"))
    )
    (comp (ref "S1202")
      (value "SWITCH-SPDT-SMD-AYZ0202")
      (footprint "eagle-import:SWITCH_DPDT_SMD_AYZ0202")
      (libsource (lib "eagle-import") (part "SWITCH-SPDT-SMD-AYZ0202"))
    )
    (comp (ref "TP1201")
      (value "PTR1TP20R")
      (footprint "eagle-import:TP20R")
      (libsource (lib "eagle-import") (part "PTR1TP20R"))
    )
    (comp (ref "TP1202")
      (value "PTR1TP20R")
      (footprint "eagle-import:TP20R")
      (libsource (lib "eagle-import") (part "PTR1TP20R"))
    )
    (comp (ref "U1201")
      (value "DRV8835")
      (footprint "eagle-import:WSON-12")
      (libsource (lib "eagle-import") (part "DRV883X"))
    )
    (comp (ref "U1202")
      (value "ATTINY25-20SSUR")
      (footprint "eagle-import:SOIC8")
      (libsource (lib "eagle-import") (part "ATTINY45-SMT-NARROW"))
    )
  )
  (nets
    (net (code "1") (name "BALLOON_IN") (class "Default")
      (node (ref "D1202") (pin "A") (pinfunction "A_A") (pintype "passive"))
      (node (ref "J1611") (pin "1") (pinfunction "1_1") (pintype "passive"))
      (node (ref "U1202") (pin "2") (pinfunction "PB3(ADC3)_2") (pintype "bidirectional"))
    )
    (net (code "2") (name "BALLOON_MISO") (class "Default")
      (node (ref "J1204") (pin "1") (pinfunction "1_1") (pintype "passive"))
      (node (ref "U1201") (pin "9") (pinfunction "AIN2/EN_9") (pintype "bidirectional"))
      (node (ref "U1202") (pin "6") (pinfunction "PB1(MISO)_6") (pintype "bidirectional"))
    )
    (net (code "3") (name "BALLOON_MOSI") (class "Default")
      (node (ref "J1204") (pin "4") (pinfunction "4_4") (pintype "passive"))
      (node (ref "U1201") (pin "10") (pinfunction "AIN1/PH_10") (pintype "bidirectional"))
      (node (ref "U1202") (pin "5") (pinfunction "PB0(MOSI)_5") (pintype "bidirectional"))
    )
    (net (code "4") (name "BALLOON_OUT") (class "Default")
      (node (ref "D1201") (pin "A") (pinfunction "A_A") (pintype "passive"))
      (node (ref "J1201") (pin "2") (pinfunction "2_2") (pintype "passive"))
      (node (ref "J1612") (pin "2") (pinfunction "2_2") (pintype "passive"))
      (node (ref "R1201") (pin "1") (pinfunction "1_1") (pintype "passive"))
      (node (ref "S1202") (pin "2") (pinfunction "P_2") (pintype "passive"))
    )
    (net (code "5") (name "BALLOON_RST") (class "Default")
      (node (ref "J1204") (pin "5") (pinfunction "5_5") (pintype "passive"))
      (node (ref "R1203") (pin "1") (pinfunction "1_1") (pintype "passive"))
      (node (ref "S1201") (pin "3") (pinfunction "2_3") (pintype "passive"))
      (node (ref "S1201") (pin "4") (pinfunction "2_4") (pintype "passive"))
      (node (ref "U1202") (pin "1") (pinfunction "PB5(NRES)_1") (pintype "bidirectional"))
    )
    (net (code "6") (name "BALLOON_SCK") (class "Default")
      (node (ref "J1202") (pin "2") (pinfunction "2_2") (pintype "passive"))
      (node (ref "J1204") (pin "3") (pinfunction "3_3") (pintype "passive"))
      (node (ref "R1202") (pin "1") (pinfunction "1_1") (pintype "passive"))
      (node (ref "U1202") (pin "7") (pinfunction "PB2(SCK/ADC1)_7") (pintype "bidirectional"))
    )
    (net (code "7") (name "BALLOON_VCC") (class "Default")
      (node (ref "C1201") (pin "2") (pinfunction "2_2") (pintype "passive"))
      (node (ref "C1203") (pin "1") (pinfunction "1_1") (pintype "passive"))
      (node (ref "D1203") (pin "A") (pinfunction "A_A") (pintype "passive"))
      (node (ref "IC1201") (pin "2") (pinfunction "VO_2") (pintype "passive"))
      (node (ref "J1201") (pin "1") (pinfunction "1_1") (pintype "passive"))
      (node (ref "J1202") (pin "1") (pinfunction "1_1") (pintype "passive"))
      (node (ref "J1204") (pin "2") (pinfunction "2_2") (pintype "passive"))
      (node (ref "R1203") (pin "2") (pinfunction "2_2") (pintype "passive"))
      (node (ref "S1202") (pin "1") (pinfunction "O_1") (pintype "passive"))
      (node (ref "TP1201") (pin "TP") (pinfunction "TP_TP") (pintype "input"))
      (node (ref "U1201") (pin "1") (pinfunction "VM_1") (pintype "bidirectional"))
      (node (ref "U1201") (pin "11") (pinfunction "MODE_11") (pintype "bidirectional"))
      (node (ref "U1201") (pin "12") (pinfunction "VCC_12") (pintype "bidirectional"))
      (node (ref "U1202") (pin "8") (pinfunction "VCC_8") (pintype "bidirectional"))
    )
    (net (code "8") (name "COIN_IN") (class "Default")
      (node (ref "D203") (pin "A") (pinfunction "A_A") (pintype "passive"))
      (node (ref "J1601") (pin "1") (pinfunction "1_1") (pintype "passive"))
      (node (ref "JP201") (pin "1") (pinfunction "1_1") (pintype "passive"))
      (node (ref "U201") (pin "2") (pinfunction "A_2") (pintype "bidirectional"))
    )
    (net (code "9") (name "COIN_MISO") (class "Default")
      (node (ref "J204") (pin "1") (pinfunction "1_1") (pintype "passive"))
      (node (ref "U202") (pin "6") (pinfunction "PB1(MISO)_6") (pintype "bidirectional"))
    )
    (net (code "10") (name "COIN_MOSI") (class "Default")
      (node (ref "J204") (pin "4") (pinfunction "4_4") (pintype "passive"))
      (node (ref "U202") (pin "5") (pinfunction "PB0(MOSI)_5") (pintype "bidirectional"))
    )
    (net (code "11") (name "COIN_OUT") (class "Default")
      (node (ref "D202") (pin "A") (pinfunction "A_A") (pintype "passive"))
      (node (ref "J1602") (pin "2") (pinfunction "2_2") (pintype "passive"))
      (node (ref "S202") (pin "2") (pinfunction "P_2") (pintype "passive"))
    )
    (net (code "12") (name "COIN_OUT_SWITCH") (class "Default")
      (node (ref "S202") (pin "3") (pinfunction "S_3") (pintype "passive"))
      (node (ref "U202") (pin "3") (pinfunction "PB4(ADC2)_3") (pintype "bidirectional"))
    )
    (net (code "13") (name "COIN_RST") (class "Default")
      (node (ref "J204") (pin "5") (pinfunction "5_5") (pintype "passive"))
      (node (ref "R204") (pin "1") (pinfunction "1_1") (pintype "passive"))
      (node (ref "S201") (pin "3") (pinfunction "2_3") (pintype "passive"))
      (node (ref "S201") (pin "4") (pinfunction "2_4") (pintype "passive"))
      (node (ref "U202") (pin "1") (pinfunction "PB5(NRES)_1") (pintype "bidirectional"))
    )
    (net (code "14") (name "COIN_SCK") (class "Default")
      (node (ref "J201") (pin "1") (pinfunction "1_1") (pintype "passive"))
      (node (ref "J204") (pin "3") (pinfunction "3_3") (pintype "passive"))
      (node (ref "R203") (pin "1") (pinfunction "1_1") (pintype "passive"))
      (node (ref "U202") (pin "7") (pinfunction "PB2(SCK/ADC1)_7") (pintype "bidirectional"))
    )
    (net (code "15") (name "COIN_VCC") (class "Default")
      (node (ref "C201") (pin "2") (pinfunction "2_2") (pintype "passive"))
      (node (ref "C202") (pin "+") (pinfunction "+_+") (pintype "passive"))
      (node (ref "D204") (pin "A") (pinfunction "A_A") (pintype "passive"))
      (node (ref "J204") (pin "2") (pinfunction "2_2") (pintype "passive"))
      (node (ref "R203") (pin "2") (pinfunction "2_2") (pintype "passive"))
      (node (ref "R204") (pin "2") (pinfunction "2_2") (pintype "passive"))
      (node (ref "S202") (pin "1") (pinfunction "O_1") (pintype "passive"))
      (node (ref "TP202") (pin "TP") (pinfunction "TP_TP") (pintype "input"))
      (node (ref "U201") (pin "5") (pinfunction "P$V+_5") (pintype "bidirectional"))
      (node (ref "U202") (pin "8") (pinfunction "VCC_8") (pintype "bidirectional"))
      (node (ref "U203") (pin "5") (pinfunction "OUT_5") (pintype "passive"))
    )
    (net (code "16") (name "EMAG_IN") (class "Default")
      (node (ref "D803") (pin "A") (pinfunction "A_A") (pintype "passive"))
      (node (ref "J1607") (pin "1") (pinfunction "1_1") (pintype "passive"))
      (node (ref "U802") (pin "1") (pinfunction "A_1") (pintype "input"))
    )
    (net (code "17") (name "EMAG_OUT") (class "Default")
      (node (ref "D802") (pin "A") (pinfunction "A_A") (pintype "passive"))
      (node (ref "J1608") (pin "2") (pinfunction "2_2") (pintype "passive"))
      (node (ref "J801") (pin "1") (pinfunction "1_1") (pintype "passive"))
      (node (ref "R801") (pin "2") (pinfunction "2_2") (pintype "passive"))
      (node (ref "S801") (pin "2") (pinfunction "P_2") (pintype "passive"))
      (node (ref "U801") (pin "2") (pinfunction "A_2") (pintype "bidirectional"))
    )
    (net (code "18") (name "EMAG_VCC") (class "Default")
      (node (ref "C801") (pin "+") (pinfunction "+_+") (pintype "passive"))
      (node (ref "D804") (pin "A") (pinfunction "A_A") (pintype "passive"))
      (node (ref "J801") (pin "2") (pinfunction "2_2") (pintype "passive"))
      (node (ref "S801") (pin "1") (pinfunction "O_1") (pintype "passive"))
      (node (ref "TP801") (pin "TP") (pinfunction "TP_TP") (pintype "input"))
      (node (ref "U801") (pin "5") (pinfunction "P$V+_5") (pintype "bidirectional"))
      (node (ref "U802") (pin "5") (pinfunction "VCC_5") (pintype "power_in"))
      (node (ref "U803") (pin "5") (pinfunction "OUT_5") (pintype "passive"))
    )
    (net (code "19") (name "ENDO_IN") (class "Default")
      (node (ref "D503") (pin "A") (pinfunction "A_A") (pintype "passive"))
      (node (ref "J1604") (pin "1") (pinfunction "1_1") (pintype "passive"))
      (node (ref "U502") (pin "1") (pinfunction "A_1") (pintype "input"))
    )
    (net (code "20") (name "ENDO_MISO") (class "Default")
      (node (ref "J503") (pin "1") (pinfunction "1_1") (pintype "passive"))
      (node (ref "U503") (pin "6") (pinfunction "PB1(MISO)_6") (pintype "bidirectional"))
    )
    (net (code "21") (name "ENDO_MOSI") (class "Default")
      (node (ref "J503") (pin "4") (pinfunction "4_4") (pintype "passive"))
      (node (ref "U503") (pin "5") (pinfunction "PB0(MOSI)_5") (pintype "bidirectional"))
    )
    (net (code "22") (name "ENDO_OUT") (class "Default")
      (node (ref "D502") (pin "A") (pinfunction "A_A") (pintype "passive"))
      (node (ref "J1605") (pin "2") (pinfunction "2_2") (pintype "passive"))
      (node (ref "S502") (pin "2") (pinfunction "P_2") (pintype "passive"))
      (node (ref "U501") (pin "2") (pinfunction "A_2") (pintype "bidirectional"))
    )
    (net (code "23") (name "ENDO_OUT_SWITCH") (class "Default")
      (node (ref "S502") (pin "3") (pinfunction "S_3") (pintype "passive"))
      (node (ref "U503") (pin "3") (pinfunction "PB4(ADC2)_3") (pintype "bidirectional"))
    )
    (net (code "24") (name "ENDO_RST") (class "Default")
      (node (ref "J503") (pin "5") (pinfunction "5_5") (pintype "passive"))
      (node (ref "R504") (pin "1") (pinfunction "1_1") (pintype "passive"))
      (node (ref "S501") (pin "3") (pinfunction "2_3") (pintype "passive"))
      (node (ref "S501") (pin "4") (pinfunction "2_4") (pintype "passive"))
      (node (ref "U503") (pin "1") (pinfunction "PB5(NRES)_1") (pintype "bidirectional"))
    )
    (net (code "25") (name "ENDO_SCK") (class "Default")
      (node (ref "J503") (pin "3") (pinfunction "3_3") (pintype "passive"))
      (node (ref "R501") (pin "2") (pinfunction "2_2") (pintype "passive"))
      (node (ref "U503") (pin "7") (pinfunction "PB2(SCK/ADC1)_7") (pintype "bidirectional"))
    )
    (net (code "26") (name "ENDO_VCC") (class "Default")
      (node (ref "C501") (pin "2") (pinfunction "2_2") (pintype "passive"))
      (node (ref "C502") (pin "+") (pinfunction "+_+") (pintype "passive"))
      (node (ref "D504") (pin "A") (pinfunction "A_A") (pintype "passive"))
      (node (ref "J503") (pin "2") (pinfunction "2_2") (pintype "passive"))
      (node (ref "R504") (pin "2") (pinfunction "2_2") (pintype "passive"))
      (node (ref "S502") (pin "1") (pinfunction "O_1") (pintype "passive"))
      (node (ref "TP503") (pin "TP") (pinfunction "TP_TP") (pintype "input"))
      (node (ref "U501") (pin "5") (pinfunction "P$V+_5") (pintype "bidirectional"))
      (node (ref "U502") (pin "5") (pinfunction "VCC_5") (pintype "power_in"))
      (node (ref "U503") (pin "8") (pinfunction "VCC_8") (pintype "bidirectional"))
      (node (ref "U504") (pin "5") (pinfunction "OUT_5") (pintype "passive"))
    )
    (net (code "27") (name "END_IN") (class "Default")
      (node (ref "D1501") (pin "A") (pinfunction "A_A") (pintype "passive"))
      (node (ref "J1501") (pin "1") (pinfunction "1_1") (pintype "passive"))
      (node (ref "J1614") (pin "1") (pinfunction "1_1") (pintype "passive"))
      (node (ref "R1501") (pin "2") (pinfunction "2_2") (pintype "passive"))
    )
    (net (code "28") (name "END_VCC") (class "Default")
      (node (ref "C1502") (pin "1") (pinfunction "1_1") (pintype "passive"))
      (node (ref "D1502") (pin "A") (pinfunction "A_A") (pintype "passive"))
      (node (ref "IC1501") (pin "2") (pinfunction "VO_2") (pintype "passive"))
      (node (ref "J1501") (pin "2") (pinfunction "2_2") (pintype "passive"))
      (node (ref "TP1501") (pin "TP") (pinfunction "TP_TP") (pintype "input"))
    )
    (net (code "29") (name "EXO_IN") (class "Default")
      (node (ref "D303") (pin "A") (pinfunction "A_A") (pintype "passive"))
      (node (ref "J1602") (pin "1") (pinfunction "1_1") (pintype "passive"))
      (node (ref "U302") (pin "1") (pinfunction "A_1") (pintype "input"))
    )
    (net (code "30") (name "EXO_MISO") (class "Default")
      (node (ref "J301") (pin "1") (pinfunction "1_1") (pintype "passive"))
      (node (ref "U303") (pin "6") (pinfunction "PB1(MISO)_6") (pintype "bidirectional"))
    )
    (net (code "31") (name "EXO_MOSI") (class "Default")
      (node (ref "J301") (pin "4") (pinfunction "4_4") (pintype "passive"))
      (node (ref "U303") (pin "5") (pinfunction "PB0(MOSI)_5") (pintype "bidirectional"))
    )
    (net (code "32") (name "EXO_OUT") (class "Default")
      (node (ref "D302") (pin "A") (pinfunction "A_A") (pintype "passive"))
      (node (ref "J1603") (pin "2") (pinfunction "2_2") (pintype "passive"))
      (node (ref "S302") (pin "2") (pinfunction "P_2") (pintype "passive"))
      (node (ref "U301") (pin "2") (pinfunction "A_2") (pintype "bidirectional"))
    )
    (net (code "33") (name "EXO_OUT_SWITCH") (class "Default")
      (node (ref "S302") (pin "3") (pinfunction "S_3") (pintype "passive"))
      (node (ref "U303") (pin "3") (pinfunction "PB4(ADC2)_3") (pintype "bidirectional"))
    )
    (net (code "34") (name "EXO_RST") (class "Default")
      (node (ref "J301") (pin "5") (pinfunction "5_5") (pintype "passive"))
      (node (ref "R304") (pin "1") (pinfunction "1_1") (pintype "passive"))
      (node (ref "S301") (pin "3") (pinfunction "2_3") (pintype "passive"))
      (node (ref "S301") (pin "4") (pinfunction "2_4") (pintype "passive"))
      (node (ref "U303") (pin "1") (pinfunction "PB5(NRES)_1") (pintype "bidirectional"))
    )
    (net (code "35") (name "EXO_SCK") (class "Default")
      (node (ref "J301") (pin "3") (pinfunction "3_3") (pintype "passive"))
      (node (ref "R301") (pin "2") (pinfunction "2_2") (pintype "passive"))
      (node (ref "R303") (pin "1") (pinfunction "P$1_1") (pintype "bidirectional"))
      (node (ref "U303") (pin "7") (pinfunction "PB2(SCK/ADC1)_7") (pintype "bidirectional"))
    )
    (net (code "36") (name "EXO_VCC") (class "Default")
      (node (ref "C301") (pin "2") (pinfunction "2_2") (pintype "passive"))
      (node (ref "C302") (pin "+") (pinfunction "+_+") (pintype "passive"))
      (node (ref "D304") (pin "A") (pinfunction "A_A") (pintype "passive"))
      (node (ref "J301") (pin "2") (pinfunction "2_2") (pintype "passive"))
      (node (ref "Q301") (pin "3") (pinfunction "C_3") (pintype "passive"))
      (node (ref "R303") (pin "2") (pinfunction "P$2_2") (pintype "bidirectional"))
      (node (ref "R304") (pin "2") (pinfunction "2_2") (pintype "passive"))
      (node (ref "S302") (pin "1") (pinfunction "O_1") (pintype "passive"))
      (node (ref "U301") (pin "5") (pinfunction "P$V+_5") (pintype "bidirectional"))
      (node (ref "U302") (pin "5") (pinfunction "VCC_5") (pintype "power_in"))
      (node (ref "U303") (pin "8") (pinfunction "VCC_8") (pintype "bidirectional"))
      (node (ref "U304") (pin "5") (pinfunction "OUT_5") (pintype "passive"))
    )
    (net (code "37") (name "EXP_IN") (class "Default")
      (node (ref "D1003") (pin "A") (pinfunction "A_A") (pintype "passive"))
      (node (ref "J1609") (pin "1") (pinfunction "1_1") (pintype "passive"))
      (node (ref "U1001") (pin "2") (pinfunction "PB3(ADC3)_2") (pintype "bidirectional"))
    )
    (net (code "38") (name "EXP_MISO") (class "Default")
      (node (ref "J1005") (pin "1") (pinfunction "1_1") (pintype "passive"))
      (node (ref "U1001") (pin "6") (pinfunction "PB1(MISO)_6") (pintype "bidirectional"))
    )
    (net (code "39") (name "EXP_MOSI") (class "Default")
      (node (ref "J1005") (pin "4") (pinfunction "4_4") (pintype "passive"))
      (node (ref "R1001") (pin "1") (pinfunction "1_1") (pintype "passive"))
      (node (ref "R1002") (pin "1") (pinfunction "1_1") (pintype "passive"))
      (node (ref "U1001") (pin "5") (pinfunction "PB0(MOSI)_5") (pintype "bidirectional"))
    )
    (net (code "40") (name "EXP_OUT") (class "Default")
      (node (ref "D1002") (pin "A") (pinfunction "A_A") (pintype "passive"))
      (node (ref "J1004") (pin "2") (pinfunction "2_2") (pintype "passive"))
      (node (ref "J1610") (pin "2") (pinfunction "2_2") (pintype "passive"))
      (node (ref "R1004") (pin "1") (pinfunction "1_1") (pintype "passive"))
      (node (ref "S1002") (pin "2") (pinfunction "P_2") (pintype "passive"))
    )
    (net (code "41") (name "EXP_RST") (class "Default")
      (node (ref "J1005") (pin "5") (pinfunction "5_5") (pintype "passive"))
      (node (ref "R1005") (pin "1") (pinfunction "1_1") (pintype "passive"))
      (node (ref "S1001") (pin "3") (pinfunction "2_3") (pintype "passive"))
      (node (ref "S1001") (pin "4") (pinfunction "2_4") (pintype "passive"))
      (node (ref "U1001") (pin "1") (pinfunction "PB5(NRES)_1") (pintype "bidirectional"))
    )
    (net (code "42") (name "EXP_SCK") (class "Default")
      (node (ref "J1005") (pin "3") (pinfunction "3_3") (pintype "passive"))
      (node (ref "R1003") (pin "2") (pinfunction "2_2") (pintype "passive"))
      (node (ref "U1001") (pin "7") (pinfunction "PB2(SCK/ADC1)_7") (pintype "bidirectional"))
    )
    (net (code "43") (name "EXP_VCC") (class "Default")
      (node (ref "C1001") (pin "2") (pinfunction "2_2") (pintype "passive"))
      (node (ref "C1002") (pin "+") (pinfunction "+_+") (pintype "passive"))
      (node (ref "D1004") (pin "A") (pinfunction "A_A") (pintype "passive"))
      (node (ref "J1004") (pin "1") (pinfunction "1_1") (pintype "passive"))
      (node (ref "J1005") (pin "2") (pinfunction "2_2") (pintype "passive"))
      (node (ref "R1005") (pin "2") (pinfunction "2_2") (pintype "passive"))
      (node (ref "S1002") (pin "1") (pinfunction "O_1") (pintype "passive"))
      (node (ref "TP1001") (pin "TP") (pinfunction "TP_TP") (pintype "input"))
      (node (ref "U1001") (pin "8") (pinfunction "VCC_8") (pintype "bidirectional"))
      (node (ref "U1002") (pin "5") (pinfunction "OUT_5") (pintype "passive"))
    )
    (net (code "44") (name "GND") (class "Default")
      (node (ref "C1001") (pin "1") (pinfunction "1_1") (pintype "passive"))
      (node (ref "C1002") (pin "-") (pinfunction "-_-") (pintype "passive"))
      (node (ref "C101") (pin "-") (pinfunction "-_-") (pintype "passive"))
      (node (ref "C1101") (pin "1") (pinfunction "1_1") (pintype "passive"))
      (node (ref "C1102") (pin "1") (pinfunction "1_1") (pintype "passive"))
      (node (ref "C1103") (pin "2") (pinfunction "2_2") (pintype "passive"))
      (node (ref "C1201") (pin "1") (pinfunction "1_1") (pintype "passive"))
      (node (ref "C1202") (pin "1") (pinfunction "1_1") (pintype "passive"))
      (node (ref "C1203") (pin "2") (pinfunction "2_2") (pintype "passive"))
      (node (ref "C1301") (pin "1") (pinfunction "1_1") (pintype "passive"))
      (node (ref "C1302") (pin "1") (pinfunction "1_1") (pintype "passive"))
      (node (ref "C1303") (pin "2") (pinfunction "2_2") (pintype "passive"))
      (node (ref "C1401") (pin "-") (pinfunction "-_-") (pintype "passive"))
      (node (ref "C1501") (pin "1") (pinfunction "1_1") (pintype "passive"))
      (node (ref "C1502") (pin "2") (pinfunction "2_2") (pintype "passive"))
      (node (ref "C1601") (pin "-") (pinfunction "-_-") (pintype "passive"))
      (node (ref "C1602") (pin "-") (pinfunction "-_-") (pintype "passive"))
      (node (ref "C1603") (pin "-") (pinfunction "-_-") (pintype "passive"))
      (node (ref "C1604") (pin "2") (pinfunction "2_2") (pintype "passive"))
      (node (ref "C201") (pin "1") (pinfunction "1_1") (pintype "passive"))
      (node (ref "C202") (pin "-") (pinfunction "-_-") (pintype "passive"))
      (node (ref "C301") (pin "1") (pinfunction "1_1") (pintype "passive"))
      (node (ref "C302") (pin "-") (pinfunction "-_-") (pintype "passive"))
      (node (ref "C401") (pin "1") (pinfunction "1_1") (pintype "passive"))
      (node (ref "C402") (pin "-") (pinfunction "-_-") (pintype "passive"))
      (node (ref "C501") (pin "1") (pinfunction "1_1") (pintype "passive"))
      (node (ref "C502") (pin "-") (pinfunction "-_-") (pintype "passive"))
      (node (ref "C601") (pin "1") (pinfunction "1_1") (pintype "passive"))
      (node (ref "C602") (pin "-") (pinfunction "-_-") (pintype "passive"))
      (node (ref "C701") (pin "1") (pinfunction "1_1") (pintype "passive"))
      (node (ref "C702") (pin "1") (pinfunction "1_1") (pintype "passive"))
      (node (ref "C703") (pin "-") (pinfunction "-_-") (pintype "passive"))
      (node (ref "C801") (pin "-") (pinfunction "-_-") (pintype "passive"))
      (node (ref "C901") (pin "1") (pinfunction "1_1") (pintype "passive"))
      (node (ref "C902") (pin "-") (pinfunction "-_-") (pintype "passive"))
      (node (ref "D1601") (pin "A") (pinfunction "A_A") (pintype "passive"))
      (node (ref "D301") (pin "K") (pinfunction "C_K") (pintype "passive"))
      (node (ref "IC1101") (pin "3") (pinfunction "GND_3") (pintype "passive"))
      (node (ref "IC1201") (pin "3") (pinfunction "GND_3") (pintype "passive"))
      (node (ref "IC1301") (pin "3") (pinfunction "GND_3") (pintype "passive"))
      (node (ref "IC1501") (pin "3") (pinfunction "GND_3") (pintype "passive"))
      (node (ref "J1002") (pin "2") (pinfunction "2_2") (pintype "passive"))
      (node (ref "J1003") (pin "2") (pinfunction "2_2") (pintype "passive"))
      (node (ref "J1005") (pin "6") (pinfunction "6_6") (pintype "passive"))
      (node (ref "J1104") (pin "6") (pinfunction "6_6") (pintype "passive"))
      (node (ref "J1204") (pin "6") (pinfunction "6_6") (pintype "passive"))
      (node (ref "J1304") (pin "6") (pinfunction "6_6") (pintype "passive"))
      (node (ref "J1501") (pin "3") (pinfunction "3_3") (pintype "passive"))
      (node (ref "J201") (pin "3") (pinfunction "3_3") (pintype "passive"))
      (node (ref "J202") (pin "2") (pinfunction "2_2") (pintype "passive"))
      (node (ref "J204") (pin "6") (pinfunction "6_6") (pintype "passive"))
      (node (ref "J301") (pin "6") (pinfunction "6_6") (pintype "passive"))
      (node (ref "J401") (pin "6") (pinfunction "6_6") (pintype "passive"))
      (node (ref "J501") (pin "2") (pinfunction "2_2") (pintype "passive"))
      (node (ref "J503") (pin "6") (pinfunction "6_6") (pintype "passive"))
      (node (ref "J601") (pin "2") (pinfunction "2_2") (pintype "passive"))
      (node (ref "J603") (pin "6") (pinfunction "6_6") (pintype "passive"))
      (node (ref "J701") (pin "2") (pinfunction "2_2") (pintype "passive"))
      (node (ref "J703") (pin "6") (pinfunction "6_6") (pintype "passive"))
      (node (ref "J704") (pin "6") (pinfunction "6_6") (pintype "passive"))
      (node (ref "J903") (pin "6") (pinfunction "6_6") (pintype "passive"))
      (node (ref "Q1001") (pin "1") (pinfunction "S_1") (pintype "passive"))
      (node (ref "Q1001") (pin "2") (pinfunction "S_2") (pintype "passive"))
      (node (ref "Q1001") (pin "3") (pinfunction "S_3") (pintype "passive"))
      (node (ref "Q1401") (pin "1") (pinfunction "S_1") (pintype "passive"))
      (node (ref "Q1401") (pin "2") (pinfunction "S_2") (pintype "passive"))
      (node (ref "Q1401") (pin "3") (pinfunction "S_3") (pintype "passive"))
      (node (ref "Q201") (pin "1") (pinfunction "S_1") (pintype "passive"))
      (node (ref "Q201") (pin "2") (pinfunction "S_2") (pintype "passive"))
      (node (ref "Q201") (pin "3") (pinfunction "S_3") (pintype "passive"))
      (node (ref "Q501") (pin "1") (pinfunction "S_1") (pintype "passive"))
      (node (ref "Q501") (pin "2") (pinfunction "S_2") (pintype "passive"))
      (node (ref "Q501") (pin "3") (pinfunction "S_3") (pintype "passive"))
      (node (ref "Q601") (pin "1") (pinfunction "S_1") (pintype "passive"))
      (node (ref "Q601") (pin "2") (pinfunction "S_2") (pintype "passive"))
      (node (ref "Q601") (pin "3") (pinfunction "S_3") (pintype "passive"))
      (node (ref "Q801") (pin "1") (pinfunction "S_1") (pintype "passive"))
      (node (ref "Q801") (pin "2") (pinfunction "S_2") (pintype "passive"))
      (node (ref "Q801") (pin "3") (pinfunction "S_3") (pintype "passive"))
      (node (ref "Q901") (pin "1") (pinfunction "S_1") (pintype "passive"))
      (node (ref "Q901") (pin "2") (pinfunction "S_2") (pintype "passive"))
      (node (ref "Q901") (pin "3") (pinfunction "S_3") (pintype "passive"))
      (node (ref "R1002") (pin "2") (pinfunction "2_2") (pintype "passive"))
      (node (ref "R1004") (pin "2") (pinfunction "2_2") (pintype "passive"))
      (node (ref "R1006") (pin "1") (pinfunction "1_1") (pintype "passive"))
      (node (ref "R1007") (pin "1") (pinfunction "1_1") (pintype "passive"))
      (node (ref "R1008") (pin "1") (pinfunction "1_1") (pintype "passive"))
      (node (ref "R102") (pin "1") (pinfunction "1_1") (pintype "passive"))
      (node (ref "R103") (pin "1") (pinfunction "1_1") (pintype "passive"))
      (node (ref "R1101") (pin "2") (pinfunction "2_2") (pintype "passive"))
      (node (ref "R1102") (pin "2") (pinfunction "2_2") (pintype "passive"))
      (node (ref "R1104") (pin "1") (pinfunction "1_1") (pintype "passive"))
      (node (ref "R1105") (pin "1") (pinfunction "1_1") (pintype "passive"))
      (node (ref "R1106") (pin "1") (pinfunction "1_1") (pintype "passive"))
      (node (ref "R1201") (pin "2") (pinfunction "2_2") (pintype "passive"))
      (node (ref "R1202") (pin "2") (pinfunction "2_2") (pintype "passive"))
      (node (ref "R1204") (pin "1") (pinfunction "1_1") (pintype "passive"))
      (node (ref "R1205") (pin "1") (pinfunction "1_1") (pintype "passive"))
      (node (ref "R1206") (pin "1") (pinfunction "1_1") (pintype "passive"))
      (node (ref "R1301") (pin "2") (pinfunction "2_2") (pintype "passive"))
      (node (ref "R1302") (pin "2") (pinfunction "2_2") (pintype "passive"))
      (node (ref "R1304") (pin "1") (pinfunction "1_1") (pintype "passive"))
      (node (ref "R1305") (pin "1") (pinfunction "1_1") (pintype "passive"))
      (node (ref "R1306") (pin "1") (pinfunction "1_1") (pintype "passive"))
      (node (ref "R1401") (pin "2") (pinfunction "2_2") (pintype "passive"))
      (node (ref "R1403") (pin "2") (pinfunction "2_2") (pintype "passive"))
      (node (ref "R1404") (pin "1") (pinfunction "1_1") (pintype "passive"))
      (node (ref "R1405") (pin "1") (pinfunction "1_1") (pintype "passive"))
      (node (ref "R1406") (pin "1") (pinfunction "1_1") (pintype "passive"))
      (node (ref "R1501") (pin "1") (pinfunction "1_1") (pintype "passive"))
      (node (ref "R1502") (pin "1") (pinfunction "1_1") (pintype "passive"))
      (node (ref "R1503") (pin "1") (pinfunction "1_1") (pintype "passive"))
      (node (ref "R202") (pin "2") (pinfunction "2_2") (pintype "passive"))
      (node (ref "R205") (pin "1") (pinfunction "1_1") (pintype "passive"))
      (node (ref "R206") (pin "1") (pinfunction "1_1") (pintype "passive"))
      (node (ref "R207") (pin "1") (pinfunction "1_1") (pintype "passive"))
      (node (ref "R301") (pin "1") (pinfunction "1_1") (pintype "passive"))
      (node (ref "R305") (pin "1") (pinfunction "1_1") (pintype "passive"))
      (node (ref "R306") (pin "1") (pinfunction "1_1") (pintype "passive"))
      (node (ref "R307") (pin "1") (pinfunction "1_1") (pintype "passive"))
      (node (ref "R401") (pin "1") (pinfunction "1_1") (pintype "passive"))
      (node (ref "R404") (pin "2") (pinfunction "2_2") (pintype "passive"))
      (node (ref "R406") (pin "1") (pinfunction "1_1") (pintype "passive"))
      (node (ref "R407") (pin "1") (pinfunction "1_1") (pintype "passive"))
      (node (ref "R408") (pin "1") (pinfunction "1_1") (pintype "passive"))
      (node (ref "R503") (pin "2") (pinfunction "2_2") (pintype "passive"))
      (node (ref "R505") (pin "1") (pinfunction "1_1") (pintype "passive"))
      (node (ref "R506") (pin "1") (pinfunction "1_1") (pintype "passive"))
      (node (ref "R507") (pin "1") (pinfunction "1_1") (pintype "passive"))
      (node (ref "R602") (pin "2") (pinfunction "2_2") (pintype "passive"))
      (node (ref "R605") (pin "1") (pinfunction "1_1") (pintype "passive"))
      (node (ref "R606") (pin "1") (pinfunction "1_1") (pintype "passive"))
      (node (ref "R607") (pin "1") (pinfunction "1_1") (pintype "passive"))
      (node (ref "R705") (pin "1") (pinfunction "1_1") (pintype "passive"))
      (node (ref "R706") (pin "1") (pinfunction "1_1") (pintype "passive"))
      (node (ref "R707") (pin "1") (pinfunction "1_1") (pintype "passive"))
      (node (ref "R801") (pin "1") (pinfunction "1_1") (pintype "passive"))
      (node (ref "R803") (pin "2") (pinfunction "2_2") (pintype "passive"))
      (node (ref "R804") (pin "1") (pinfunction "1_1") (pintype "passive"))
      (node (ref "R805") (pin "1") (pinfunction "1_1") (pintype "passive"))
      (node (ref "R806") (pin "1") (pinfunction "1_1") (pintype "passive"))
      (node (ref "R902") (pin "2") (pinfunction "2_2") (pintype "passive"))
      (node (ref "R903") (pin "2") (pinfunction "2_2") (pintype "passive"))
      (node (ref "R905") (pin "1") (pinfunction "1_1") (pintype "passive"))
      (node (ref "R906") (pin "1") (pinfunction "1_1") (pintype "passive"))
      (node (ref "R907") (pin "1") (pinfunction "1_1") (pintype "passive"))
      (node (ref "S1001") (pin "1") (pinfunction "1_1") (pintype "passive"))
      (node (ref "S1001") (pin "2") (pinfunction "1_2") (pintype "passive"))
      (node (ref "S101") (pin "P$1") (pinfunction "1_P$1") (pintype "passive"))
      (node (ref "S1101") (pin "1") (pinfunction "1_1") (pintype "passive"))
      (node (ref "S1101") (pin "2") (pinfunction "1_2") (pintype "passive"))
      (node (ref "S1201") (pin "1") (pinfunction "1_1") (pintype "passive"))
      (node (ref "S1201") (pin "2") (pinfunction "1_2") (pintype "passive"))
      (node (ref "S1301") (pin "1") (pinfunction "1_1") (pintype "passive"))
      (node (ref "S1301") (pin "2") (pinfunction "1_2") (pintype "passive"))
      (node (ref "S201") (pin "1") (pinfunction "1_1") (pintype "passive"))
      (node (ref "S201") (pin "2") (pinfunction "1_2") (pintype "passive"))
      (node (ref "S301") (pin "1") (pinfunction "1_1") (pintype "passive"))
      (node (ref "S301") (pin "2") (pinfunction "1_2") (pintype "passive"))
      (node (ref "S401") (pin "1") (pinfunction "1_1") (pintype "passive"))
      (node (ref "S401") (pin "2") (pinfunction "1_2") (pintype "passive"))
      (node (ref "S501") (pin "1") (pinfunction "1_1") (pintype "passive"))
      (node (ref "S501") (pin "2") (pinfunction "1_2") (pintype "passive"))
      (node (ref "S601") (pin "1") (pinfunction "1_1") (pintype "passive"))
      (node (ref "S601") (pin "2") (pinfunction "1_2") (pintype "passive"))
      (node (ref "S701") (pin "1") (pinfunction "1_1") (pintype "passive"))
      (node (ref "S701") (pin "2") (pinfunction "1_2") (pintype "passive"))
      (node (ref "S702") (pin "1") (pinfunction "1_1") (pintype "passive"))
      (node (ref "S702") (pin "2") (pinfunction "1_2") (pintype "passive"))
      (node (ref "S901") (pin "1") (pinfunction "1_1") (pintype "passive"))
      (node (ref "S901") (pin "2") (pinfunction "1_2") (pintype "passive"))
      (node (ref "U1001") (pin "4") (pinfunction "GND_4") (pintype "bidirectional"))
      (node (ref "U1002") (pin "2") (pinfunction "GND_2") (pintype "input"))
      (node (ref "U101") (pin "3") (pinfunction "P$V-_3") (pintype "bidirectional"))
      (node (ref "U102") (pin "2") (pinfunction "GND_2") (pintype "input"))
      (node (ref "U1101") (pin "6") (pinfunction "VSS_6") (pintype "bidirectional"))
      (node (ref "U1101") (pin "PAD") (pinfunction "VSS_PAD") (pintype "bidirectional"))
      (node (ref "U1102") (pin "4") (pinfunction "GND_4") (pintype "bidirectional"))
      (node (ref "U1201") (pin "6") (pinfunction "VSS_6") (pintype "bidirectional"))
      (node (ref "U1201") (pin "PAD") (pinfunction "VSS_PAD") (pintype "bidirectional"))
      (node (ref "U1202") (pin "4") (pinfunction "GND_4") (pintype "bidirectional"))
      (node (ref "U1301") (pin "6") (pinfunction "VSS_6") (pintype "bidirectional"))
      (node (ref "U1301") (pin "PAD") (pinfunction "VSS_PAD") (pintype "bidirectional"))
      (node (ref "U1302") (pin "4") (pinfunction "GND_4") (pintype "bidirectional"))
      (node (ref "U1401") (pin "3") (pinfunction "P$V-_3") (pintype "bidirectional"))
      (node (ref "U1402") (pin "2") (pinfunction "GND_2") (pintype "input"))
      (node (ref "U201") (pin "3") (pinfunction "P$V-_3") (pintype "bidirectional"))
      (node (ref "U202") (pin "4") (pinfunction "GND_4") (pintype "bidirectional"))
      (node (ref "U203") (pin "2") (pinfunction "GND_2") (pintype "input"))
      (node (ref "U301") (pin "3") (pinfunction "P$V-_3") (pintype "bidirectional"))
      (node (ref "U302") (pin "3") (pinfunction "GND_3") (pintype "power_in"))
      (node (ref "U303") (pin "4") (pinfunction "GND_4") (pintype "bidirectional"))
      (node (ref "U304") (pin "2") (pinfunction "GND_2") (pintype "input"))
      (node (ref "U401") (pin "3") (pinfunction "P$V-_3") (pintype "bidirectional"))
      (node (ref "U402") (pin "3") (pinfunction "GND_3") (pintype "power_in"))
      (node (ref "U403") (pin "4") (pinfunction "GND_4") (pintype "bidirectional"))
      (node (ref "U404") (pin "2") (pinfunction "GND_2") (pintype "input"))
      (node (ref "U501") (pin "3") (pinfunction "P$V-_3") (pintype "bidirectional"))
      (node (ref "U502") (pin "3") (pinfunction "GND_3") (pintype "power_in"))
      (node (ref "U503") (pin "4") (pinfunction "GND_4") (pintype "bidirectional"))
      (node (ref "U504") (pin "2") (pinfunction "GND_2") (pintype "input"))
      (node (ref "U601") (pin "3") (pinfunction "P$V-_3") (pintype "bidirectional"))
      (node (ref "U602") (pin "3") (pinfunction "GND_3") (pintype "power_in"))
      (node (ref "U603") (pin "4") (pinfunction "GND_4") (pintype "bidirectional"))
      (node (ref "U604") (pin "2") (pinfunction "GND_2") (pintype "input"))
      (node (ref "U701") (pin "4") (pinfunction "GND_4") (pintype "bidirectional"))
      (node (ref "U702") (pin "4") (pinfunction "GND_4") (pintype "bidirectional"))
      (node (ref "U703") (pin "2") (pinfunction "GND_2") (pintype "input"))
      (node (ref "U801") (pin "3") (pinfunction "P$V-_3") (pintype "bidirectional"))
      (node (ref "U802") (pin "3") (pinfunction "GND_3") (pintype "power_in"))
      (node (ref "U803") (pin "2") (pinfunction "GND_2") (pintype "input"))
      (node (ref "U901") (pin "4") (pinfunction "GND_4") (pintype "bidirectional"))
      (node (ref "U902") (pin "2") (pinfunction "GND_2") (pintype "input"))
      (node (ref "X1601") (pin "2") (pinfunction "1_2") (pintype "passive"))
    )
    (net (code "45") (name "IMA0.5_IN") (class "Default")
      (node (ref "D1403") (pin "A") (pinfunction "A_A") (pintype "passive"))
      (node (ref "J1613") (pin "1") (pinfunction "1_1") (pintype "passive"))
      (node (ref "JP1401") (pin "1") (pinfunction "1_1") (pintype "passive"))
      (node (ref "U1401") (pin "2") (pinfunction "A_2") (pintype "bidirectional"))
    )
    (net (code "46") (name "IMA0.5_OUT") (class "Default")
      (node (ref "D1402") (pin "A") (pinfunction "A_A") (pintype "passive"))
      (node (ref "J1401") (pin "2") (pinfunction "2_2") (pintype "passive"))
      (node (ref "J1614") (pin "2") (pinfunction "2_2") (pintype "passive"))
      (node (ref "R1401") (pin "1") (pinfunction "1_1") (pintype "passive"))
      (node (ref "S1401") (pin "2") (pinfunction "P_2") (pintype "passive"))
    )
    (net (code "47") (name "IMA0.5_VCC") (class "Default")
      (node (ref "C1401") (pin "+") (pinfunction "+_+") (pintype "passive"))
      (node (ref "D1404") (pin "A") (pinfunction "A_A") (pintype "passive"))
      (node (ref "J1401") (pin "1") (pinfunction "1_1") (pintype "passive"))
      (node (ref "S1401") (pin "1") (pinfunction "O_1") (pintype "passive"))
      (node (ref "TP1402") (pin "TP") (pinfunction "TP_TP") (pintype "input"))
      (node (ref "U1401") (pin "5") (pinfunction "P$V+_5") (pintype "bidirectional"))
      (node (ref "U1402") (pin "5") (pinfunction "OUT_5") (pintype "passive"))
    )
    (net (code "48") (name "IMA7_IN") (class "Default")
      (node (ref "D1302") (pin "A") (pinfunction "A_A") (pintype "passive"))
      (node (ref "J1612") (pin "1") (pinfunction "1_1") (pintype "passive"))
      (node (ref "U1302") (pin "2") (pinfunction "PB3(ADC3)_2") (pintype "bidirectional"))
    )
    (net (code "49") (name "IMA7_MISO") (class "Default")
      (node (ref "J1304") (pin "1") (pinfunction "1_1") (pintype "passive"))
      (node (ref "U1301") (pin "9") (pinfunction "AIN2/EN_9") (pintype "bidirectional"))
      (node (ref "U1302") (pin "6") (pinfunction "PB1(MISO)_6") (pintype "bidirectional"))
    )
    (net (code "50") (name "IMA7_MOSI") (class "Default")
      (node (ref "J1304") (pin "4") (pinfunction "4_4") (pintype "passive"))
      (node (ref "U1301") (pin "10") (pinfunction "AIN1/PH_10") (pintype "bidirectional"))
      (node (ref "U1302") (pin "5") (pinfunction "PB0(MOSI)_5") (pintype "bidirectional"))
    )
    (net (code "51") (name "IMA7_OUT") (class "Default")
      (node (ref "D1301") (pin "A") (pinfunction "A_A") (pintype "passive"))
      (node (ref "J1301") (pin "2") (pinfunction "2_2") (pintype "passive"))
      (node (ref "J1613") (pin "2") (pinfunction "2_2") (pintype "passive"))
      (node (ref "R1301") (pin "1") (pinfunction "1_1") (pintype "passive"))
      (node (ref "S1302") (pin "2") (pinfunction "P_2") (pintype "passive"))
    )
    (net (code "52") (name "IMA7_RST") (class "Default")
      (node (ref "J1304") (pin "5") (pinfunction "5_5") (pintype "passive"))
      (node (ref "R1303") (pin "1") (pinfunction "1_1") (pintype "passive"))
      (node (ref "S1301") (pin "3") (pinfunction "2_3") (pintype "passive"))
      (node (ref "S1301") (pin "4") (pinfunction "2_4") (pintype "passive"))
      (node (ref "U1302") (pin "1") (pinfunction "PB5(NRES)_1") (pintype "bidirectional"))
    )
    (net (code "53") (name "IMA7_SCK") (class "Default")
      (node (ref "J1302") (pin "2") (pinfunction "2_2") (pintype "passive"))
      (node (ref "J1304") (pin "3") (pinfunction "3_3") (pintype "passive"))
      (node (ref "R1302") (pin "1") (pinfunction "1_1") (pintype "passive"))
      (node (ref "U1302") (pin "7") (pinfunction "PB2(SCK/ADC1)_7") (pintype "bidirectional"))
    )
    (net (code "54") (name "IMA7_VCC") (class "Default")
      (node (ref "C1301") (pin "2") (pinfunction "2_2") (pintype "passive"))
      (node (ref "C1303") (pin "1") (pinfunction "1_1") (pintype "passive"))
      (node (ref "D1303") (pin "A") (pinfunction "A_A") (pintype "passive"))
      (node (ref "IC1301") (pin "2") (pinfunction "VO_2") (pintype "passive"))
      (node (ref "J1301") (pin "1") (pinfunction "1_1") (pintype "passive"))
      (node (ref "J1302") (pin "1") (pinfunction "1_1") (pintype "passive"))
      (node (ref "J1304") (pin "2") (pinfunction "2_2") (pintype "passive"))
      (node (ref "R1303") (pin "2") (pinfunction "2_2") (pintype "passive"))
      (node (ref "S1302") (pin "1") (pinfunction "O_1") (pintype "passive"))
      (node (ref "TP1301") (pin "TP") (pinfunction "TP_TP") (pintype "input"))
      (node (ref "U1301") (pin "1") (pinfunction "VM_1") (pintype "bidirectional"))
      (node (ref "U1301") (pin "11") (pinfunction "MODE_11") (pintype "bidirectional"))
      (node (ref "U1301") (pin "12") (pinfunction "VCC_12") (pintype "bidirectional"))
      (node (ref "U1302") (pin "8") (pinfunction "VCC_8") (pintype "bidirectional"))
    )
    (net (code "55") (name "IR_1_MISO") (class "Default")
      (node (ref "J702") (pin "1") (pinfunction "1_1") (pintype "passive"))
      (node (ref "J704") (pin "1") (pinfunction "1_1") (pintype "passive"))
      (node (ref "U702") (pin "6") (pinfunction "PB1(MISO)_6") (pintype "bidirectional"))
    )
    (net (code "56") (name "IR_1_MOSI") (class "Default")
      (node (ref "J704") (pin "4") (pinfunction "4_4") (pintype "passive"))
      (node (ref "U702") (pin "5") (pinfunction "PB0(MOSI)_5") (pintype "bidirectional"))
    )
    (net (code "57") (name "IR_1_RST") (class "Default")
      (node (ref "J704") (pin "5") (pinfunction "5_5") (pintype "passive"))
      (node (ref "R704") (pin "1") (pinfunction "1_1") (pintype "passive"))
      (node (ref "S702") (pin "3") (pinfunction "2_3") (pintype "passive"))
      (node (ref "S702") (pin "4") (pinfunction "2_4") (pintype "passive"))
      (node (ref "U702") (pin "1") (pinfunction "PB5(NRES)_1") (pintype "bidirectional"))
    )
    (net (code "58") (name "IR_1_SCK") (class "Default")
      (node (ref "J704") (pin "3") (pinfunction "3_3") (pintype "passive"))
      (node (ref "U702") (pin "7") (pinfunction "PB2(SCK/ADC1)_7") (pintype "bidirectional"))
    )
    (net (code "59") (name "IR_2_MISO") (class "Default")
      (node (ref "J703") (pin "1") (pinfunction "1_1") (pintype "passive"))
      (node (ref "U701") (pin "6") (pinfunction "PB1(MISO)_6") (pintype "bidirectional"))
    )
    (net (code "60") (name "IR_2_MOSI") (class "Default")
      (node (ref "J703") (pin "4") (pinfunction "4_4") (pintype "passive"))
      (node (ref "U701") (pin "5") (pinfunction "PB0(MOSI)_5") (pintype "bidirectional"))
    )
    (net (code "61") (name "IR_2_RST") (class "Default")
      (node (ref "J703") (pin "5") (pinfunction "5_5") (pintype "passive"))
      (node (ref "R703") (pin "1") (pinfunction "1_1") (pintype "passive"))
      (node (ref "S701") (pin "3") (pinfunction "2_3") (pintype "passive"))
      (node (ref "S701") (pin "4") (pinfunction "2_4") (pintype "passive"))
      (node (ref "U701") (pin "1") (pinfunction "PB5(NRES)_1") (pintype "bidirectional"))
    )
    (net (code "62") (name "IR_2_SCK") (class "Default")
      (node (ref "J703") (pin "3") (pinfunction "3_3") (pintype "passive"))
      (node (ref "R702") (pin "1") (pinfunction "1_1") (pintype "passive"))
      (node (ref "U701") (pin "7") (pinfunction "PB2(SCK/ADC1)_7") (pintype "bidirectional"))
    )
    (net (code "63") (name "IR_IN") (class "Default")
      (node (ref "D702") (pin "A") (pinfunction "A_A") (pintype "passive"))
      (node (ref "J1606") (pin "1") (pinfunction "1_1") (pintype "passive"))
      (node (ref "U702") (pin "2") (pinfunction "PB3(ADC3)_2") (pintype "bidirectional"))
    )
    (net (code "64") (name "IR_OUT") (class "Default")
      (node (ref "D701") (pin "A") (pinfunction "A_A") (pintype "passive"))
      (node (ref "J1607") (pin "2") (pinfunction "2_2") (pintype "passive"))
      (node (ref "S703") (pin "2") (pinfunction "P_2") (pintype "passive"))
    )
    (net (code "65") (name "IR_OUT_SWITCH") (class "Default")
      (node (ref "S703") (pin "3") (pinfunction "S_3") (pintype "passive"))
      (node (ref "U701") (pin "3") (pinfunction "PB4(ADC2)_3") (pintype "bidirectional"))
    )
    (net (code "66") (name "IR_VCC") (class "Default")
      (node (ref "C701") (pin "2") (pinfunction "2_2") (pintype "passive"))
      (node (ref "C702") (pin "2") (pinfunction "2_2") (pintype "passive"))
      (node (ref "C703") (pin "+") (pinfunction "+_+") (pintype "passive"))
      (node (ref "D703") (pin "A") (pinfunction "A_A") (pintype "passive"))
      (node (ref "J701") (pin "3") (pinfunction "3_3") (pintype "passive"))
      (node (ref "J703") (pin "2") (pinfunction "2_2") (pintype "passive"))
      (node (ref "J704") (pin "2") (pinfunction "2_2") (pintype "passive"))
      (node (ref "R701") (pin "1") (pinfunction "1_1") (pintype "passive"))
      (node (ref "R703") (pin "2") (pinfunction "2_2") (pintype "passive"))
      (node (ref "R704") (pin "2") (pinfunction "2_2") (pintype "passive"))
      (node (ref "S703") (pin "1") (pinfunction "O_1") (pintype "passive"))
      (node (ref "TP701") (pin "TP") (pinfunction "TP_TP") (pintype "input"))
      (node (ref "U701") (pin "8") (pinfunction "VCC_8") (pintype "bidirectional"))
      (node (ref "U702") (pin "8") (pinfunction "VCC_8") (pintype "bidirectional"))
      (node (ref "U703") (pin "5") (pinfunction "OUT_5") (pintype "passive"))
    )
    (net (code "67") (name "LEVER_IN") (class "Default")
      (node (ref "D903") (pin "A") (pinfunction "A_A") (pintype "passive"))
      (node (ref "J1608") (pin "1") (pinfunction "1_1") (pintype "passive"))
      (node (ref "U901") (pin "2") (pinfunction "PB3(ADC3)_2") (pintype "bidirectional"))
    )
    (net (code "68") (name "LEVER_MISO") (class "Default")
      (node (ref "J903") (pin "1") (pinfunction "1_1") (pintype "passive"))
      (node (ref "U901") (pin "6") (pinfunction "PB1(MISO)_6") (pintype "bidirectional"))
    )
    (net (code "69") (name "LEVER_MOSI") (class "Default")
      (node (ref "J903") (pin "4") (pinfunction "4_4") (pintype "passive"))
      (node (ref "U901") (pin "5") (pinfunction "PB0(MOSI)_5") (pintype "bidirectional"))
    )
    (net (code "70") (name "LEVER_OUT") (class "Default")
      (node (ref "D902") (pin "A") (pinfunction "A_A") (pintype "passive"))
      (node (ref "J1609") (pin "2") (pinfunction "2_2") (pintype "passive"))
      (node (ref "J901") (pin "2") (pinfunction "2_2") (pintype "passive"))
      (node (ref "R903") (pin "1") (pinfunction "1_1") (pintype "passive"))
      (node (ref "S902") (pin "2") (pinfunction "P_2") (pintype "passive"))
    )
    (net (code "71") (name "LEVER_RST") (class "Default")
      (node (ref "J903") (pin "5") (pinfunction "5_5") (pintype "passive"))
      (node (ref "R904") (pin "1") (pinfunction "1_1") (pintype "passive"))
      (node (ref "S901") (pin "3") (pinfunction "2_3") (pintype "passive"))
      (node (ref "S901") (pin "4") (pinfunction "2_4") (pintype "passive"))
      (node (ref "U901") (pin "1") (pinfunction "PB5(NRES)_1") (pintype "bidirectional"))
    )
    (net (code "72") (name "LEVER_SCK") (class "Default")
      (node (ref "J903") (pin "3") (pinfunction "3_3") (pintype "passive"))
      (node (ref "R901") (pin "1") (pinfunction "1_1") (pintype "passive"))
      (node (ref "R902") (pin "1") (pinfunction "1_1") (pintype "passive"))
      (node (ref "U901") (pin "7") (pinfunction "PB2(SCK/ADC1)_7") (pintype "bidirectional"))
    )
    (net (code "73") (name "LEVER_VCC") (class "Default")
      (node (ref "C901") (pin "2") (pinfunction "2_2") (pintype "passive"))
      (node (ref "C902") (pin "+") (pinfunction "+_+") (pintype "passive"))
      (node (ref "D904") (pin "A") (pinfunction "A_A") (pintype "passive"))
      (node (ref "J901") (pin "1") (pinfunction "1_1") (pintype "passive"))
      (node (ref "J903") (pin "2") (pinfunction "2_2") (pintype "passive"))
      (node (ref "R904") (pin "2") (pinfunction "2_2") (pintype "passive"))
      (node (ref "S902") (pin "1") (pinfunction "O_1") (pintype "passive"))
      (node (ref "TP901") (pin "TP") (pinfunction "TP_TP") (pintype "input"))
      (node (ref "U901") (pin "8") (pinfunction "VCC_8") (pintype "bidirectional"))
      (node (ref "U902") (pin "5") (pinfunction "OUT_5") (pintype "passive"))
    )
    (net (code "74") (name "LIGHT_IN") (class "Default")
      (node (ref "D403") (pin "A") (pinfunction "A_A") (pintype "passive"))
      (node (ref "J1603") (pin "1") (pinfunction "1_1") (pintype "passive"))
      (node (ref "U402") (pin "1") (pinfunction "A_1") (pintype "input"))
    )
    (net (code "75") (name "LIGHT_MISO") (class "Default")
      (node (ref "J401") (pin "1") (pinfunction "1_1") (pintype "passive"))
      (node (ref "U403") (pin "6") (pinfunction "PB1(MISO)_6") (pintype "bidirectional"))
    )
    (net (code "76") (name "LIGHT_MOSI") (class "Default")
      (node (ref "J401") (pin "4") (pinfunction "4_4") (pintype "passive"))
      (node (ref "U403") (pin "5") (pinfunction "PB0(MOSI)_5") (pintype "bidirectional"))
    )
    (net (code "77") (name "LIGHT_OUT") (class "Default")
      (node (ref "D402") (pin "A") (pinfunction "A_A") (pintype "passive"))
      (node (ref "J1604") (pin "2") (pinfunction "2_2") (pintype "passive"))
      (node (ref "S402") (pin "2") (pinfunction "P_2") (pintype "passive"))
      (node (ref "U401") (pin "2") (pinfunction "A_2") (pintype "bidirectional"))
    )
    (net (code "78") (name "LIGHT_OUT_SWITCH") (class "Default")
      (node (ref "S402") (pin "3") (pinfunction "S_3") (pintype "passive"))
      (node (ref "U403") (pin "3") (pinfunction "PB4(ADC2)_3") (pintype "bidirectional"))
    )
    (net (code "79") (name "LIGHT_RST") (class "Default")
      (node (ref "J401") (pin "5") (pinfunction "5_5") (pintype "passive"))
      (node (ref "R405") (pin "1") (pinfunction "1_1") (pintype "passive"))
      (node (ref "S401") (pin "3") (pinfunction "2_3") (pintype "passive"))
      (node (ref "S401") (pin "4") (pinfunction "2_4") (pintype "passive"))
      (node (ref "U403") (pin "1") (pinfunction "PB5(NRES)_1") (pintype "bidirectional"))
    )
    (net (code "80") (name "LIGHT_SCK") (class "Default")
      (node (ref "J401") (pin "3") (pinfunction "3_3") (pintype "passive"))
      (node (ref "R401") (pin "2") (pinfunction "2_2") (pintype "passive"))
      (node (ref "R402") (pin "1") (pinfunction "P$1_1") (pintype "bidirectional"))
      (node (ref "U403") (pin "7") (pinfunction "PB2(SCK/ADC1)_7") (pintype "bidirectional"))
    )
    (net (code "81") (name "LIGHT_VCC") (class "Default")
      (node (ref "C401") (pin "2") (pinfunction "2_2") (pintype "passive"))
      (node (ref "C402") (pin "+") (pinfunction "+_+") (pintype "passive"))
      (node (ref "D404") (pin "A") (pinfunction "A_A") (pintype "passive"))
      (node (ref "J401") (pin "2") (pinfunction "2_2") (pintype "passive"))
      (node (ref "Q401") (pin "3") (pinfunction "C_3") (pintype "passive"))
      (node (ref "R402") (pin "2") (pinfunction "P$2_2") (pintype "bidirectional"))
      (node (ref "R405") (pin "2") (pinfunction "2_2") (pintype "passive"))
      (node (ref "S402") (pin "1") (pinfunction "O_1") (pintype "passive"))
      (node (ref "TP403") (pin "TP") (pinfunction "TP_TP") (pintype "input"))
      (node (ref "U401") (pin "5") (pinfunction "P$V+_5") (pintype "bidirectional"))
      (node (ref "U402") (pin "5") (pinfunction "VCC_5") (pintype "power_in"))
      (node (ref "U403") (pin "8") (pinfunction "VCC_8") (pintype "bidirectional"))
      (node (ref "U404") (pin "5") (pinfunction "OUT_5") (pintype "passive"))
    )
    (net (code "82") (name "Net-(D101-PadC)") (class "Default")
      (node (ref "D101") (pin "C") (pinfunction "C_C") (pintype "passive"))
      (node (ref "R102") (pin "2") (pinfunction "2_2") (pintype "passive"))
    )
    (net (code "83") (name "Net-(D102-PadC)") (class "Default")
      (node (ref "D102") (pin "C") (pinfunction "C_C") (pintype "passive"))
      (node (ref "R103") (pin "2") (pinfunction "2_2") (pintype "passive"))
    )
    (net (code "84") (name "Net-(D202-PadC)") (class "Default")
      (node (ref "D202") (pin "C") (pinfunction "C_C") (pintype "passive"))
      (node (ref "R205") (pin "2") (pinfunction "2_2") (pintype "passive"))
    )
    (net (code "85") (name "Net-(D203-PadC)") (class "Default")
      (node (ref "D203") (pin "C") (pinfunction "C_C") (pintype "passive"))
      (node (ref "R206") (pin "2") (pinfunction "2_2") (pintype "passive"))
    )
    (net (code "86") (name "Net-(D204-PadC)") (class "Default")
      (node (ref "D204") (pin "C") (pinfunction "C_C") (pintype "passive"))
      (node (ref "R207") (pin "2") (pinfunction "2_2") (pintype "passive"))
    )
    (net (code "87") (name "Net-(D302-PadC)") (class "Default")
      (node (ref "D302") (pin "C") (pinfunction "C_C") (pintype "passive"))
      (node (ref "R305") (pin "2") (pinfunction "2_2") (pintype "passive"))
    )
    (net (code "88") (name "Net-(D303-PadC)") (class "Default")
      (node (ref "D303") (pin "C") (pinfunction "C_C") (pintype "passive"))
      (node (ref "R306") (pin "2") (pinfunction "2_2") (pintype "passive"))
    )
    (net (code "89") (name "Net-(D304-PadC)") (class "Default")
      (node (ref "D304") (pin "C") (pinfunction "C_C") (pintype "passive"))
      (node (ref "R307") (pin "2") (pinfunction "2_2") (pintype "passive"))
    )
    (net (code "90") (name "Net-(D401-C)") (class "Default")
      (node (ref "D401") (pin "K") (pinfunction "C_K") (pintype "passive"))
      (node (ref "R404") (pin "1") (pinfunction "1_1") (pintype "passive"))
    )
    (net (code "91") (name "Net-(D402-PadC)") (class "Default")
      (node (ref "D402") (pin "C") (pinfunction "C_C") (pintype "passive"))
      (node (ref "R406") (pin "2") (pinfunction "2_2") (pintype "passive"))
    )
    (net (code "92") (name "Net-(D403-PadC)") (class "Default")
      (node (ref "D403") (pin "C") (pinfunction "C_C") (pintype "passive"))
      (node (ref "R407") (pin "2") (pinfunction "2_2") (pintype "passive"))
    )
    (net (code "93") (name "Net-(D404-PadC)") (class "Default")
      (node (ref "D404") (pin "C") (pinfunction "C_C") (pintype "passive"))
      (node (ref "R408") (pin "2") (pinfunction "2_2") (pintype "passive"))
    )
    (net (code "94") (name "Net-(D502-PadC)") (class "Default")
      (node (ref "D502") (pin "C") (pinfunction "C_C") (pintype "passive"))
      (node (ref "R505") (pin "2") (pinfunction "2_2") (pintype "passive"))
    )
    (net (code "95") (name "Net-(D503-PadC)") (class "Default")
      (node (ref "D503") (pin "C") (pinfunction "C_C") (pintype "passive"))
      (node (ref "R506") (pin "2") (pinfunction "2_2") (pintype "passive"))
    )
    (net (code "96") (name "Net-(D504-PadC)") (class "Default")
      (node (ref "D504") (pin "C") (pinfunction "C_C") (pintype "passive"))
      (node (ref "R507") (pin "2") (pinfunction "2_2") (pintype "passive"))
    )
    (net (code "97") (name "Net-(D602-PadC)") (class "Default")
      (node (ref "D602") (pin "C") (pinfunction "C_C") (pintype "passive"))
      (node (ref "R605") (pin "2") (pinfunction "2_2") (pintype "passive"))
    )
    (net (code "98") (name "Net-(D603-PadC)") (class "Default")
      (node (ref "D603") (pin "C") (pinfunction "C_C") (pintype "passive"))
      (node (ref "R606") (pin "2") (pinfunction "2_2") (pintype "passive"))
    )
    (net (code "99") (name "Net-(D604-PadC)") (class "Default")
      (node (ref "D604") (pin "C") (pinfunction "C_C") (pintype "passive"))
      (node (ref "R607") (pin "2") (pinfunction "2_2") (pintype "passive"))
    )
    (net (code "100") (name "Net-(D701-PadC)") (class "Default")
      (node (ref "D701") (pin "C") (pinfunction "C_C") (pintype "passive"))
      (node (ref "R705") (pin "2") (pinfunction "2_2") (pintype "passive"))
    )
    (net (code "101") (name "Net-(D702-PadC)") (class "Default")
      (node (ref "D702") (pin "C") (pinfunction "C_C") (pintype "passive"))
      (node (ref "R706") (pin "2") (pinfunction "2_2") (pintype "passive"))
    )
    (net (code "102") (name "Net-(D703-PadC)") (class "Default")
      (node (ref "D703") (pin "C") (pinfunction "C_C") (pintype "passive"))
      (node (ref "R707") (pin "2") (pinfunction "2_2") (pintype "passive"))
    )
    (net (code "103") (name "Net-(D802-PadC)") (class "Default")
      (node (ref "D802") (pin "C") (pinfunction "C_C") (pintype "passive"))
      (node (ref "R804") (pin "2") (pinfunction "2_2") (pintype "passive"))
    )
    (net (code "104") (name "Net-(D803-PadC)") (class "Default")
      (node (ref "D803") (pin "C") (pinfunction "C_C") (pintype "passive"))
      (node (ref "R805") (pin "2") (pinfunction "2_2") (pintype "passive"))
    )
    (net (code "105") (name "Net-(D804-PadC)") (class "Default")
      (node (ref "D804") (pin "C") (pinfunction "C_C") (pintype "passive"))
      (node (ref "R806") (pin "2") (pinfunction "2_2") (pintype "passive"))
    )
    (net (code "106") (name "Net-(D902-PadC)") (class "Default")
      (node (ref "D902") (pin "C") (pinfunction "C_C") (pintype "passive"))
      (node (ref "R905") (pin "2") (pinfunction "2_2") (pintype "passive"))
    )
    (net (code "107") (name "Net-(D903-PadC)") (class "Default")
      (node (ref "D903") (pin "C") (pinfunction "C_C") (pintype "passive"))
      (node (ref "R906") (pin "2") (pinfunction "2_2") (pintype "passive"))
    )
    (net (code "108") (name "Net-(D904-PadC)") (class "Default")
      (node (ref "D904") (pin "C") (pinfunction "C_C") (pintype "passive"))
      (node (ref "R907") (pin "2") (pinfunction "2_2") (pintype "passive"))
    )
    (net (code "109") (name "Net-(D1002-PadC)") (class "Default")
      (node (ref "D1002") (pin "C") (pinfunction "C_C") (pintype "passive"))
      (node (ref "R1006") (pin "2") (pinfunction "2_2") (pintype "passive"))
    )
    (net (code "110") (name "Net-(D1003-PadC)") (class "Default")
      (node (ref "D1003") (pin "C") (pinfunction "C_C") (pintype "passive"))
      (node (ref "R1007") (pin "2") (pinfunction "2_2") (pintype "passive"))
    )
    (net (code "111") (name "Net-(D1004-PadC)") (class "Default")
      (node (ref "D1004") (pin "C") (pinfunction "C_C") (pintype "passive"))
      (node (ref "R1008") (pin "2") (pinfunction "2_2") (pintype "passive"))
    )
    (net (code "112") (name "Net-(D1101-PadC)") (class "Default")
      (node (ref "D1101") (pin "C") (pinfunction "C_C") (pintype "passive"))
      (node (ref "R1104") (pin "2") (pinfunction "2_2") (pintype "passive"))
    )
    (net (code "113") (name "Net-(D1102-PadC)") (class "Default")
      (node (ref "D1102") (pin "C") (pinfunction "C_C") (pintype "passive"))
      (node (ref "R1105") (pin "2") (pinfunction "2_2") (pintype "passive"))
    )
    (net (code "114") (name "Net-(D1103-PadC)") (class "Default")
      (node (ref "D1103") (pin "C") (pinfunction "C_C") (pintype "passive"))
      (node (ref "R1106") (pin "2") (pinfunction "2_2") (pintype "passive"))
    )
    (net (code "115") (name "Net-(D1201-PadC)") (class "Default")
      (node (ref "D1201") (pin "C") (pinfunction "C_C") (pintype "passive"))
      (node (ref "R1204") (pin "2") (pinfunction "2_2") (pintype "passive"))
    )
    (net (code "116") (name "Net-(D1202-PadC)") (class "Default")
      (node (ref "D1202") (pin "C") (pinfunction "C_C") (pintype "passive"))
      (node (ref "R1205") (pin "2") (pinfunction "2_2") (pintype "passive"))
    )
    (net (code "117") (name "Net-(D1203-PadC)") (class "Default")
      (node (ref "D1203") (pin "C") (pinfunction "C_C") (pintype "passive"))
      (node (ref "R1206") (pin "2") (pinfunction "2_2") (pintype "passive"))
    )
    (net (code "118") (name "Net-(D1301-PadC)") (class "Default")
      (node (ref "D1301") (pin "C") (pinfunction "C_C") (pintype "passive"))
      (node (ref "R1304") (pin "2") (pinfunction "2_2") (pintype "passive"))
    )
    (net (code "119") (name "Net-(D1302-PadC)") (class "Default")
      (node (ref "D1302") (pin "C") (pinfunction "C_C") (pintype "passive"))
      (node (ref "R1305") (pin "2") (pinfunction "2_2") (pintype "passive"))
    )
    (net (code "120") (name "Net-(D1303-PadC)") (class "Default")
      (node (ref "D1303") (pin "C") (pinfunction "C_C") (pintype "passive"))
      (node (ref "R1306") (pin "2") (pinfunction "2_2") (pintype "passive"))
    )
    (net (code "121") (name "Net-(D1402-PadC)") (class "Default")
      (node (ref "D1402") (pin "C") (pinfunction "C_C") (pintype "passive"))
      (node (ref "R1404") (pin "2") (pinfunction "2_2") (pintype "passive"))
    )
    (net (code "122") (name "Net-(D1403-PadC)") (class "Default")
      (node (ref "D1403") (pin "C") (pinfunction "C_C") (pintype "passive"))
      (node (ref "R1405") (pin "2") (pinfunction "2_2") (pintype "passive"))
    )
    (net (code "123") (name "Net-(D1404-PadC)") (class "Default")
      (node (ref "D1404") (pin "C") (pinfunction "C_C") (pintype "passive"))
      (node (ref "R1406") (pin "2") (pinfunction "2_2") (pintype "passive"))
    )
    (net (code "124") (name "Net-(D1501-PadC)") (class "Default")
      (node (ref "D1501") (pin "C") (pinfunction "C_C") (pintype "passive"))
      (node (ref "R1502") (pin "2") (pinfunction "2_2") (pintype "passive"))
    )
    (net (code "125") (name "Net-(D1502-PadC)") (class "Default")
      (node (ref "D1502") (pin "C") (pinfunction "C_C") (pintype "passive"))
      (node (ref "R1503") (pin "2") (pinfunction "2_2") (pintype "passive"))
    )
    (net (code "126") (name "Net-(J501-Pad1)") (class "Default")
      (node (ref "J501") (pin "1") (pinfunction "1_1") (pintype "passive"))
      (node (ref "R501") (pin "1") (pinfunction "1_1") (pintype "passive"))
    )
    (net (code "127") (name "Net-(J701-Pad1)") (class "Default")
      (node (ref "J701") (pin "1") (pinfunction "1_1") (pintype "passive"))
      (node (ref "R702") (pin "2") (pinfunction "2_2") (pintype "passive"))
    )
    (net (code "128") (name "Net-(J702-Pad2)") (class "Default")
      (node (ref "J702") (pin "2") (pinfunction "2_2") (pintype "passive"))
      (node (ref "R701") (pin "2") (pinfunction "2_2") (pintype "passive"))
    )
    (net (code "129") (name "Net-(J1002-Pad1)") (class "Default")
      (node (ref "J1002") (pin "1") (pinfunction "1_1") (pintype "passive"))
      (node (ref "R1003") (pin "1") (pinfunction "1_1") (pintype "passive"))
    )
    (net (code "130") (name "Net-(JP201-Pad2)") (class "Default")
      (node (ref "JP201") (pin "2") (pinfunction "2_2") (pintype "passive"))
      (node (ref "JP202") (pin "2") (pinfunction "2_2") (pintype "passive"))
      (node (ref "R201") (pin "1") (pinfunction "1_1") (pintype "passive"))
      (node (ref "R202") (pin "1") (pinfunction "1_1") (pintype "passive"))
      (node (ref "TP201") (pin "TP") (pinfunction "TP_TP") (pintype "input"))
    )
    (net (code "131") (name "Net-(JP1401-Pad2)") (class "Default")
      (node (ref "JP1401") (pin "2") (pinfunction "2_2") (pintype "passive"))
      (node (ref "JP1402") (pin "2") (pinfunction "2_2") (pintype "passive"))
      (node (ref "R1402") (pin "1") (pinfunction "1_1") (pintype "passive"))
      (node (ref "R1403") (pin "1") (pinfunction "1_1") (pintype "passive"))
      (node (ref "TP1401") (pin "TP") (pinfunction "TP_TP") (pintype "input"))
    )
    (net (code "132") (name "Net-(Q201-D)") (class "Default")
      (node (ref "D201") (pin "A") (pinfunction "A_A") (pintype "passive"))
      (node (ref "J203") (pin "2") (pinfunction "2_2") (pintype "passive"))
      (node (ref "Q201") (pin "MB") (pinfunction "D_MB") (pintype "passive"))
    )
    (net (code "133") (name "Net-(Q201-G)") (class "Default")
      (node (ref "Q201") (pin "4") (pinfunction "G_4") (pintype "passive"))
      (node (ref "R201") (pin "2") (pinfunction "2_2") (pintype "passive"))
    )
    (net (code "134") (name "Net-(Q301-B)") (class "Default")
      (node (ref "Q301") (pin "1") (pinfunction "B_1") (pintype "passive"))
      (node (ref "R302") (pin "2") (pinfunction "2_2") (pintype "passive"))
    )
    (net (code "135") (name "Net-(Q301-E)") (class "Default")
      (node (ref "D301") (pin "A") (pinfunction "A_A") (pintype "passive"))
      (node (ref "Q301") (pin "2") (pinfunction "E_2") (pintype "passive"))
    )
    (net (code "136") (name "Net-(Q401-B)") (class "Default")
      (node (ref "Q401") (pin "1") (pinfunction "B_1") (pintype "passive"))
      (node (ref "R403") (pin "2") (pinfunction "2_2") (pintype "passive"))
    )
    (net (code "137") (name "Net-(Q401-E)") (class "Default")
      (node (ref "D401") (pin "A") (pinfunction "A_A") (pintype "passive"))
      (node (ref "Q401") (pin "2") (pinfunction "E_2") (pintype "passive"))
    )
    (net (code "138") (name "Net-(Q501-D)") (class "Default")
      (node (ref "D501") (pin "A") (pinfunction "A_A") (pintype "passive"))
      (node (ref "J502") (pin "2") (pinfunction "2_2") (pintype "passive"))
      (node (ref "Q501") (pin "MB") (pinfunction "D_MB") (pintype "passive"))
    )
    (net (code "139") (name "Net-(Q501-G)") (class "Default")
      (node (ref "Q501") (pin "4") (pinfunction "G_4") (pintype "passive"))
      (node (ref "R502") (pin "2") (pinfunction "2_2") (pintype "passive"))
    )
    (net (code "140") (name "Net-(Q601-D)") (class "Default")
      (node (ref "D601") (pin "A") (pinfunction "A_A") (pintype "passive"))
      (node (ref "J602") (pin "2") (pinfunction "2_2") (pintype "passive"))
      (node (ref "Q601") (pin "MB") (pinfunction "D_MB") (pintype "passive"))
    )
    (net (code "141") (name "Net-(Q601-G)") (class "Default")
      (node (ref "Q601") (pin "4") (pinfunction "G_4") (pintype "passive"))
      (node (ref "R601") (pin "2") (pinfunction "2_2") (pintype "passive"))
    )
    (net (code "142") (name "Net-(Q801-D)") (class "Default")
      (node (ref "D801") (pin "A") (pinfunction "A_A") (pintype "passive"))
      (node (ref "J802") (pin "2") (pinfunction "2_2") (pintype "passive"))
      (node (ref "Q801") (pin "MB") (pinfunction "D_MB") (pintype "passive"))
    )
    (net (code "143") (name "Net-(Q801-G)") (class "Default")
      (node (ref "Q801") (pin "4") (pinfunction "G_4") (pintype "passive"))
      (node (ref "R802") (pin "2") (pinfunction "2_2") (pintype "passive"))
    )
    (net (code "144") (name "Net-(Q901-D)") (class "Default")
      (node (ref "D901") (pin "A") (pinfunction "A_A") (pintype "passive"))
      (node (ref "J902") (pin "2") (pinfunction "2_2") (pintype "passive"))
      (node (ref "Q901") (pin "MB") (pinfunction "D_MB") (pintype "passive"))
    )
    (net (code "145") (name "Net-(Q901-G)") (class "Default")
      (node (ref "Q901") (pin "4") (pinfunction "G_4") (pintype "passive"))
      (node (ref "R901") (pin "2") (pinfunction "2_2") (pintype "passive"))
    )
    (net (code "146") (name "Net-(Q1001-D)") (class "Default")
      (node (ref "D1001") (pin "A") (pinfunction "A_A") (pintype "passive"))
      (node (ref "J1001") (pin "2") (pinfunction "2_2") (pintype "passive"))
      (node (ref "Q1001") (pin "MB") (pinfunction "D_MB") (pintype "passive"))
    )
    (net (code "147") (name "Net-(Q1001-G)") (class "Default")
      (node (ref "Q1001") (pin "4") (pinfunction "G_4") (pintype "passive"))
      (node (ref "R1001") (pin "2") (pinfunction "2_2") (pintype "passive"))
    )
    (net (code "148") (name "Net-(Q1401-D)") (class "Default")
      (node (ref "D1401") (pin "A") (pinfunction "A_A") (pintype "passive"))
      (node (ref "J1402") (pin "2") (pinfunction "2_2") (pintype "passive"))
      (node (ref "Q1401") (pin "MB") (pinfunction "D_MB") (pintype "passive"))
    )
    (net (code "149") (name "Net-(Q1401-G)") (class "Default")
      (node (ref "Q1401") (pin "4") (pinfunction "G_4") (pintype "passive"))
      (node (ref "R1402") (pin "2") (pinfunction "2_2") (pintype "passive"))
    )
    (net (code "150") (name "Net-(S101-2)") (class "Default")
      (node (ref "JP101") (pin "1") (pinfunction "1_1") (pintype "passive"))
      (node (ref "R101") (pin "2") (pinfunction "2_2") (pintype "passive"))
      (node (ref "S101") (pin "P$2") (pinfunction "2_P$2") (pintype "passive"))
      (node (ref "U101") (pin "2") (pinfunction "A_2") (pintype "bidirectional"))
    )
    (net (code "151") (name "Net-(U101A-Y)") (class "Default")
      (node (ref "JP102") (pin "1") (pinfunction "1_1") (pintype "passive"))
      (node (ref "U101") (pin "4") (pinfunction "Y_4") (pintype "bidirectional"))
    )
    (net (code "152") (name "Net-(U201A-Y)") (class "Default")
      (node (ref "JP202") (pin "1") (pinfunction "1_1") (pintype "passive"))
      (node (ref "U201") (pin "4") (pinfunction "Y_4") (pintype "bidirectional"))
    )
    (net (code "153") (name "Net-(U202-PB3(ADC3))") (class "Default")
      (node (ref "TP203") (pin "TP") (pinfunction "TP_TP") (pintype "input"))
      (node (ref "U202") (pin "2") (pinfunction "PB3(ADC3)_2") (pintype "bidirectional"))
    )
    (net (code "154") (name "Net-(U301A-Y)") (class "Default")
      (node (ref "TP301") (pin "TP") (pinfunction "TP_TP") (pintype "input"))
      (node (ref "U301") (pin "4") (pinfunction "Y_4") (pintype "bidirectional"))
      (node (ref "U302") (pin "2") (pinfunction "B_2") (pintype "input"))
    )
    (net (code "155") (name "Net-(U302A-Y)") (class "Default")
      (node (ref "R302") (pin "1") (pinfunction "1_1") (pintype "passive"))
      (node (ref "TP302") (pin "TP") (pinfunction "TP_TP") (pintype "input"))
      (node (ref "U302") (pin "4") (pinfunction "Y_4") (pintype "output"))
    )
    (net (code "156") (name "Net-(U303-PB3(ADC3))") (class "Default")
      (node (ref "TP303") (pin "TP") (pinfunction "TP_TP") (pintype "input"))
      (node (ref "U303") (pin "2") (pinfunction "PB3(ADC3)_2") (pintype "bidirectional"))
    )
    (net (code "157") (name "Net-(U401A-Y)") (class "Default")
      (node (ref "TP401") (pin "TP") (pinfunction "TP_TP") (pintype "input"))
      (node (ref "U401") (pin "4") (pinfunction "Y_4") (pintype "bidirectional"))
      (node (ref "U402") (pin "2") (pinfunction "B_2") (pintype "input"))
    )
    (net (code "158") (name "Net-(U402A-Y)") (class "Default")
      (node (ref "R403") (pin "1") (pinfunction "1_1") (pintype "passive"))
      (node (ref "TP402") (pin "TP") (pinfunction "TP_TP") (pintype "input"))
      (node (ref "U402") (pin "4") (pinfunction "Y_4") (pintype "output"))
    )
    (net (code "159") (name "Net-(U403-PB3(ADC3))") (class "Default")
      (node (ref "TP404") (pin "TP") (pinfunction "TP_TP") (pintype "input"))
      (node (ref "U403") (pin "2") (pinfunction "PB3(ADC3)_2") (pintype "bidirectional"))
    )
    (net (code "160") (name "Net-(U501A-Y)") (class "Default")
      (node (ref "TP501") (pin "TP") (pinfunction "TP_TP") (pintype "input"))
      (node (ref "U501") (pin "4") (pinfunction "Y_4") (pintype "bidirectional"))
      (node (ref "U502") (pin "2") (pinfunction "B_2") (pintype "input"))
    )
    (net (code "161") (name "Net-(U502A-Y)") (class "Default")
      (node (ref "R502") (pin "1") (pinfunction "1_1") (pintype "passive"))
      (node (ref "R503") (pin "1") (pinfunction "1_1") (pintype "passive"))
      (node (ref "TP502") (pin "TP") (pinfunction "TP_TP") (pintype "input"))
      (node (ref "U502") (pin "4") (pinfunction "Y_4") (pintype "output"))
    )
    (net (code "162") (name "Net-(U503-PB3(ADC3))") (class "Default")
      (node (ref "TP504") (pin "TP") (pinfunction "TP_TP") (pintype "input"))
      (node (ref "U503") (pin "2") (pinfunction "PB3(ADC3)_2") (pintype "bidirectional"))
    )
    (net (code "163") (name "Net-(U601A-Y)") (class "Default")
      (node (ref "TP602") (pin "TP") (pinfunction "TP_TP") (pintype "input"))
      (node (ref "U601") (pin "4") (pinfunction "Y_4") (pintype "bidirectional"))
      (node (ref "U602") (pin "2") (pinfunction "B_2") (pintype "input"))
    )
    (net (code "164") (name "Net-(U602A-Y)") (class "Default")
      (node (ref "R601") (pin "1") (pinfunction "1_1") (pintype "passive"))
      (node (ref "R602") (pin "1") (pinfunction "1_1") (pintype "passive"))
      (node (ref "TP603") (pin "TP") (pinfunction "TP_TP") (pintype "input"))
      (node (ref "U602") (pin "4") (pinfunction "Y_4") (pintype "output"))
    )
    (net (code "165") (name "Net-(U603-PB3(ADC3))") (class "Default")
      (node (ref "TP604") (pin "TP") (pinfunction "TP_TP") (pintype "input"))
      (node (ref "U603") (pin "2") (pinfunction "PB3(ADC3)_2") (pintype "bidirectional"))
    )
    (net (code "166") (name "Net-(U701-PB3(ADC3))") (class "Default")
      (node (ref "TP702") (pin "TP") (pinfunction "TP_TP") (pintype "input"))
      (node (ref "U701") (pin "2") (pinfunction "PB3(ADC3)_2") (pintype "bidirectional"))
    )
    (net (code "167") (name "Net-(U702-PB4(ADC2))") (class "Default")
      (node (ref "TP703") (pin "TP") (pinfunction "TP_TP") (pintype "input"))
      (node (ref "U702") (pin "3") (pinfunction "PB4(ADC2)_3") (pintype "bidirectional"))
    )
    (net (code "168") (name "Net-(U801A-Y)") (class "Default")
      (node (ref "TP802") (pin "TP") (pinfunction "TP_TP") (pintype "input"))
      (node (ref "U801") (pin "4") (pinfunction "Y_4") (pintype "bidirectional"))
      (node (ref "U802") (pin "2") (pinfunction "B_2") (pintype "input"))
    )
    (net (code "169") (name "Net-(U802A-Y)") (class "Default")
      (node (ref "R802") (pin "1") (pinfunction "1_1") (pintype "passive"))
      (node (ref "R803") (pin "1") (pinfunction "1_1") (pintype "passive"))
      (node (ref "TP803") (pin "TP") (pinfunction "TP_TP") (pintype "input"))
      (node (ref "U802") (pin "4") (pinfunction "Y_4") (pintype "output"))
    )
    (net (code "170") (name "Net-(U901-PB4(ADC2))") (class "Default")
      (node (ref "TP902") (pin "TP") (pinfunction "TP_TP") (pintype "input"))
      (node (ref "U901") (pin "3") (pinfunction "PB4(ADC2)_3") (pintype "bidirectional"))
    )
    (net (code "171") (name "Net-(U1001-PB4(ADC2))") (class "Default")
      (node (ref "TP1002") (pin "TP") (pinfunction "TP_TP") (pintype "input"))
      (node (ref "U1001") (pin "3") (pinfunction "PB4(ADC2)_3") (pintype "bidirectional"))
    )
    (net (code "172") (name "Net-(U1101-AOUT1)") (class "Default")
      (node (ref "J1102") (pin "1") (pinfunction "1_1") (pintype "passive"))
      (node (ref "U1101") (pin "2") (pinfunction "AOUT1_2") (pintype "bidirectional"))
    )
    (net (code "173") (name "Net-(U1101-AOUT2)") (class "Default")
      (node (ref "J1102") (pin "2") (pinfunction "2_2") (pintype "passive"))
      (node (ref "U1101") (pin "3") (pinfunction "AOUT2_3") (pintype "bidirectional"))
    )
    (net (code "174") (name "Net-(U1102-PB4(ADC2))") (class "Default")
      (node (ref "TP1102") (pin "TP") (pinfunction "TP_TP") (pintype "input"))
      (node (ref "U1102") (pin "3") (pinfunction "PB4(ADC2)_3") (pintype "bidirectional"))
    )
    (net (code "175") (name "Net-(U1201-AOUT1)") (class "Default")
      (node (ref "J1203") (pin "1") (pinfunction "1_1") (pintype "passive"))
      (node (ref "U1201") (pin "2") (pinfunction "AOUT1_2") (pintype "bidirectional"))
    )
    (net (code "176") (name "Net-(U1201-AOUT2)") (class "Default")
      (node (ref "J1203") (pin "2") (pinfunction "2_2") (pintype "passive"))
      (node (ref "U1201") (pin "3") (pinfunction "AOUT2_3") (pintype "bidirectional"))
    )
    (net (code "177") (name "Net-(U1202-PB4(ADC2))") (class "Default")
      (node (ref "TP1202") (pin "TP") (pinfunction "TP_TP") (pintype "input"))
      (node (ref "U1202") (pin "3") (pinfunction "PB4(ADC2)_3") (pintype "bidirectional"))
    )
    (net (code "178") (name "Net-(U1301-AOUT1)") (class "Default")
      (node (ref "J1303") (pin "1") (pinfunction "1_1") (pintype "passive"))
      (node (ref "U1301") (pin "2") (pinfunction "AOUT1_2") (pintype "bidirectional"))
    )
    (net (code "179") (name "Net-(U1301-AOUT2)") (class "Default")
      (node (ref "J1303") (pin "2") (pinfunction "2_2") (pintype "passive"))
      (node (ref "U1301") (pin "3") (pinfunction "AOUT2_3") (pintype "bidirectional"))
    )
    (net (code "180") (name "Net-(U1302-PB4(ADC2))") (class "Default")
      (node (ref "TP1302") (pin "TP") (pinfunction "TP_TP") (pintype "input"))
      (node (ref "U1302") (pin "3") (pinfunction "PB4(ADC2)_3") (pintype "bidirectional"))
    )
    (net (code "181") (name "Net-(U1401A-Y)") (class "Default")
      (node (ref "JP1402") (pin "1") (pinfunction "1_1") (pintype "passive"))
      (node (ref "U1401") (pin "4") (pinfunction "Y_4") (pintype "bidirectional"))
    )
    (net (code "182") (name "START_OUT") (class "Default")
      (node (ref "D101") (pin "A") (pinfunction "A_A") (pintype "passive"))
      (node (ref "J1601") (pin "2") (pinfunction "2_2") (pintype "passive"))
      (node (ref "JP101") (pin "2") (pinfunction "2_2") (pintype "passive"))
      (node (ref "JP102") (pin "2") (pinfunction "2_2") (pintype "passive"))
      (node (ref "S102") (pin "2") (pinfunction "P_2") (pintype "passive"))
    )
    (net (code "183") (name "START_VCC") (class "Default")
      (node (ref "C101") (pin "+") (pinfunction "+_+") (pintype "passive"))
      (node (ref "D102") (pin "A") (pinfunction "A_A") (pintype "passive"))
      (node (ref "R101") (pin "1") (pinfunction "1_1") (pintype "passive"))
      (node (ref "S102") (pin "1") (pinfunction "O_1") (pintype "passive"))
      (node (ref "TP101") (pin "TP") (pinfunction "TP_TP") (pintype "input"))
      (node (ref "U101") (pin "5") (pinfunction "P$V+_5") (pintype "bidirectional"))
      (node (ref "U102") (pin "5") (pinfunction "OUT_5") (pintype "passive"))
    )
    (net (code "184") (name "TIMER_IN") (class "Default")
      (node (ref "D1102") (pin "A") (pinfunction "A_A") (pintype "passive"))
      (node (ref "J1610") (pin "1") (pinfunction "1_1") (pintype "passive"))
      (node (ref "U1102") (pin "2") (pinfunction "PB3(ADC3)_2") (pintype "bidirectional"))
    )
    (net (code "185") (name "TIMER_MISO") (class "Default")
      (node (ref "J1104") (pin "1") (pinfunction "1_1") (pintype "passive"))
      (node (ref "U1101") (pin "9") (pinfunction "AIN2/EN_9") (pintype "bidirectional"))
      (node (ref "U1102") (pin "6") (pinfunction "PB1(MISO)_6") (pintype "bidirectional"))
    )
    (net (code "186") (name "TIMER_MOSI") (class "Default")
      (node (ref "J1104") (pin "4") (pinfunction "4_4") (pintype "passive"))
      (node (ref "U1101") (pin "10") (pinfunction "AIN1/PH_10") (pintype "bidirectional"))
      (node (ref "U1102") (pin "5") (pinfunction "PB0(MOSI)_5") (pintype "bidirectional"))
    )
    (net (code "187") (name "TIMER_OUT") (class "Default")
      (node (ref "D1101") (pin "A") (pinfunction "A_A") (pintype "passive"))
      (node (ref "J1101") (pin "2") (pinfunction "2_2") (pintype "passive"))
      (node (ref "J1611") (pin "2") (pinfunction "2_2") (pintype "passive"))
      (node (ref "R1101") (pin "1") (pinfunction "1_1") (pintype "passive"))
      (node (ref "S1102") (pin "2") (pinfunction "P_2") (pintype "passive"))
    )
    (net (code "188") (name "TIMER_RST") (class "Default")
      (node (ref "J1104") (pin "5") (pinfunction "5_5") (pintype "passive"))
      (node (ref "R1103") (pin "1") (pinfunction "1_1") (pintype "passive"))
      (node (ref "S1101") (pin "3") (pinfunction "2_3") (pintype "passive"))
      (node (ref "S1101") (pin "4") (pinfunction "2_4") (pintype "passive"))
      (node (ref "U1102") (pin "1") (pinfunction "PB5(NRES)_1") (pintype "bidirectional"))
    )
    (net (code "189") (name "TIMER_SCK") (class "Default")
      (node (ref "J1103") (pin "2") (pinfunction "2_2") (pintype "passive"))
      (node (ref "J1104") (pin "3") (pinfunction "3_3") (pintype "passive"))
      (node (ref "R1102") (pin "1") (pinfunction "1_1") (pintype "passive"))
      (node (ref "U1102") (pin "7") (pinfunction "PB2(SCK/ADC1)_7") (pintype "bidirectional"))
    )
    (net (code "190") (name "TIMER_VCC") (class "Default")
      (node (ref "C1101") (pin "2") (pinfunction "2_2") (pintype "passive"))
      (node (ref "C1103") (pin "1") (pinfunction "1_1") (pintype "passive"))
      (node (ref "D1103") (pin "A") (pinfunction "A_A") (pintype "passive"))
      (node (ref "IC1101") (pin "2") (pinfunction "VO_2") (pintype "passive"))
      (node (ref "J1101") (pin "1") (pinfunction "1_1") (pintype "passive"))
      (node (ref "J1103") (pin "1") (pinfunction "1_1") (pintype "passive"))
      (node (ref "J1104") (pin "2") (pinfunction "2_2") (pintype "passive"))
      (node (ref "R1103") (pin "2") (pinfunction "2_2") (pintype "passive"))
      (node (ref "S1102") (pin "1") (pinfunction "O_1") (pintype "passive"))
      (node (ref "TP1101") (pin "TP") (pinfunction "TP_TP") (pintype "input"))
      (node (ref "U1101") (pin "1") (pinfunction "VM_1") (pintype "bidirectional"))
      (node (ref "U1101") (pin "11") (pinfunction "MODE_11") (pintype "bidirectional"))
      (node (ref "U1101") (pin "12") (pinfunction "VCC_12") (pintype "bidirectional"))
      (node (ref "U1102") (pin "8") (pinfunction "VCC_8") (pintype "bidirectional"))
    )
    (net (code "191") (name "V_BATT") (class "Default")
      (node (ref "C1102") (pin "2") (pinfunction "2_2") (pintype "passive"))
      (node (ref "C1202") (pin "2") (pinfunction "2_2") (pintype "passive"))
      (node (ref "C1302") (pin "2") (pinfunction "2_2") (pintype "passive"))
      (node (ref "C1501") (pin "2") (pinfunction "2_2") (pintype "passive"))
      (node (ref "C1601") (pin "+") (pinfunction "+_+") (pintype "passive"))
      (node (ref "C1602") (pin "+") (pinfunction "+_+") (pintype "passive"))
      (node (ref "C1603") (pin "+") (pinfunction "+_+") (pintype "passive"))
      (node (ref "C1604") (pin "1") (pinfunction "1_1") (pintype "passive"))
      (node (ref "D1001") (pin "C") (pinfunction "C_C") (pintype "passive"))
      (node (ref "D1401") (pin "C") (pinfunction "C_C") (pintype "passive"))
      (node (ref "D1601") (pin "C") (pinfunction "C_C") (pintype "passive"))
      (node (ref "D201") (pin "C") (pinfunction "C_C") (pintype "passive"))
      (node (ref "D501") (pin "C") (pinfunction "C_C") (pintype "passive"))
      (node (ref "D601") (pin "C") (pinfunction "C_C") (pintype "passive"))
      (node (ref "D801") (pin "C") (pinfunction "C_C") (pintype "passive"))
      (node (ref "D901") (pin "C") (pinfunction "C_C") (pintype "passive"))
      (node (ref "IC1101") (pin "1") (pinfunction "VI_1") (pintype "input"))
      (node (ref "IC1201") (pin "1") (pinfunction "VI_1") (pintype "input"))
      (node (ref "IC1301") (pin "1") (pinfunction "VI_1") (pintype "input"))
      (node (ref "IC1501") (pin "1") (pinfunction "VI_1") (pintype "input"))
      (node (ref "J1001") (pin "1") (pinfunction "1_1") (pintype "passive"))
      (node (ref "J1003") (pin "1") (pinfunction "1_1") (pintype "passive"))
      (node (ref "J1402") (pin "1") (pinfunction "1_1") (pintype "passive"))
      (node (ref "J201") (pin "2") (pinfunction "2_2") (pintype "passive"))
      (node (ref "J202") (pin "1") (pinfunction "1_1") (pintype "passive"))
      (node (ref "J203") (pin "1") (pinfunction "1_1") (pintype "passive"))
      (node (ref "J502") (pin "1") (pinfunction "1_1") (pintype "passive"))
      (node (ref "J602") (pin "1") (pinfunction "1_1") (pintype "passive"))
      (node (ref "J802") (pin "1") (pinfunction "1_1") (pintype "passive"))
      (node (ref "J902") (pin "1") (pinfunction "1_1") (pintype "passive"))
      (node (ref "U1002") (pin "1") (pinfunction "IN_1") (pintype "input"))
      (node (ref "U1002") (pin "3") (pinfunction "EN_3") (pintype "input"))
      (node (ref "U102") (pin "1") (pinfunction "IN_1") (pintype "input"))
      (node (ref "U102") (pin "3") (pinfunction "EN_3") (pintype "input"))
      (node (ref "U1402") (pin "1") (pinfunction "IN_1") (pintype "input"))
      (node (ref "U1402") (pin "3") (pinfunction "EN_3") (pintype "input"))
      (node (ref "U203") (pin "1") (pinfunction "IN_1") (pintype "input"))
      (node (ref "U203") (pin "3") (pinfunction "EN_3") (pintype "input"))
      (node (ref "U304") (pin "1") (pinfunction "IN_1") (pintype "input"))
      (node (ref "U304") (pin "3") (pinfunction "EN_3") (pintype "input"))
      (node (ref "U404") (pin "1") (pinfunction "IN_1") (pintype "input"))
      (node (ref "U404") (pin "3") (pinfunction "EN_3") (pintype "input"))
      (node (ref "U504") (pin "1") (pinfunction "IN_1") (pintype "input"))
      (node (ref "U504") (pin "3") (pinfunction "EN_3") (pintype "input"))
      (node (ref "U604") (pin "1") (pinfunction "IN_1") (pintype "input"))
      (node (ref "U604") (pin "3") (pinfunction "EN_3") (pintype "input"))
      (node (ref "U703") (pin "1") (pinfunction "IN_1") (pintype "input"))
      (node (ref "U703") (pin "3") (pinfunction "EN_3") (pintype "input"))
      (node (ref "U803") (pin "1") (pinfunction "IN_1") (pintype "input"))
      (node (ref "U803") (pin "3") (pinfunction "EN_3") (pintype "input"))
      (node (ref "U902") (pin "1") (pinfunction "IN_1") (pintype "input"))
      (node (ref "U902") (pin "3") (pinfunction "EN_3") (pintype "input"))
      (node (ref "X1601") (pin "1") (pinfunction "1_1") (pintype "passive"))
    )
    (net (code "192") (name "WATER_IN") (class "Default")
      (node (ref "D603") (pin "A") (pinfunction "A_A") (pintype "passive"))
      (node (ref "J1605") (pin "1") (pinfunction "1_1") (pintype "passive"))
      (node (ref "U602") (pin "1") (pinfunction "A_1") (pintype "input"))
    )
    (net (code "193") (name "WATER_MISO") (class "Default")
      (node (ref "J603") (pin "1") (pinfunction "1_1") (pintype "passive"))
      (node (ref "U603") (pin "6") (pinfunction "PB1(MISO)_6") (pintype "bidirectional"))
    )
    (net (code "194") (name "WATER_MOSI") (class "Default")
      (node (ref "J603") (pin "4") (pinfunction "4_4") (pintype "passive"))
      (node (ref "U603") (pin "5") (pinfunction "PB0(MOSI)_5") (pintype "bidirectional"))
    )
    (net (code "195") (name "WATER_OUT") (class "Default")
      (node (ref "D602") (pin "A") (pinfunction "A_A") (pintype "passive"))
      (node (ref "J1606") (pin "2") (pinfunction "2_2") (pintype "passive"))
      (node (ref "S602") (pin "2") (pinfunction "P_2") (pintype "passive"))
      (node (ref "U601") (pin "2") (pinfunction "A_2") (pintype "bidirectional"))
    )
    (net (code "196") (name "WATER_OUT_SWITCH") (class "Default")
      (node (ref "S602") (pin "3") (pinfunction "S_3") (pintype "passive"))
      (node (ref "U603") (pin "3") (pinfunction "PB4(ADC2)_3") (pintype "bidirectional"))
    )
    (net (code "197") (name "WATER_RST") (class "Default")
      (node (ref "J603") (pin "5") (pinfunction "5_5") (pintype "passive"))
      (node (ref "R604") (pin "1") (pinfunction "1_1") (pintype "passive"))
      (node (ref "S601") (pin "3") (pinfunction "2_3") (pintype "passive"))
      (node (ref "S601") (pin "4") (pinfunction "2_4") (pintype "passive"))
      (node (ref "U603") (pin "1") (pinfunction "PB5(NRES)_1") (pintype "bidirectional"))
    )
    (net (code "198") (name "WATER_SCK") (class "Default")
      (node (ref "J601") (pin "1") (pinfunction "1_1") (pintype "passive"))
      (node (ref "J603") (pin "3") (pinfunction "3_3") (pintype "passive"))
      (node (ref "R603") (pin "1") (pinfunction "1_1") (pintype "passive"))
      (node (ref "U603") (pin "7") (pinfunction "PB2(SCK/ADC1)_7") (pintype "bidirectional"))
    )
    (net (code "199") (name "WATER_VCC") (class "Default")
      (node (ref "C601") (pin "2") (pinfunction "2_2") (pintype "passive"))
      (node (ref "C602") (pin "+") (pinfunction "+_+") (pintype "passive"))
      (node (ref "D604") (pin "A") (pinfunction "A_A") (pintype "passive"))
      (node (ref "J603") (pin "2") (pinfunction "2_2") (pintype "passive"))
      (node (ref "R603") (pin "2") (pinfunction "2_2") (pintype "passive"))
      (node (ref "R604") (pin "2") (pinfunction "2_2") (pintype "passive"))
      (node (ref "S602") (pin "1") (pinfunction "O_1") (pintype "passive"))
      (node (ref "TP601") (pin "TP") (pinfunction "TP_TP") (pintype "input"))
      (node (ref "U601") (pin "5") (pinfunction "P$V+_5") (pintype "bidirectional"))
      (node (ref "U602") (pin "5") (pinfunction "VCC_5") (pintype "power_in"))
      (node (ref "U603") (pin "8") (pinfunction "VCC_8") (pintype "bidirectional"))
      (node (ref "U604") (pin "5") (pinfunction "OUT_5") (pintype "passive"))
    )
    (net (code "200") (name "unconnected-(S102-S-Pad3)") (class "Default")
      (node (ref "S102") (pin "3") (pinfunction "S_3") (pintype "passive"))
    )
    (net (code "201") (name "unconnected-(S801-S-Pad3)") (class "Default")
      (node (ref "S801") (pin "3") (pinfunction "S_3") (pintype "passive"))
    )
    (net (code "202") (name "unconnected-(S902-S-Pad3)") (class "Default")
      (node (ref "S902") (pin "3") (pinfunction "S_3") (pintype "passive"))
    )
    (net (code "203") (name "unconnected-(S1002-S-Pad3)") (class "Default")
      (node (ref "S1002") (pin "3") (pinfunction "S_3") (pintype "passive"))
    )
    (net (code "204") (name "unconnected-(S1102-S-Pad3)") (class "Default")
      (node (ref "S1102") (pin "3") (pinfunction "S_3") (pintype "passive"))
    )
    (net (code "205") (name "unconnected-(S1202-S-Pad3)") (class "Default")
      (node (ref "S1202") (pin "3") (pinfunction "S_3") (pintype "passive"))
    )
    (net (code "206") (name "unconnected-(S1302-S-Pad3)") (class "Default")
      (node (ref "S1302") (pin "3") (pinfunction "S_3") (pintype "passive"))
    )
    (net (code "207") (name "unconnected-(S1401-S-Pad3)") (class "Default")
      (node (ref "S1401") (pin "3") (pinfunction "S_3") (pintype "passive"))
    )
    (net (code "208") (name "unconnected-(U102-BP-Pad4)") (class "Default")
      (node (ref "U102") (pin "4") (pinfunction "BP_4") (pintype "input"))
    )
    (net (code "209") (name "unconnected-(U203-BP-Pad4)") (class "Default")
      (node (ref "U203") (pin "4") (pinfunction "BP_4") (pintype "input"))
    )
    (net (code "210") (name "unconnected-(U304-BP-Pad4)") (class "Default")
      (node (ref "U304") (pin "4") (pinfunction "BP_4") (pintype "input"))
    )
    (net (code "211") (name "unconnected-(U404-BP-Pad4)") (class "Default")
      (node (ref "U404") (pin "4") (pinfunction "BP_4") (pintype "input"))
    )
    (net (code "212") (name "unconnected-(U504-BP-Pad4)") (class "Default")
      (node (ref "U504") (pin "4") (pinfunction "BP_4") (pintype "input"))
    )
    (net (code "213") (name "unconnected-(U604-BP-Pad4)") (class "Default")
      (node (ref "U604") (pin "4") (pinfunction "BP_4") (pintype "input"))
    )
    (net (code "214") (name "unconnected-(U703-BP-Pad4)") (class "Default")
      (node (ref "U703") (pin "4") (pinfunction "BP_4") (pintype "input"))
    )
    (net (code "215") (name "unconnected-(U803-BP-Pad4)") (class "Default")
      (node (ref "U803") (pin "4") (pinfunction "BP_4") (pintype "input"))
    )
    (net (code "216") (name "unconnected-(U902-BP-Pad4)") (class "Default")
      (node (ref "U902") (pin "4") (pinfunction "BP_4") (pintype "input"))
    )
    (net (code "217") (name "unconnected-(U1002-BP-Pad4)") (class "Default")
      (node (ref "U1002") (pin "4") (pinfunction "BP_4") (pintype "input"))
    )
    (net (code "218") (name "unconnected-(U1101-BIN1{slash}PH-Pad8)") (class "Default")
      (node (ref "U1101") (pin "8") (pinfunction "BIN1/PH_8") (pintype "bidirectional"))
    )
    (net (code "219") (name "unconnected-(U1101-BIN2{slash}EN-Pad7)") (class "Default")
      (node (ref "U1101") (pin "7") (pinfunction "BIN2/EN_7") (pintype "bidirectional"))
    )
    (net (code "220") (name "unconnected-(U1101-BOUT1-Pad4)") (class "Default")
      (node (ref "U1101") (pin "4") (pinfunction "BOUT1_4") (pintype "bidirectional"))
    )
    (net (code "221") (name "unconnected-(U1101-BOUT2-Pad5)") (class "Default")
      (node (ref "U1101") (pin "5") (pinfunction "BOUT2_5") (pintype "bidirectional"))
    )
    (net (code "222") (name "unconnected-(U1201-BIN1{slash}PH-Pad8)") (class "Default")
      (node (ref "U1201") (pin "8") (pinfunction "BIN1/PH_8") (pintype "bidirectional"))
    )
    (net (code "223") (name "unconnected-(U1201-BIN2{slash}EN-Pad7)") (class "Default")
      (node (ref "U1201") (pin "7") (pinfunction "BIN2/EN_7") (pintype "bidirectional"))
    )
    (net (code "224") (name "unconnected-(U1201-BOUT1-Pad4)") (class "Default")
      (node (ref "U1201") (pin "4") (pinfunction "BOUT1_4") (pintype "bidirectional"))
    )
    (net (code "225") (name "unconnected-(U1201-BOUT2-Pad5)") (class "Default")
      (node (ref "U1201") (pin "5") (pinfunction "BOUT2_5") (pintype "bidirectional"))
    )
    (net (code "226") (name "unconnected-(U1301-BIN1{slash}PH-Pad8)") (class "Default")
      (node (ref "U1301") (pin "8") (pinfunction "BIN1/PH_8") (pintype "bidirectional"))
    )
    (net (code "227") (name "unconnected-(U1301-BIN2{slash}EN-Pad7)") (class "Default")
      (node (ref "U1301") (pin "7") (pinfunction "BIN2/EN_7") (pintype "bidirectional"))
    )
    (net (code "228") (name "unconnected-(U1301-BOUT1-Pad4)") (class "Default")
      (node (ref "U1301") (pin "4") (pinfunction "BOUT1_4") (pintype "bidirectional"))
    )
    (net (code "229") (name "unconnected-(U1301-BOUT2-Pad5)") (class "Default")
      (node (ref "U1301") (pin "5") (pinfunction "BOUT2_5") (pintype "bidirectional"))
    )
    (net (code "230") (name "unconnected-(U1402-BP-Pad4)") (class "Default")
      (node (ref "U1402") (pin "4") (pinfunction "BP_4") (pintype "input"))
    )
  )
)
